# synth_revC.net
KiCad netlist of a schematic drawn in EAGLE
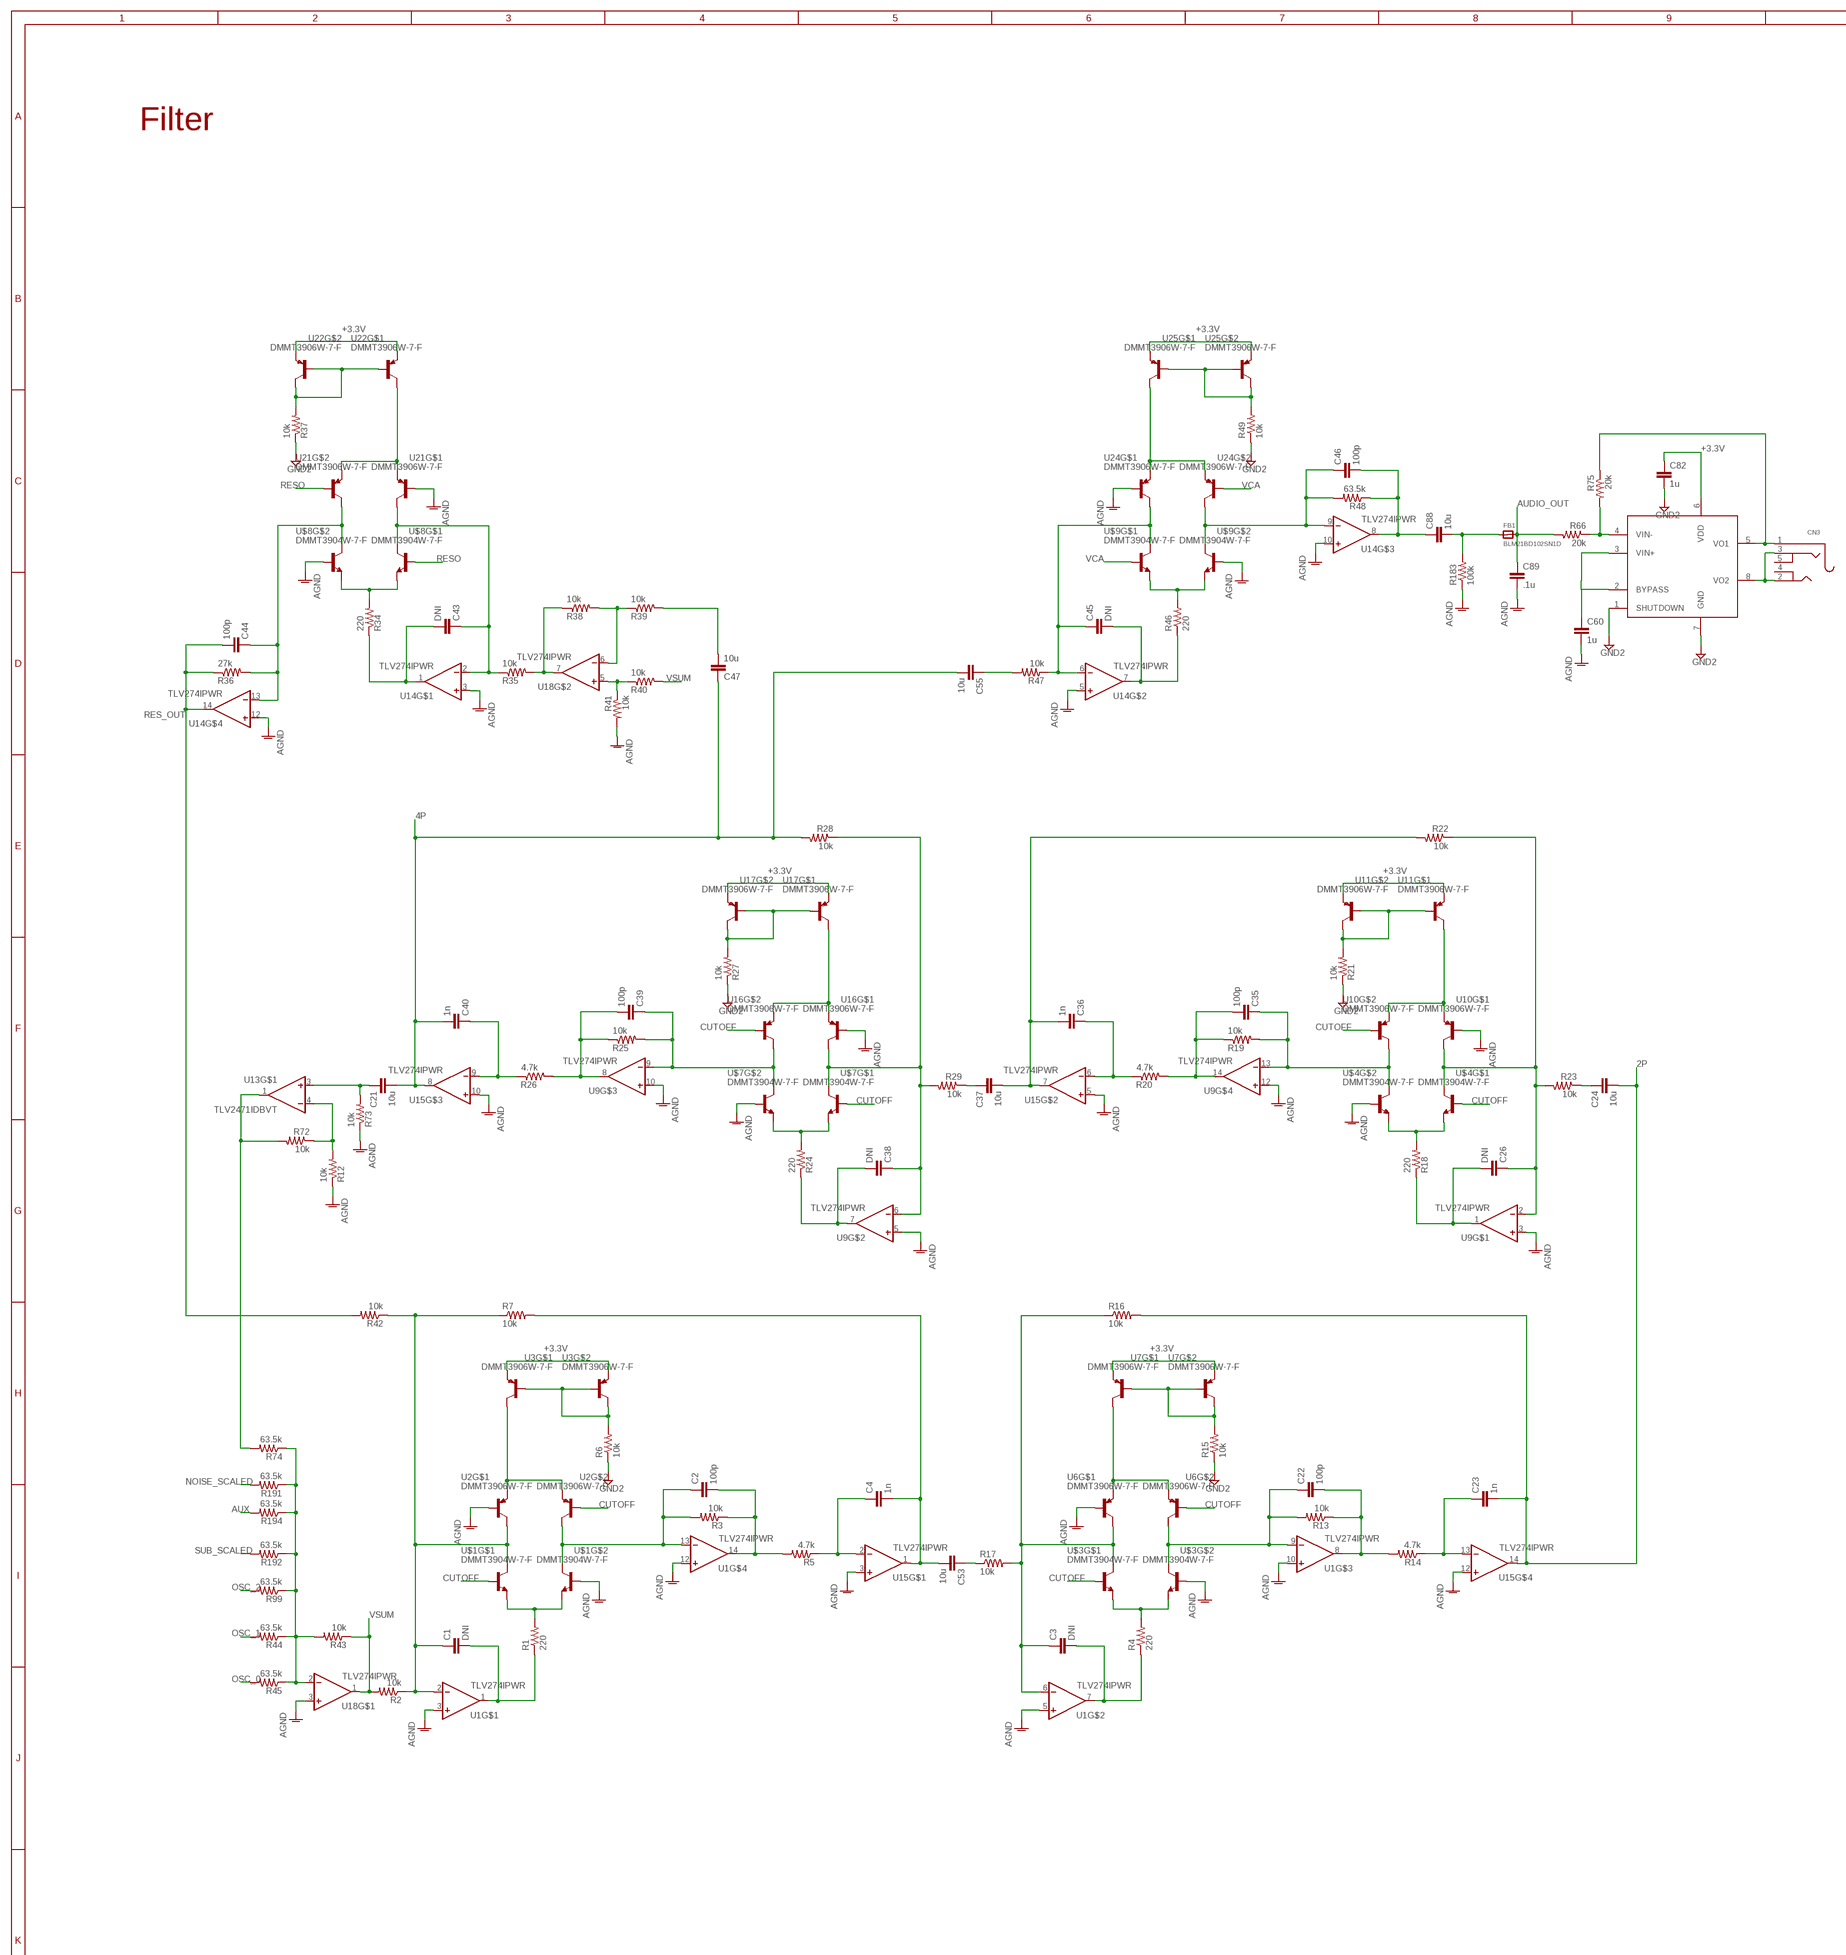
[diagram p0: schematic, sheet 1, part 1 of 3]
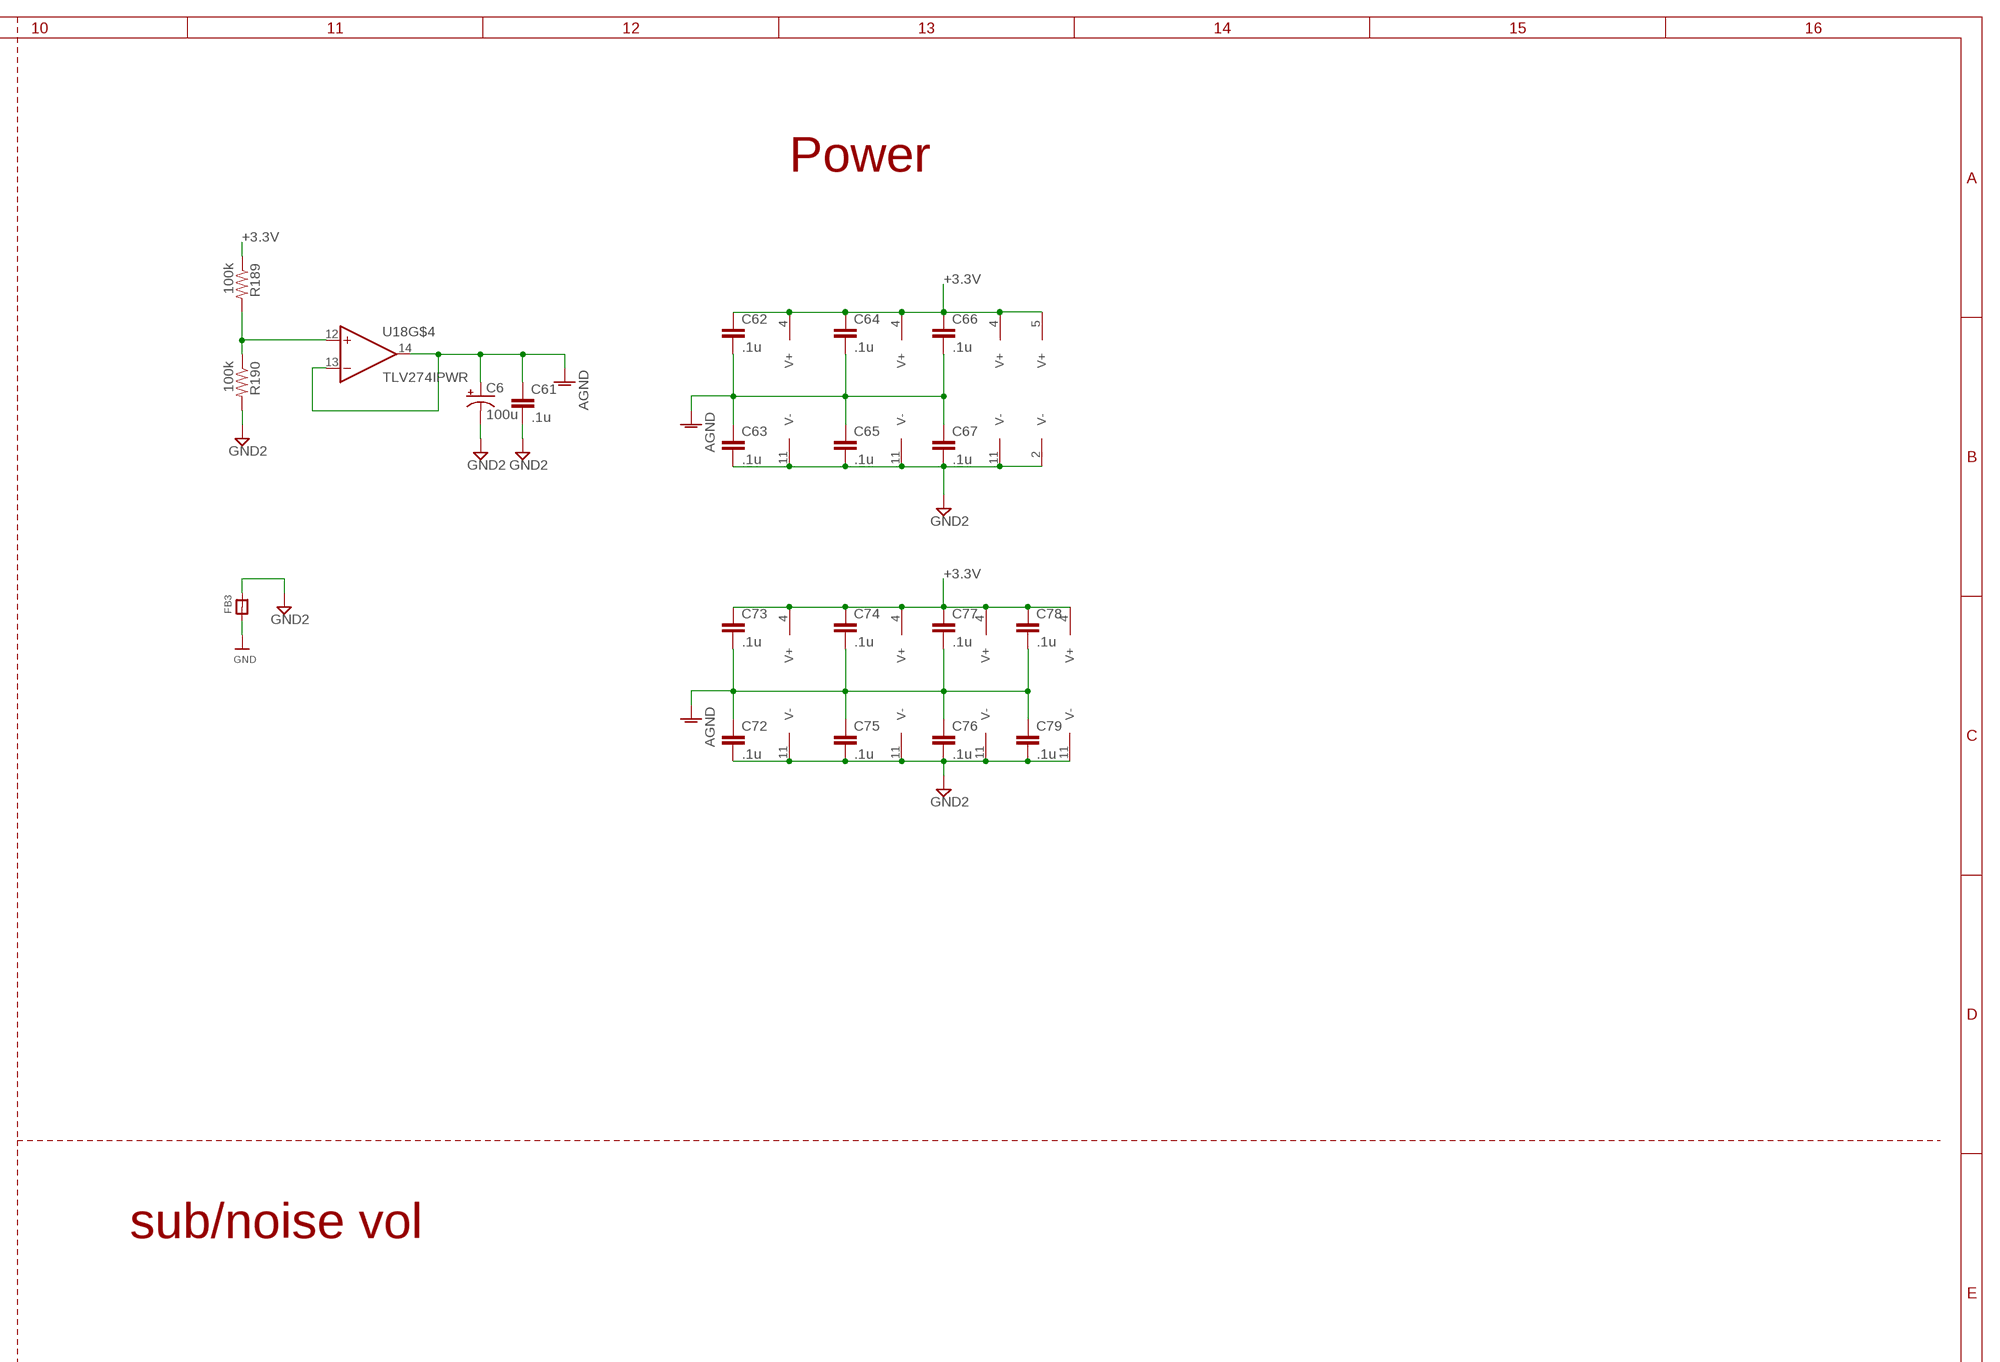
[diagram p1: schematic, sheet 1, part 2 of 3]
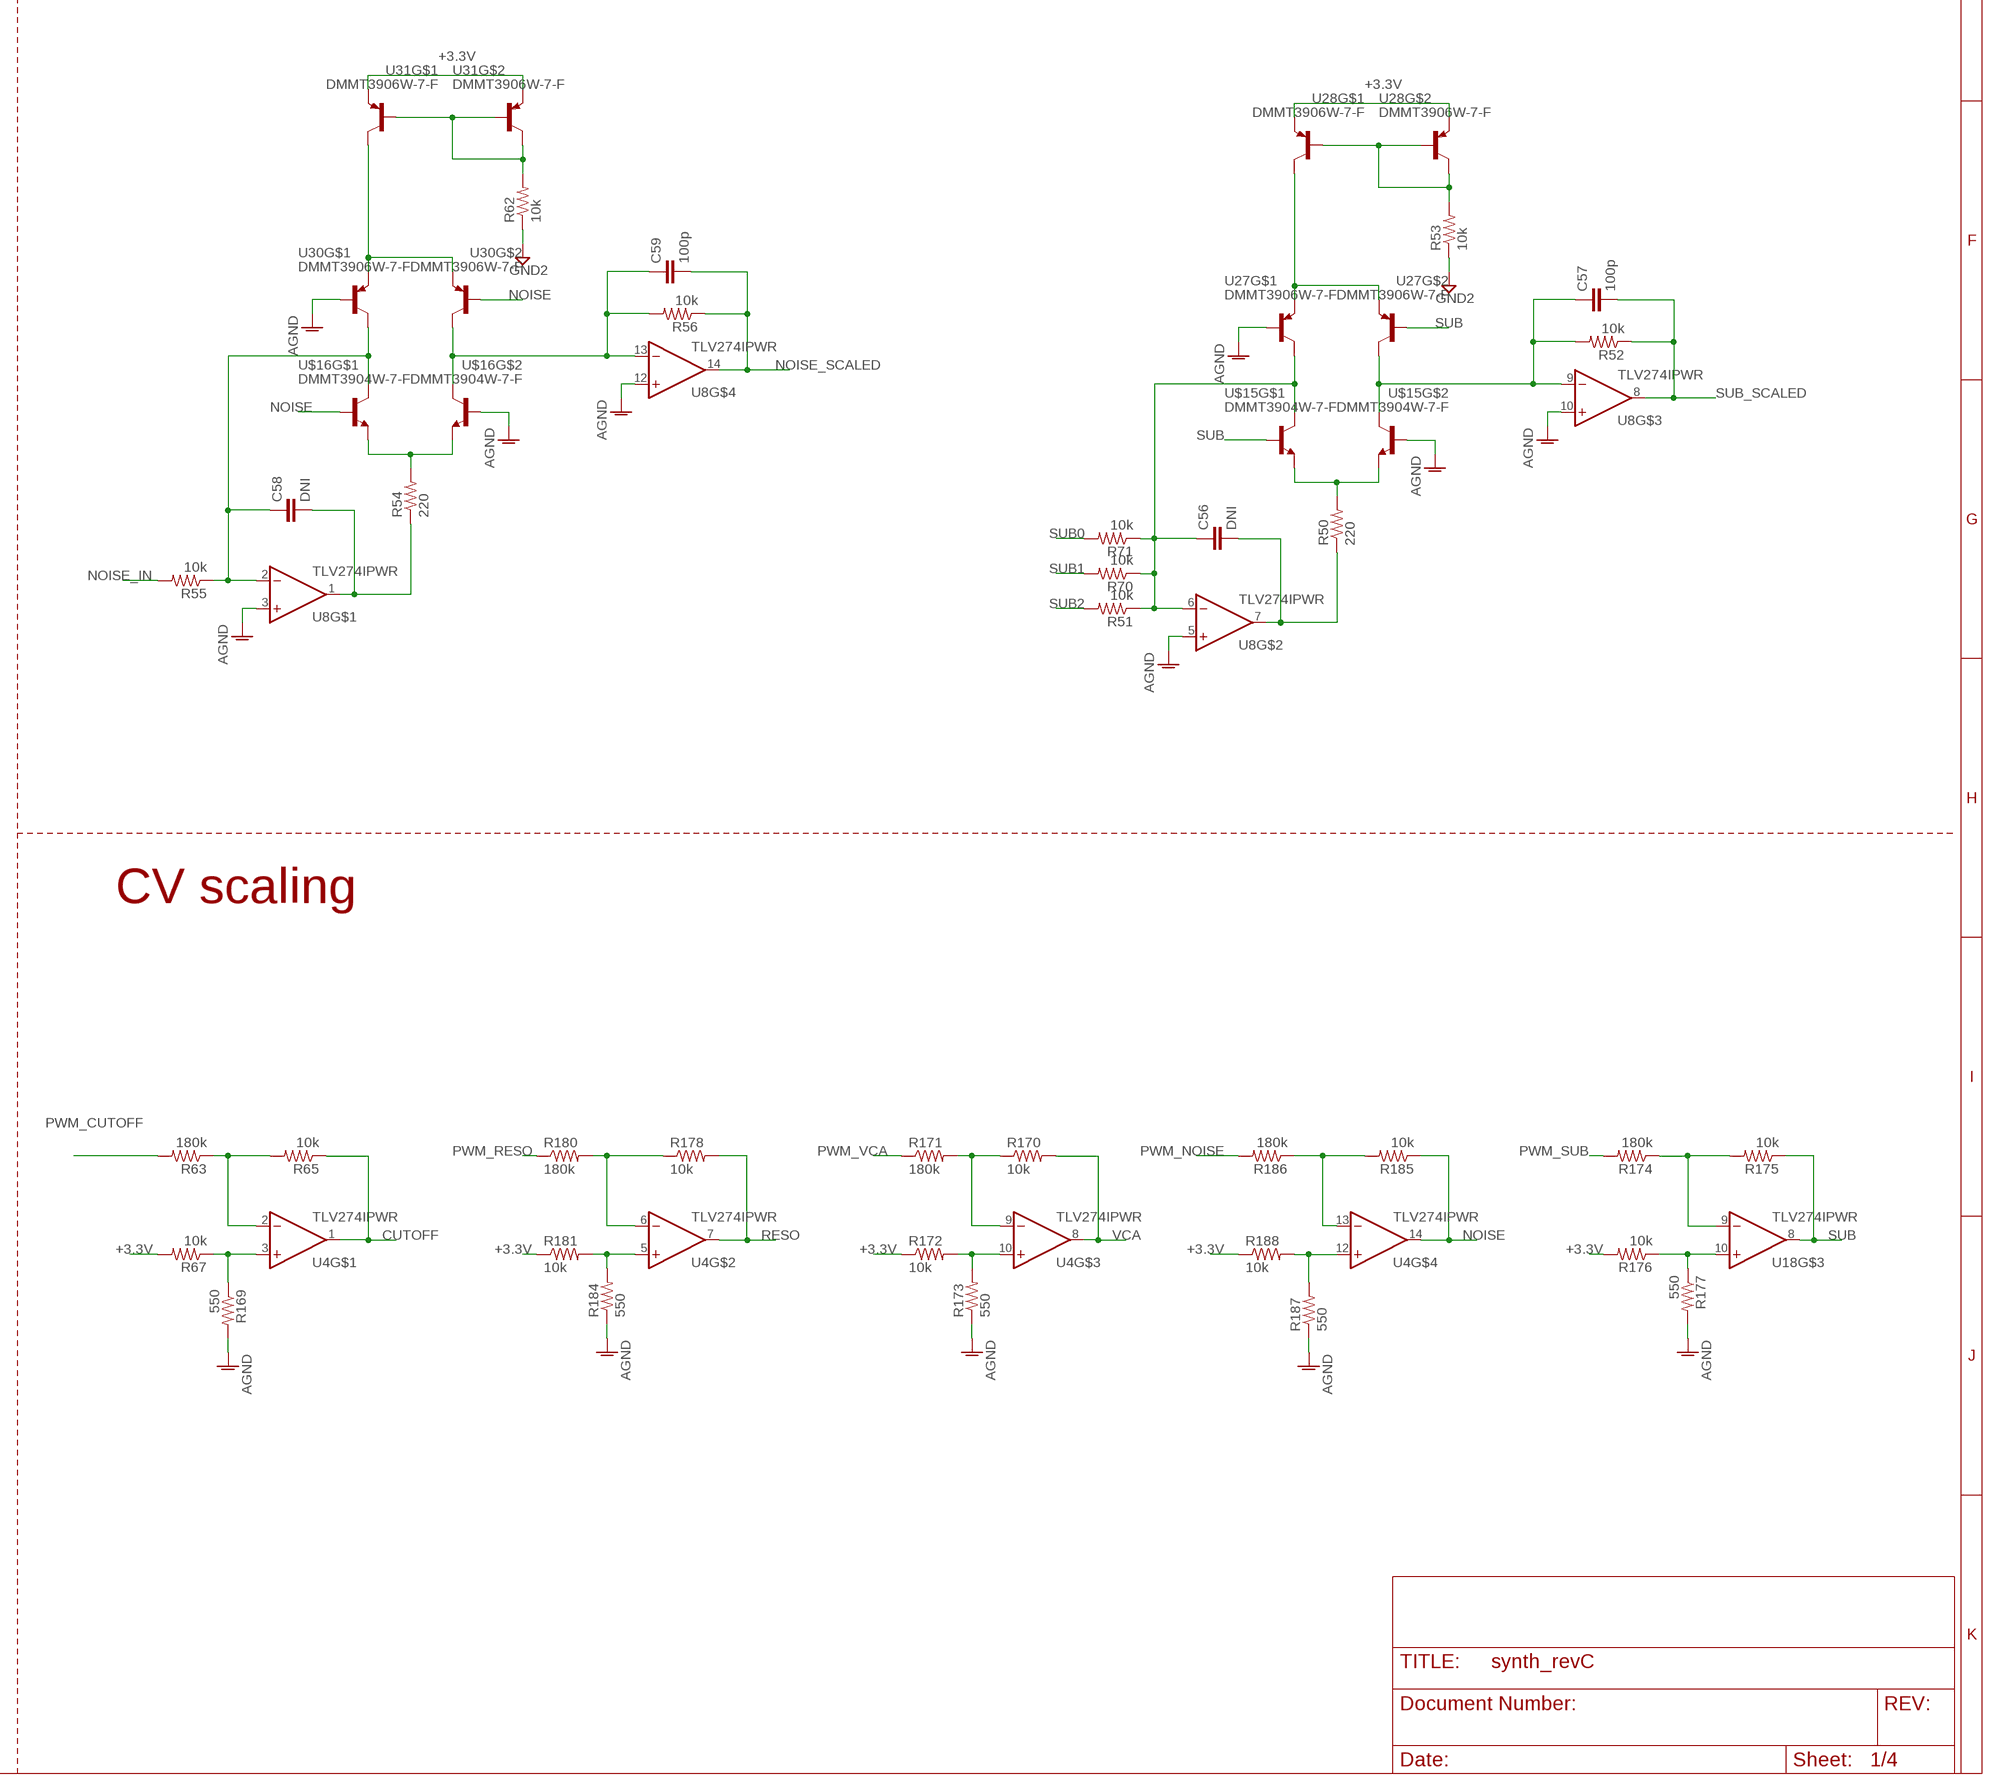
[diagram p2: schematic, sheet 1, part 3 of 3]
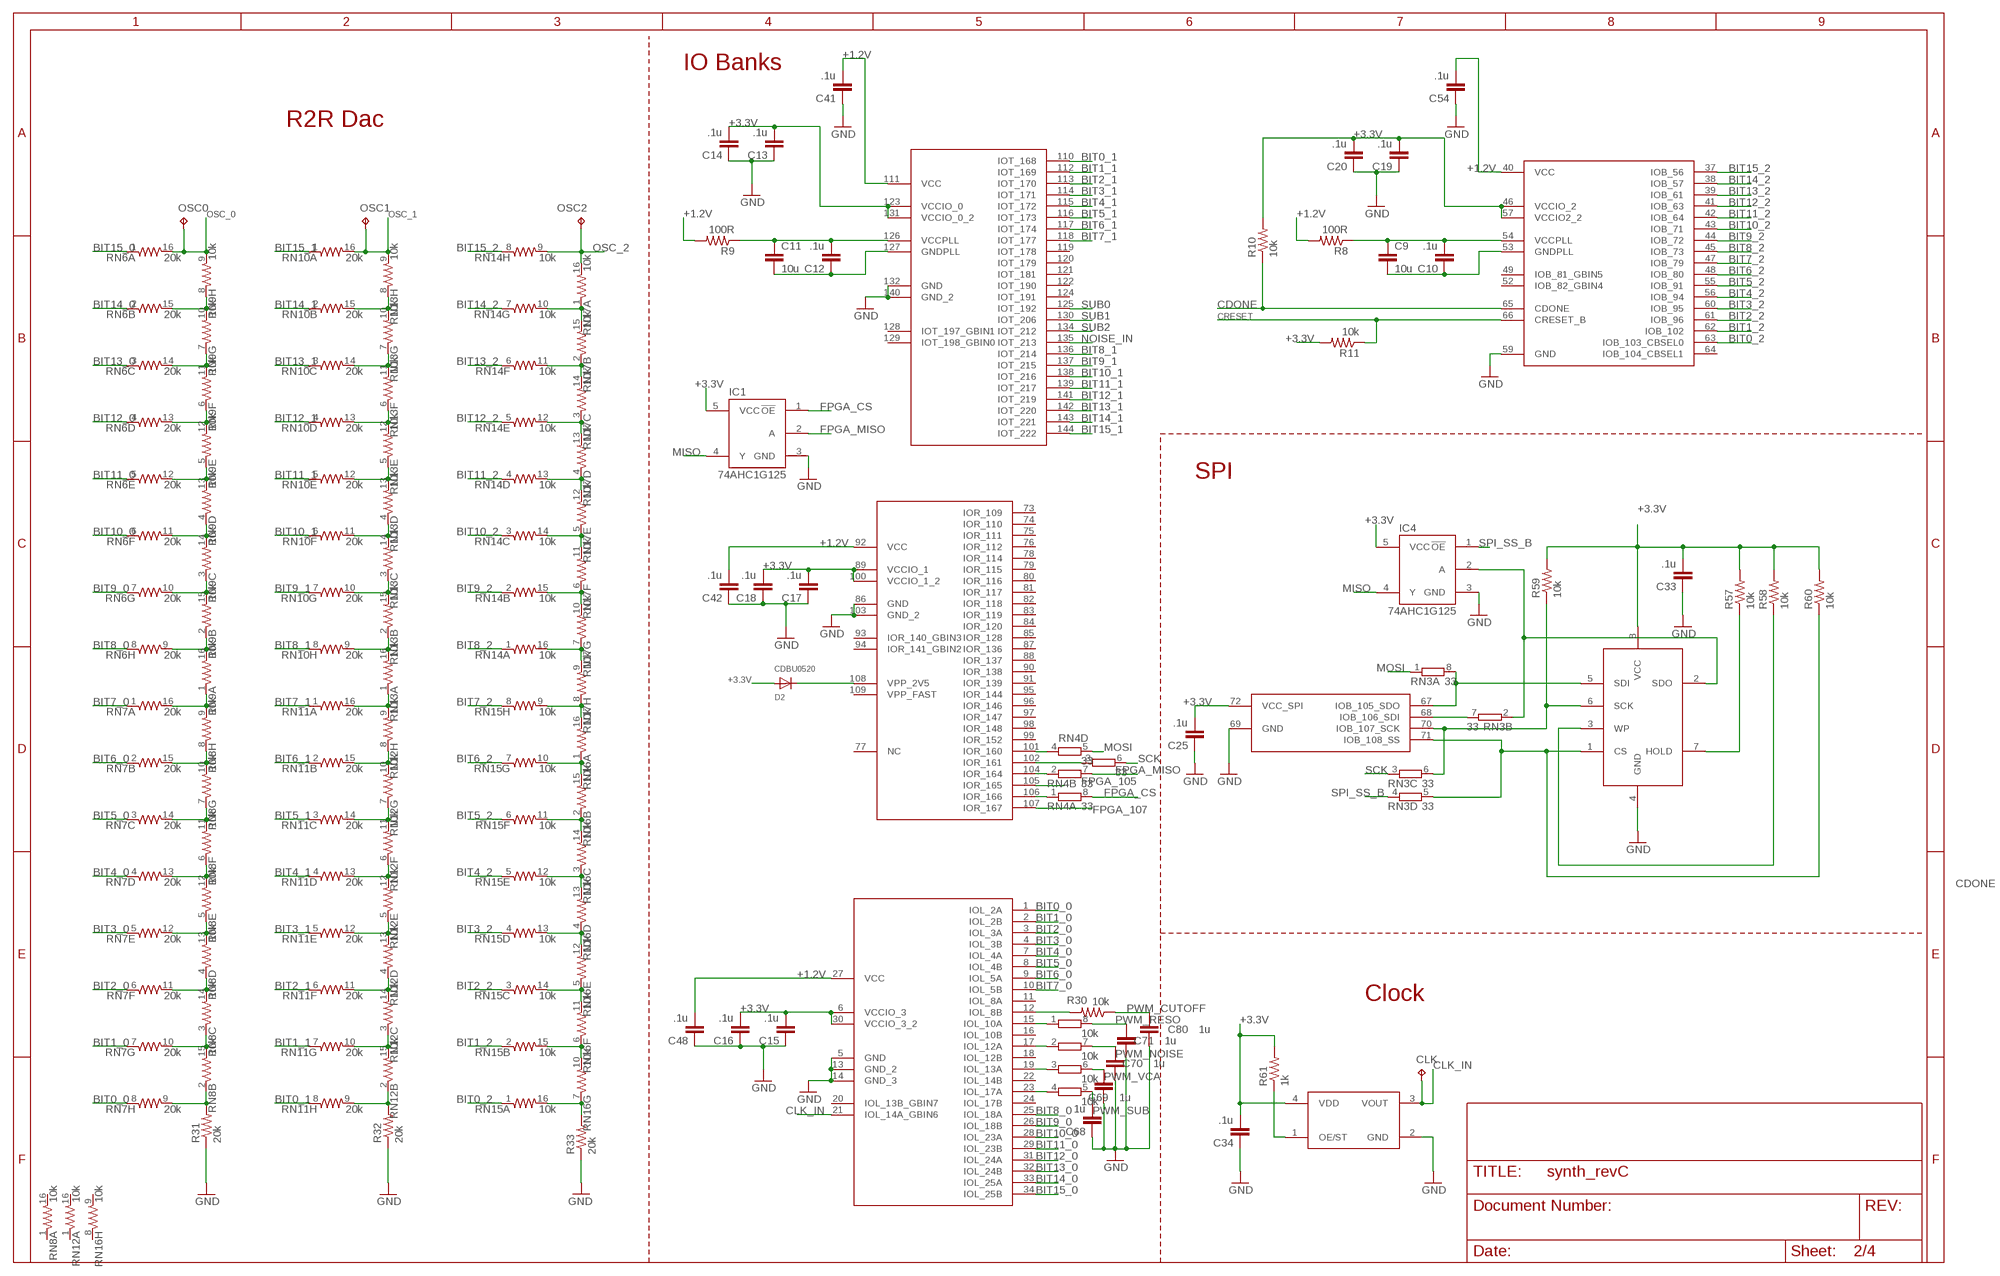
[diagram p3: schematic, sheet 2]
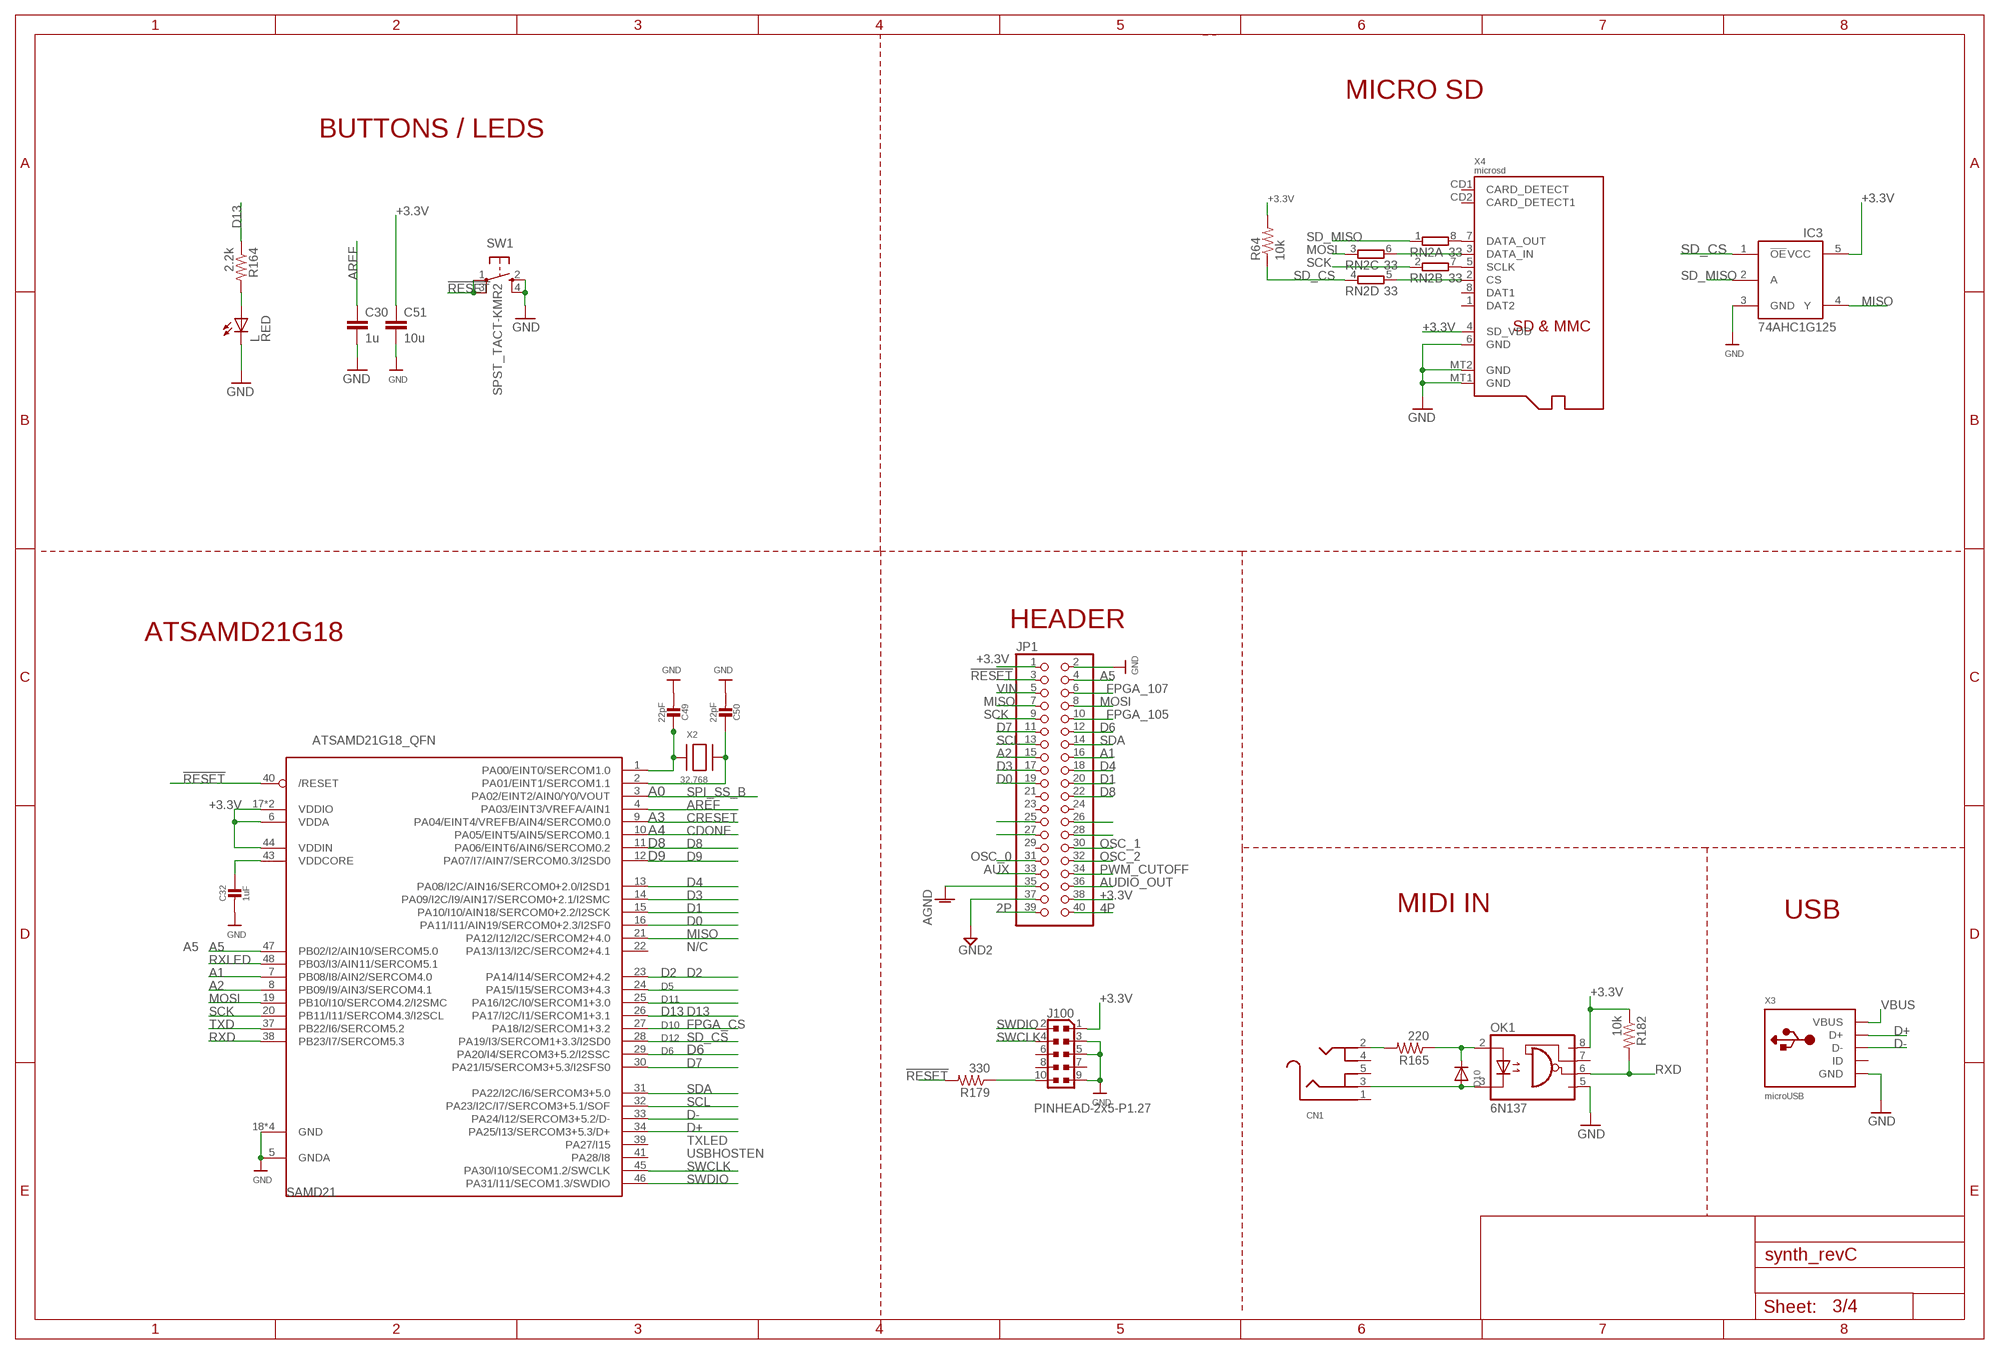
[diagram p4: schematic, sheet 3]
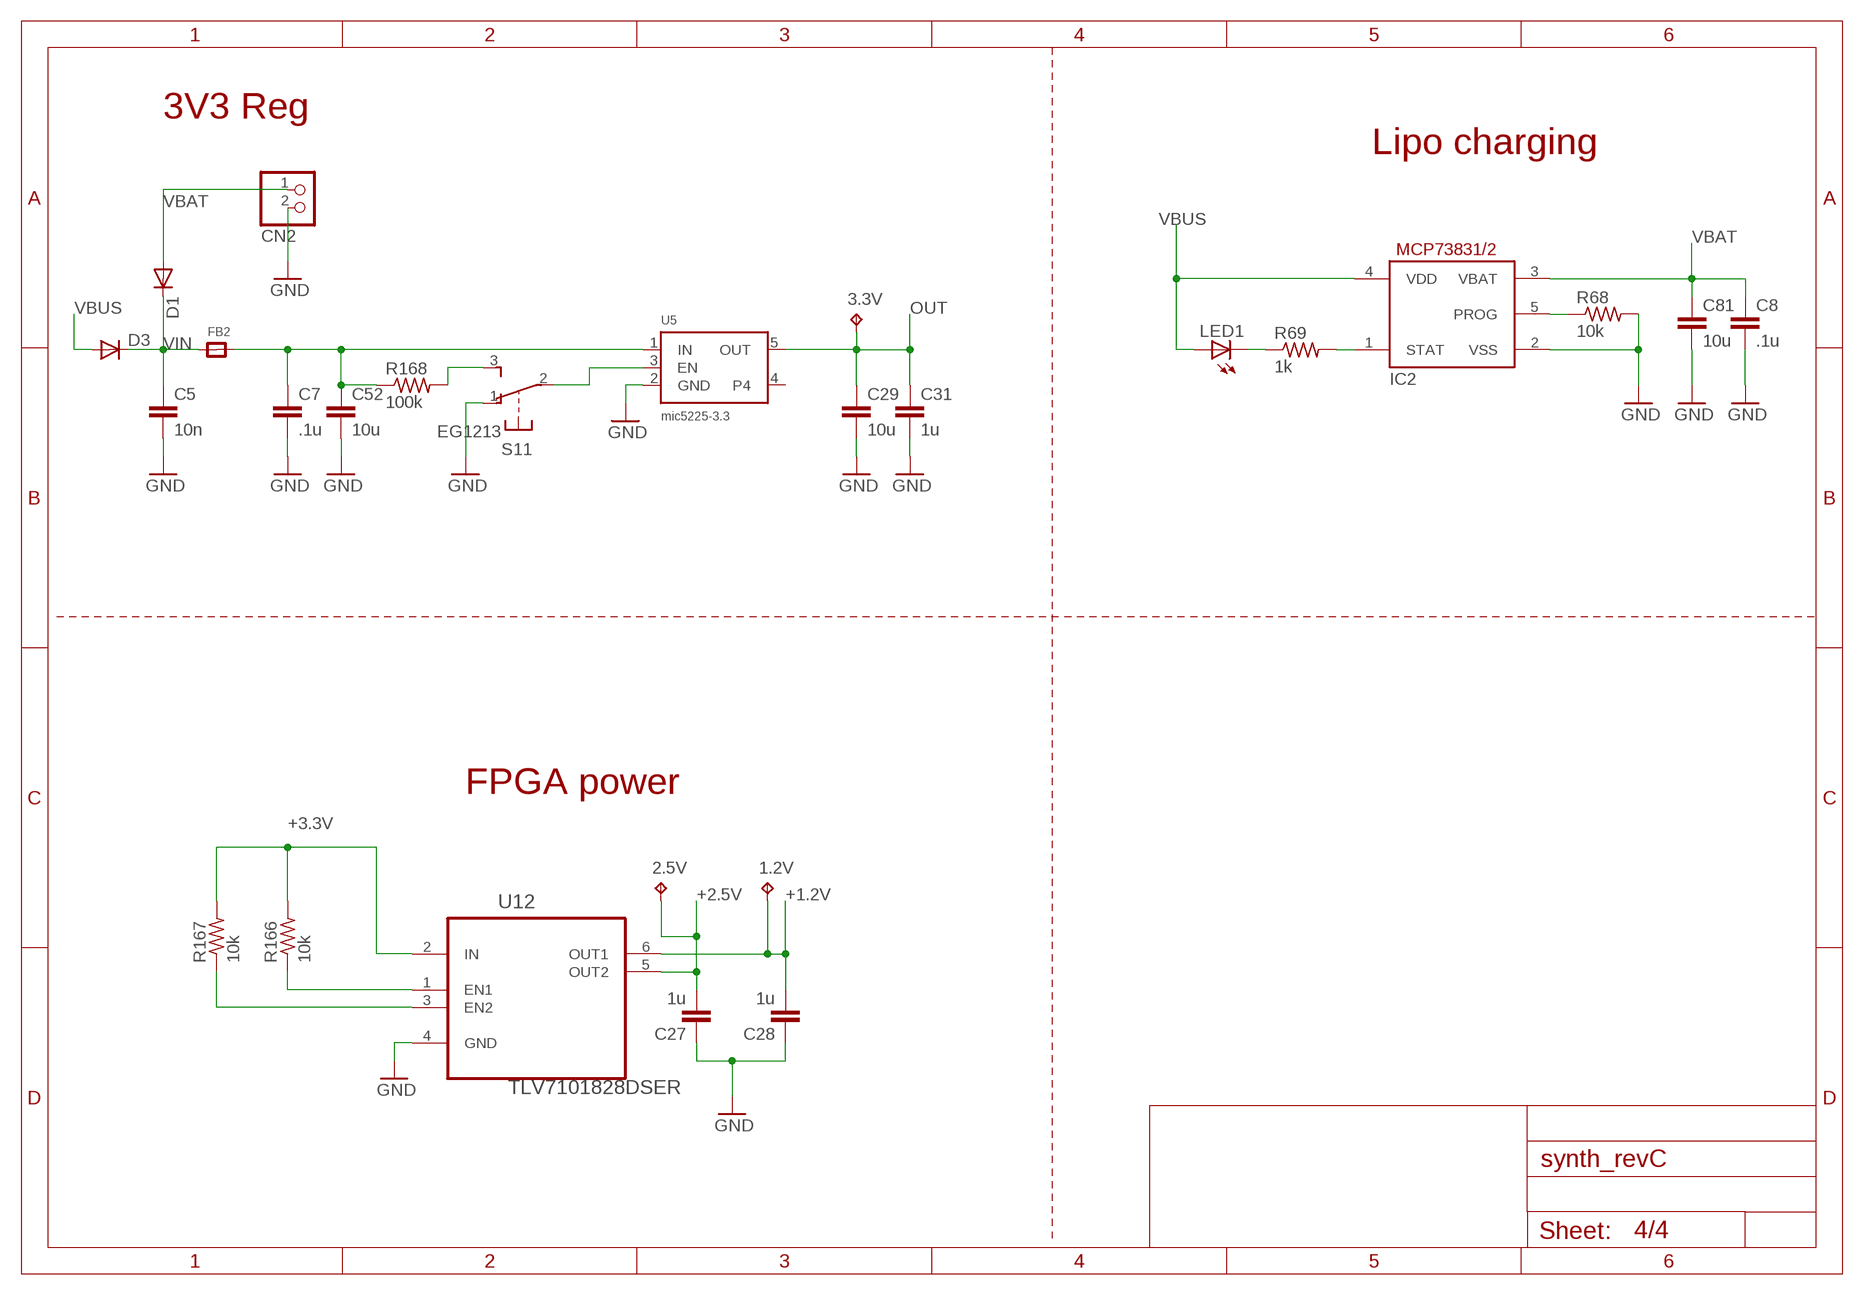
[diagram p5: schematic, sheet 4]

(export (version "E")
  (design (tool "Eeschema 10.0.6"))
  (components
    (comp (ref "C1")
      (value "DNI")
      (footprint "eagle-import:C0603")
      (libsource (lib "eagle-import") (part "C-EUC0603"))
    )
    (comp (ref "C2")
      (value "100p")
      (footprint "eagle-import:C0603")
      (libsource (lib "eagle-import") (part "C-EUC0603"))
    )
    (comp (ref "C3")
      (value "DNI")
      (footprint "eagle-import:C0603")
      (libsource (lib "eagle-import") (part "C-EUC0603"))
    )
    (comp (ref "C4")
      (value "1n")
      (footprint "eagle-import:C0603")
      (libsource (lib "eagle-import") (part "C-EUC0603"))
    )
    (comp (ref "C6")
      (value "100u")
      (footprint "eagle-import:PANASONIC_C")
      (libsource (lib "eagle-import") (part "CPOL-USC"))
    )
    (comp (ref "C21")
      (value "10u")
      (footprint "eagle-import:C0603")
      (libsource (lib "eagle-import") (part "C-EUC0603"))
    )
    (comp (ref "C22")
      (value "100p")
      (footprint "eagle-import:C0603")
      (libsource (lib "eagle-import") (part "C-EUC0603"))
    )
    (comp (ref "C23")
      (value "1n")
      (footprint "eagle-import:C0603")
      (libsource (lib "eagle-import") (part "C-EUC0603"))
    )
    (comp (ref "C24")
      (value "10u")
      (footprint "eagle-import:C0603")
      (libsource (lib "eagle-import") (part "C-EUC0603"))
    )
    (comp (ref "C26")
      (value "DNI")
      (footprint "eagle-import:C0603")
      (libsource (lib "eagle-import") (part "C-EUC0603"))
    )
    (comp (ref "C35")
      (value "100p")
      (footprint "eagle-import:C0603")
      (libsource (lib "eagle-import") (part "C-EUC0603"))
    )
    (comp (ref "C36")
      (value "1n")
      (footprint "eagle-import:C0603")
      (libsource (lib "eagle-import") (part "C-EUC0603"))
    )
    (comp (ref "C37")
      (value "10u")
      (footprint "eagle-import:C0603")
      (libsource (lib "eagle-import") (part "C-EUC0603"))
    )
    (comp (ref "C38")
      (value "DNI")
      (footprint "eagle-import:C0603")
      (libsource (lib "eagle-import") (part "C-EUC0603"))
    )
    (comp (ref "C39")
      (value "100p")
      (footprint "eagle-import:C0603")
      (libsource (lib "eagle-import") (part "C-EUC0603"))
    )
    (comp (ref "C40")
      (value "1n")
      (footprint "eagle-import:C0603")
      (libsource (lib "eagle-import") (part "C-EUC0603"))
    )
    (comp (ref "C43")
      (value "DNI")
      (footprint "eagle-import:C0603")
      (libsource (lib "eagle-import") (part "C-EUC0603"))
    )
    (comp (ref "C44")
      (value "100p")
      (footprint "eagle-import:C0603")
      (libsource (lib "eagle-import") (part "C-EUC0603"))
    )
    (comp (ref "C45")
      (value "DNI")
      (footprint "eagle-import:C0603")
      (libsource (lib "eagle-import") (part "C-EUC0603"))
    )
    (comp (ref "C46")
      (value "100p")
      (footprint "eagle-import:C0603")
      (libsource (lib "eagle-import") (part "C-EUC0603"))
    )
    (comp (ref "C47")
      (value "10u")
      (footprint "eagle-import:C0603")
      (libsource (lib "eagle-import") (part "C-EUC0603"))
    )
    (comp (ref "C53")
      (value "10u")
      (footprint "eagle-import:C0603")
      (libsource (lib "eagle-import") (part "C-EUC0603"))
    )
    (comp (ref "C55")
      (value "10u")
      (footprint "eagle-import:C0603")
      (libsource (lib "eagle-import") (part "C-EUC0603"))
    )
    (comp (ref "C56")
      (value "DNI")
      (footprint "eagle-import:C0603")
      (libsource (lib "eagle-import") (part "C-EUC0603"))
    )
    (comp (ref "C57")
      (value "100p")
      (footprint "eagle-import:C0603")
      (libsource (lib "eagle-import") (part "C-EUC0603"))
    )
    (comp (ref "C58")
      (value "DNI")
      (footprint "eagle-import:C0603")
      (libsource (lib "eagle-import") (part "C-EUC0603"))
    )
    (comp (ref "C59")
      (value "100p")
      (footprint "eagle-import:C0603")
      (libsource (lib "eagle-import") (part "C-EUC0603"))
    )
    (comp (ref "C60")
      (value "1u")
      (footprint "eagle-import:C0603")
      (libsource (lib "eagle-import") (part "C-EUC0603"))
    )
    (comp (ref "C61")
      (value ".1u")
      (footprint "eagle-import:C0603")
      (libsource (lib "eagle-import") (part "C-EUC0603"))
    )
    (comp (ref "C62")
      (value ".1u")
      (footprint "eagle-import:C0603")
      (libsource (lib "eagle-import") (part "C-EUC0603"))
    )
    (comp (ref "C63")
      (value ".1u")
      (footprint "eagle-import:C0603")
      (libsource (lib "eagle-import") (part "C-EUC0603"))
    )
    (comp (ref "C64")
      (value ".1u")
      (footprint "eagle-import:C0603")
      (libsource (lib "eagle-import") (part "C-EUC0603"))
    )
    (comp (ref "C65")
      (value ".1u")
      (footprint "eagle-import:C0603")
      (libsource (lib "eagle-import") (part "C-EUC0603"))
    )
    (comp (ref "C66")
      (value ".1u")
      (footprint "eagle-import:C0603")
      (libsource (lib "eagle-import") (part "C-EUC0603"))
    )
    (comp (ref "C67")
      (value ".1u")
      (footprint "eagle-import:C0603")
      (libsource (lib "eagle-import") (part "C-EUC0603"))
    )
    (comp (ref "C72")
      (value ".1u")
      (footprint "eagle-import:C0603")
      (libsource (lib "eagle-import") (part "C-EUC0603"))
    )
    (comp (ref "C73")
      (value ".1u")
      (footprint "eagle-import:C0603")
      (libsource (lib "eagle-import") (part "C-EUC0603"))
    )
    (comp (ref "C74")
      (value ".1u")
      (footprint "eagle-import:C0603")
      (libsource (lib "eagle-import") (part "C-EUC0603"))
    )
    (comp (ref "C75")
      (value ".1u")
      (footprint "eagle-import:C0603")
      (libsource (lib "eagle-import") (part "C-EUC0603"))
    )
    (comp (ref "C76")
      (value ".1u")
      (footprint "eagle-import:C0603")
      (libsource (lib "eagle-import") (part "C-EUC0603"))
    )
    (comp (ref "C77")
      (value ".1u")
      (footprint "eagle-import:C0603")
      (libsource (lib "eagle-import") (part "C-EUC0603"))
    )
    (comp (ref "C78")
      (value ".1u")
      (footprint "eagle-import:C0603")
      (libsource (lib "eagle-import") (part "C-EUC0603"))
    )
    (comp (ref "C79")
      (value ".1u")
      (footprint "eagle-import:C0603")
      (libsource (lib "eagle-import") (part "C-EUC0603"))
    )
    (comp (ref "C82")
      (value "1u")
      (footprint "eagle-import:C0603")
      (libsource (lib "eagle-import") (part "C-EUC0603"))
    )
    (comp (ref "C88")
      (value "10u")
      (footprint "eagle-import:C0603")
      (libsource (lib "eagle-import") (part "C-EUC0603"))
    )
    (comp (ref "C89")
      (value ".1u")
      (footprint "eagle-import:C0603")
      (libsource (lib "eagle-import") (part "C-EUC0603"))
    )
    (comp (ref "CN3")
      (value "AUDIO_3.5MMJACK")
      (footprint "eagle-import:4UCONN_19269")
      (libsource (lib "eagle-import") (part "AUDIO_3.5MMJACK"))
    )
    (comp (ref "FB1")
      (value "BLM21BD102SN1D")
      (footprint "eagle-import:0805")
      (libsource (lib "eagle-import") (part "FERRITE0805"))
    )
    (comp (ref "FB3")
      (value "FERRITE0805")
      (footprint "eagle-import:0805")
      (libsource (lib "eagle-import") (part "FERRITE0805"))
    )
    (comp (ref "R1")
      (value "220")
      (footprint "eagle-import:R0603")
      (libsource (lib "eagle-import") (part "rcl_R-US_R0603"))
    )
    (comp (ref "R2")
      (value "10k")
      (footprint "eagle-import:R0603")
      (libsource (lib "eagle-import") (part "rcl_R-US_R0603"))
    )
    (comp (ref "R3")
      (value "10k")
      (footprint "eagle-import:R0603")
      (libsource (lib "eagle-import") (part "rcl_R-US_R0603"))
    )
    (comp (ref "R4")
      (value "220")
      (footprint "eagle-import:R0603")
      (libsource (lib "eagle-import") (part "rcl_R-US_R0603"))
    )
    (comp (ref "R5")
      (value "4.7k")
      (footprint "eagle-import:R0603")
      (libsource (lib "eagle-import") (part "rcl_R-US_R0603"))
    )
    (comp (ref "R6")
      (value "10k")
      (footprint "eagle-import:R0603")
      (libsource (lib "eagle-import") (part "rcl_R-US_R0603"))
    )
    (comp (ref "R7")
      (value "10k")
      (footprint "eagle-import:R0603")
      (libsource (lib "eagle-import") (part "rcl_R-US_R0603"))
    )
    (comp (ref "R12")
      (value "10k")
      (footprint "eagle-import:R0603")
      (libsource (lib "eagle-import") (part "rcl_R-US_R0603"))
    )
    (comp (ref "R13")
      (value "10k")
      (footprint "eagle-import:R0603")
      (libsource (lib "eagle-import") (part "rcl_R-US_R0603"))
    )
    (comp (ref "R14")
      (value "4.7k")
      (footprint "eagle-import:R0603")
      (libsource (lib "eagle-import") (part "rcl_R-US_R0603"))
    )
    (comp (ref "R15")
      (value "10k")
      (footprint "eagle-import:R0603")
      (libsource (lib "eagle-import") (part "rcl_R-US_R0603"))
    )
    (comp (ref "R16")
      (value "10k")
      (footprint "eagle-import:R0603")
      (libsource (lib "eagle-import") (part "rcl_R-US_R0603"))
    )
    (comp (ref "R17")
      (value "10k")
      (footprint "eagle-import:R0603")
      (libsource (lib "eagle-import") (part "rcl_R-US_R0603"))
    )
    (comp (ref "R18")
      (value "220")
      (footprint "eagle-import:R0603")
      (libsource (lib "eagle-import") (part "rcl_R-US_R0603"))
    )
    (comp (ref "R19")
      (value "10k")
      (footprint "eagle-import:R0603")
      (libsource (lib "eagle-import") (part "rcl_R-US_R0603"))
    )
    (comp (ref "R20")
      (value "4.7k")
      (footprint "eagle-import:R0603")
      (libsource (lib "eagle-import") (part "rcl_R-US_R0603"))
    )
    (comp (ref "R21")
      (value "10k")
      (footprint "eagle-import:R0603")
      (libsource (lib "eagle-import") (part "rcl_R-US_R0603"))
    )
    (comp (ref "R22")
      (value "10k")
      (footprint "eagle-import:R0603")
      (libsource (lib "eagle-import") (part "rcl_R-US_R0603"))
    )
    (comp (ref "R23")
      (value "10k")
      (footprint "eagle-import:R0603")
      (libsource (lib "eagle-import") (part "rcl_R-US_R0603"))
    )
    (comp (ref "R24")
      (value "220")
      (footprint "eagle-import:R0603")
      (libsource (lib "eagle-import") (part "rcl_R-US_R0603"))
    )
    (comp (ref "R25")
      (value "10k")
      (footprint "eagle-import:R0603")
      (libsource (lib "eagle-import") (part "rcl_R-US_R0603"))
    )
    (comp (ref "R26")
      (value "4.7k")
      (footprint "eagle-import:R0603")
      (libsource (lib "eagle-import") (part "rcl_R-US_R0603"))
    )
    (comp (ref "R27")
      (value "10k")
      (footprint "eagle-import:R0603")
      (libsource (lib "eagle-import") (part "rcl_R-US_R0603"))
    )
    (comp (ref "R28")
      (value "10k")
      (footprint "eagle-import:R0603")
      (libsource (lib "eagle-import") (part "rcl_R-US_R0603"))
    )
    (comp (ref "R29")
      (value "10k")
      (footprint "eagle-import:R0603")
      (libsource (lib "eagle-import") (part "rcl_R-US_R0603"))
    )
    (comp (ref "R34")
      (value "220")
      (footprint "eagle-import:R0603")
      (libsource (lib "eagle-import") (part "rcl_R-US_R0603"))
    )
    (comp (ref "R35")
      (value "10k")
      (footprint "eagle-import:R0603")
      (libsource (lib "eagle-import") (part "rcl_R-US_R0603"))
    )
    (comp (ref "R36")
      (value "27k")
      (footprint "eagle-import:R0603")
      (libsource (lib "eagle-import") (part "rcl_R-US_R0603"))
    )
    (comp (ref "R37")
      (value "10k")
      (footprint "eagle-import:R0603")
      (libsource (lib "eagle-import") (part "rcl_R-US_R0603"))
    )
    (comp (ref "R38")
      (value "10k")
      (footprint "eagle-import:R0603")
      (libsource (lib "eagle-import") (part "rcl_R-US_R0603"))
    )
    (comp (ref "R39")
      (value "10k")
      (footprint "eagle-import:R0603")
      (libsource (lib "eagle-import") (part "rcl_R-US_R0603"))
    )
    (comp (ref "R40")
      (value "10k")
      (footprint "eagle-import:R0603")
      (libsource (lib "eagle-import") (part "rcl_R-US_R0603"))
    )
    (comp (ref "R41")
      (value "10k")
      (footprint "eagle-import:R0603")
      (libsource (lib "eagle-import") (part "rcl_R-US_R0603"))
    )
    (comp (ref "R42")
      (value "10k")
      (footprint "eagle-import:R0603")
      (libsource (lib "eagle-import") (part "rcl_R-US_R0603"))
    )
    (comp (ref "R43")
      (value "10k")
      (footprint "eagle-import:R0603")
      (libsource (lib "eagle-import") (part "rcl_R-US_R0603"))
    )
    (comp (ref "R44")
      (value "63.5k")
      (footprint "eagle-import:R0603")
      (libsource (lib "eagle-import") (part "rcl_R-US_R0603"))
    )
    (comp (ref "R45")
      (value "63.5k")
      (footprint "eagle-import:R0603")
      (libsource (lib "eagle-import") (part "rcl_R-US_R0603"))
    )
    (comp (ref "R46")
      (value "220")
      (footprint "eagle-import:R0603")
      (libsource (lib "eagle-import") (part "rcl_R-US_R0603"))
    )
    (comp (ref "R47")
      (value "10k")
      (footprint "eagle-import:R0603")
      (libsource (lib "eagle-import") (part "rcl_R-US_R0603"))
    )
    (comp (ref "R48")
      (value "63.5k")
      (footprint "eagle-import:R0603")
      (libsource (lib "eagle-import") (part "rcl_R-US_R0603"))
    )
    (comp (ref "R49")
      (value "10k")
      (footprint "eagle-import:R0603")
      (libsource (lib "eagle-import") (part "rcl_R-US_R0603"))
    )
    (comp (ref "R50")
      (value "220")
      (footprint "eagle-import:R0603")
      (libsource (lib "eagle-import") (part "rcl_R-US_R0603"))
    )
    (comp (ref "R51")
      (value "10k")
      (footprint "eagle-import:R0603")
      (libsource (lib "eagle-import") (part "rcl_R-US_R0603"))
    )
    (comp (ref "R52")
      (value "10k")
      (footprint "eagle-import:R0603")
      (libsource (lib "eagle-import") (part "rcl_R-US_R0603"))
    )
    (comp (ref "R53")
      (value "10k")
      (footprint "eagle-import:R0603")
      (libsource (lib "eagle-import") (part "rcl_R-US_R0603"))
    )
    (comp (ref "R54")
      (value "220")
      (footprint "eagle-import:R0603")
      (libsource (lib "eagle-import") (part "rcl_R-US_R0603"))
    )
    (comp (ref "R55")
      (value "10k")
      (footprint "eagle-import:R0603")
      (libsource (lib "eagle-import") (part "rcl_R-US_R0603"))
    )
    (comp (ref "R56")
      (value "10k")
      (footprint "eagle-import:R0603")
      (libsource (lib "eagle-import") (part "rcl_R-US_R0603"))
    )
    (comp (ref "R62")
      (value "10k")
      (footprint "eagle-import:R0603")
      (libsource (lib "eagle-import") (part "rcl_R-US_R0603"))
    )
    (comp (ref "R63")
      (value "180k")
      (footprint "eagle-import:R0603")
      (libsource (lib "eagle-import") (part "rcl_R-US_R0603"))
    )
    (comp (ref "R65")
      (value "10k")
      (footprint "eagle-import:R0603")
      (libsource (lib "eagle-import") (part "rcl_R-US_R0603"))
    )
    (comp (ref "R66")
      (value "20k")
      (footprint "eagle-import:R0603")
      (libsource (lib "eagle-import") (part "rcl_R-US_R0603"))
    )
    (comp (ref "R67")
      (value "10k")
      (footprint "eagle-import:R0603")
      (libsource (lib "eagle-import") (part "rcl_R-US_R0603"))
    )
    (comp (ref "R70")
      (value "10k")
      (footprint "eagle-import:R0603")
      (libsource (lib "eagle-import") (part "rcl_R-US_R0603"))
    )
    (comp (ref "R71")
      (value "10k")
      (footprint "eagle-import:R0603")
      (libsource (lib "eagle-import") (part "rcl_R-US_R0603"))
    )
    (comp (ref "R72")
      (value "10k")
      (footprint "eagle-import:R0603")
      (libsource (lib "eagle-import") (part "rcl_R-US_R0603"))
    )
    (comp (ref "R73")
      (value "10k")
      (footprint "eagle-import:R0603")
      (libsource (lib "eagle-import") (part "rcl_R-US_R0603"))
    )
    (comp (ref "R74")
      (value "63.5k")
      (footprint "eagle-import:R0603")
      (libsource (lib "eagle-import") (part "rcl_R-US_R0603"))
    )
    (comp (ref "R75")
      (value "20k")
      (footprint "eagle-import:R0603")
      (libsource (lib "eagle-import") (part "rcl_R-US_R0603"))
    )
    (comp (ref "R99")
      (value "63.5k")
      (footprint "eagle-import:R0603")
      (libsource (lib "eagle-import") (part "rcl_R-US_R0603"))
    )
    (comp (ref "R169")
      (value "550")
      (footprint "eagle-import:R0603")
      (libsource (lib "eagle-import") (part "rcl_R-US_R0603"))
    )
    (comp (ref "R170")
      (value "10k")
      (footprint "eagle-import:R0603")
      (libsource (lib "eagle-import") (part "rcl_R-US_R0603"))
    )
    (comp (ref "R171")
      (value "180k")
      (footprint "eagle-import:R0603")
      (libsource (lib "eagle-import") (part "rcl_R-US_R0603"))
    )
    (comp (ref "R172")
      (value "10k")
      (footprint "eagle-import:R0603")
      (libsource (lib "eagle-import") (part "rcl_R-US_R0603"))
    )
    (comp (ref "R173")
      (value "550")
      (footprint "eagle-import:R0603")
      (libsource (lib "eagle-import") (part "rcl_R-US_R0603"))
    )
    (comp (ref "R174")
      (value "180k")
      (footprint "eagle-import:R0603")
      (libsource (lib "eagle-import") (part "rcl_R-US_R0603"))
    )
    (comp (ref "R175")
      (value "10k")
      (footprint "eagle-import:R0603")
      (libsource (lib "eagle-import") (part "rcl_R-US_R0603"))
    )
    (comp (ref "R176")
      (value "10k")
      (footprint "eagle-import:R0603")
      (libsource (lib "eagle-import") (part "rcl_R-US_R0603"))
    )
    (comp (ref "R177")
      (value "550")
      (footprint "eagle-import:R0603")
      (libsource (lib "eagle-import") (part "rcl_R-US_R0603"))
    )
    (comp (ref "R178")
      (value "10k")
      (footprint "eagle-import:R0603")
      (libsource (lib "eagle-import") (part "rcl_R-US_R0603"))
    )
    (comp (ref "R180")
      (value "180k")
      (footprint "eagle-import:R0603")
      (libsource (lib "eagle-import") (part "rcl_R-US_R0603"))
    )
    (comp (ref "R181")
      (value "10k")
      (footprint "eagle-import:R0603")
      (libsource (lib "eagle-import") (part "rcl_R-US_R0603"))
    )
    (comp (ref "R183")
      (value "100k")
      (footprint "eagle-import:R0402")
      (libsource (lib "eagle-import") (part "R-US_R0402"))
    )
    (comp (ref "R184")
      (value "550")
      (footprint "eagle-import:R0603")
      (libsource (lib "eagle-import") (part "rcl_R-US_R0603"))
    )
    (comp (ref "R185")
      (value "10k")
      (footprint "eagle-import:R0603")
      (libsource (lib "eagle-import") (part "rcl_R-US_R0603"))
    )
    (comp (ref "R186")
      (value "180k")
      (footprint "eagle-import:R0603")
      (libsource (lib "eagle-import") (part "rcl_R-US_R0603"))
    )
    (comp (ref "R187")
      (value "550")
      (footprint "eagle-import:R0603")
      (libsource (lib "eagle-import") (part "rcl_R-US_R0603"))
    )
    (comp (ref "R188")
      (value "10k")
      (footprint "eagle-import:R0603")
      (libsource (lib "eagle-import") (part "rcl_R-US_R0603"))
    )
    (comp (ref "R189")
      (value "100k")
      (footprint "eagle-import:R0603")
      (libsource (lib "eagle-import") (part "rcl_R-US_R0603"))
    )
    (comp (ref "R190")
      (value "100k")
      (footprint "eagle-import:R0603")
      (libsource (lib "eagle-import") (part "rcl_R-US_R0603"))
    )
    (comp (ref "R191")
      (value "63.5k")
      (footprint "eagle-import:R0603")
      (libsource (lib "eagle-import") (part "rcl_R-US_R0603"))
    )
    (comp (ref "R192")
      (value "63.5k")
      (footprint "eagle-import:R0603")
      (libsource (lib "eagle-import") (part "rcl_R-US_R0603"))
    )
    (comp (ref "R194")
      (value "63.5k")
      (footprint "eagle-import:R0603")
      (libsource (lib "eagle-import") (part "rcl_R-US_R0603"))
    )
    (comp (ref "U$1")
      (value "DMMT3904W-7-F")
      (footprint "eagle-import:SOT65P210X100-6N")
      (libsource (lib "eagle-import") (part "DMMT3904W-7-F"))
    )
    (comp (ref "U$3")
      (value "DMMT3904W-7-F")
      (footprint "eagle-import:SOT65P210X100-6N")
      (libsource (lib "eagle-import") (part "DMMT3904W-7-F"))
    )
    (comp (ref "U$4")
      (value "DMMT3904W-7-F")
      (footprint "eagle-import:SOT65P210X100-6N")
      (libsource (lib "eagle-import") (part "DMMT3904W-7-F"))
    )
    (comp (ref "U$7")
      (value "DMMT3904W-7-F")
      (footprint "eagle-import:SOT65P210X100-6N")
      (libsource (lib "eagle-import") (part "DMMT3904W-7-F"))
    )
    (comp (ref "U$8")
      (value "DMMT3904W-7-F")
      (footprint "eagle-import:SOT65P210X100-6N")
      (libsource (lib "eagle-import") (part "DMMT3904W-7-F"))
    )
    (comp (ref "U$9")
      (value "DMMT3904W-7-F")
      (footprint "eagle-import:SOT65P210X100-6N")
      (libsource (lib "eagle-import") (part "DMMT3904W-7-F"))
    )
    (comp (ref "U$15")
      (value "DMMT3904W-7-F")
      (footprint "eagle-import:SOT65P210X100-6N")
      (libsource (lib "eagle-import") (part "DMMT3904W-7-F"))
    )
    (comp (ref "U$16")
      (value "DMMT3904W-7-F")
      (footprint "eagle-import:SOT65P210X100-6N")
      (libsource (lib "eagle-import") (part "DMMT3904W-7-F"))
    )
    (comp (ref "U$19")
      (value "LM4819MMX")
      (footprint "eagle-import:SOP65P490X110-8N")
      (libsource (lib "eagle-import") (part "LM4819MMX"))
    )
    (comp (ref "U1")
      (value "TLV274IPWR")
      (footprint "eagle-import:SOP65P640X120-14N")
      (libsource (lib "eagle-import") (part "TLV274IPWR"))
    )
    (comp (ref "U2")
      (value "DMMT3906W-7-F")
      (footprint "eagle-import:SOT65P210X110-6N")
      (libsource (lib "eagle-import") (part "DMMT3906W-7-F"))
    )
    (comp (ref "U3")
      (value "DMMT3906W-7-F")
      (footprint "eagle-import:SOT65P210X110-6N")
      (libsource (lib "eagle-import") (part "DMMT3906W-7-F"))
    )
    (comp (ref "U4")
      (value "TLV274IPWR")
      (footprint "eagle-import:SOP65P640X120-14N")
      (libsource (lib "eagle-import") (part "TLV274IPWR"))
    )
    (comp (ref "U6")
      (value "DMMT3906W-7-F")
      (footprint "eagle-import:SOT65P210X110-6N")
      (libsource (lib "eagle-import") (part "DMMT3906W-7-F"))
    )
    (comp (ref "U7")
      (value "DMMT3906W-7-F")
      (footprint "eagle-import:SOT65P210X110-6N")
      (libsource (lib "eagle-import") (part "DMMT3906W-7-F"))
    )
    (comp (ref "U8")
      (value "TLV274IPWR")
      (footprint "eagle-import:SOP65P640X120-14N")
      (libsource (lib "eagle-import") (part "TLV274IPWR"))
    )
    (comp (ref "U9")
      (value "TLV274IPWR")
      (footprint "eagle-import:SOP65P640X120-14N")
      (libsource (lib "eagle-import") (part "TLV274IPWR"))
    )
    (comp (ref "U10")
      (value "DMMT3906W-7-F")
      (footprint "eagle-import:SOT65P210X110-6N")
      (libsource (lib "eagle-import") (part "DMMT3906W-7-F"))
    )
    (comp (ref "U11")
      (value "DMMT3906W-7-F")
      (footprint "eagle-import:SOT65P210X110-6N")
      (libsource (lib "eagle-import") (part "DMMT3906W-7-F"))
    )
    (comp (ref "U13")
      (value "TLV2471IDBVT")
      (footprint "eagle-import:SOT95P280X145-5N")
      (libsource (lib "eagle-import") (part "TLV2471IDBVT"))
    )
    (comp (ref "U14")
      (value "TLV274IPWR")
      (footprint "eagle-import:SOP65P640X120-14N")
      (libsource (lib "eagle-import") (part "TLV274IPWR"))
    )
    (comp (ref "U15")
      (value "TLV274IPWR")
      (footprint "eagle-import:SOP65P640X120-14N")
      (libsource (lib "eagle-import") (part "TLV274IPWR"))
    )
    (comp (ref "U16")
      (value "DMMT3906W-7-F")
      (footprint "eagle-import:SOT65P210X110-6N")
      (libsource (lib "eagle-import") (part "DMMT3906W-7-F"))
    )
    (comp (ref "U17")
      (value "DMMT3906W-7-F")
      (footprint "eagle-import:SOT65P210X110-6N")
      (libsource (lib "eagle-import") (part "DMMT3906W-7-F"))
    )
    (comp (ref "U18")
      (value "TLV274IPWR")
      (footprint "eagle-import:SOP65P640X120-14N")
      (libsource (lib "eagle-import") (part "TLV274IPWR"))
    )
    (comp (ref "U21")
      (value "DMMT3906W-7-F")
      (footprint "eagle-import:SOT65P210X110-6N")
      (libsource (lib "eagle-import") (part "DMMT3906W-7-F"))
    )
    (comp (ref "U22")
      (value "DMMT3906W-7-F")
      (footprint "eagle-import:SOT65P210X110-6N")
      (libsource (lib "eagle-import") (part "DMMT3906W-7-F"))
    )
    (comp (ref "U24")
      (value "DMMT3906W-7-F")
      (footprint "eagle-import:SOT65P210X110-6N")
      (libsource (lib "eagle-import") (part "DMMT3906W-7-F"))
    )
    (comp (ref "U25")
      (value "DMMT3906W-7-F")
      (footprint "eagle-import:SOT65P210X110-6N")
      (libsource (lib "eagle-import") (part "DMMT3906W-7-F"))
    )
    (comp (ref "U27")
      (value "DMMT3906W-7-F")
      (footprint "eagle-import:SOT65P210X110-6N")
      (libsource (lib "eagle-import") (part "DMMT3906W-7-F"))
    )
    (comp (ref "U28")
      (value "DMMT3906W-7-F")
      (footprint "eagle-import:SOT65P210X110-6N")
      (libsource (lib "eagle-import") (part "DMMT3906W-7-F"))
    )
    (comp (ref "U30")
      (value "DMMT3906W-7-F")
      (footprint "eagle-import:SOT65P210X110-6N")
      (libsource (lib "eagle-import") (part "DMMT3906W-7-F"))
    )
    (comp (ref "U31")
      (value "DMMT3906W-7-F")
      (footprint "eagle-import:SOT65P210X110-6N")
      (libsource (lib "eagle-import") (part "DMMT3906W-7-F"))
    )
    (comp (ref "1.2V")
      (value "TPB1,27")
      (footprint "eagle-import:B1,27")
      (libsource (lib "eagle-import") (part "TPB1,27"))
    )
    (comp (ref "2.5V")
      (value "TPB1,27")
      (footprint "eagle-import:B1,27")
      (libsource (lib "eagle-import") (part "TPB1,27"))
    )
    (comp (ref "3.3V")
      (value "TPB1,27")
      (footprint "eagle-import:B1,27")
      (libsource (lib "eagle-import") (part "TPB1,27"))
    )
    (comp (ref "C5")
      (value "10n")
      (footprint "eagle-import:C0603")
      (libsource (lib "eagle-import") (part "C-EUC0603"))
    )
    (comp (ref "C7")
      (value ".1u")
      (footprint "eagle-import:C0603")
      (libsource (lib "eagle-import") (part "C-EUC0603"))
    )
    (comp (ref "C8")
      (value ".1u")
      (footprint "eagle-import:C0603")
      (libsource (lib "eagle-import") (part "C-EUC0603"))
    )
    (comp (ref "C27")
      (value "1u")
      (footprint "eagle-import:C0603")
      (libsource (lib "eagle-import") (part "C-EUC0603"))
    )
    (comp (ref "C28")
      (value "1u")
      (footprint "eagle-import:C0603")
      (libsource (lib "eagle-import") (part "C-EUC0603"))
    )
    (comp (ref "C29")
      (value "10u")
      (footprint "eagle-import:C0603")
      (libsource (lib "eagle-import") (part "C-EUC0603"))
    )
    (comp (ref "C31")
      (value "1u")
      (footprint "eagle-import:C0603")
      (libsource (lib "eagle-import") (part "C-EUC0603"))
    )
    (comp (ref "C52")
      (value "10u")
      (footprint "eagle-import:C0603")
      (libsource (lib "eagle-import") (part "C-EUC0603"))
    )
    (comp (ref "C81")
      (value "10u")
      (footprint "eagle-import:C0603")
      (libsource (lib "eagle-import") (part "C-EUC0603"))
    )
    (comp (ref "CN2")
      (value "JST_2PIN-SMT-RA")
      (footprint "eagle-import:JST-PH-2-SMT-RA")
      (libsource (lib "eagle-import") (part "JST_2PIN-SMT-RA"))
    )
    (comp (ref "D1")
      (value "DIODE-SOD123")
      (footprint "eagle-import:SOD123")
      (libsource (lib "eagle-import") (part "DIODE-SOD123"))
    )
    (comp (ref "D3")
      (value "DIODE-SOD123")
      (footprint "eagle-import:SOD123")
      (libsource (lib "eagle-import") (part "DIODE-SOD123"))
    )
    (comp (ref "FB2")
      (value "FERRITE")
      (footprint "eagle-import:0603")
      (libsource (lib "eagle-import") (part "FERRITE"))
    )
    (comp (ref "IC2")
      (value "MCP73831/OT")
      (footprint "eagle-import:SOT23-5L")
      (libsource (lib "eagle-import") (part "MCP73831/OT"))
    )
    (comp (ref "LED1")
      (value "LEDCHIP-LED0805")
      (footprint "eagle-import:CHIP-LED0805")
      (libsource (lib "eagle-import") (part "LEDCHIP-LED0805"))
    )
    (comp (ref "R68")
      (value "10k")
      (footprint "eagle-import:R0603")
      (libsource (lib "eagle-import") (part "R-US_R0603"))
    )
    (comp (ref "R69")
      (value "1k")
      (footprint "eagle-import:R0603")
      (libsource (lib "eagle-import") (part "R-US_R0603"))
    )
    (comp (ref "R166")
      (value "10k")
      (footprint "eagle-import:R0603")
      (libsource (lib "eagle-import") (part "R-US_R0603"))
    )
    (comp (ref "R167")
      (value "10k")
      (footprint "eagle-import:R0603")
      (libsource (lib "eagle-import") (part "R-US_R0603"))
    )
    (comp (ref "R168")
      (value "100k")
      (footprint "eagle-import:R0603")
      (libsource (lib "eagle-import") (part "R-US_R0603"))
    )
    (comp (ref "S1")
      (value "EG1213")
      (footprint "eagle-import:EG1213")
      (libsource (lib "eagle-import") (part "EG1213"))
    )
    (comp (ref "U5")
      (value "mic5225-3.3")
      (footprint "eagle-import:SOT23-5")
      (libsource (lib "eagle-import") (part "VREG_SOT23-5"))
    )
    (comp (ref "U12")
      (value "TLV7101828DSER")
      (footprint "eagle-import:SON50P150X150X80-6N")
      (libsource (lib "eagle-import") (part "TLV7101828DSER"))
    )
    (comp (ref "C9")
      (value "10u")
      (footprint "eagle-import:C0603")
      (libsource (lib "eagle-import") (part "C-EUC0603"))
    )
    (comp (ref "C10")
      (value ".1u")
      (footprint "eagle-import:C0603")
      (libsource (lib "eagle-import") (part "C-EUC0603"))
    )
    (comp (ref "C11")
      (value "10u")
      (footprint "eagle-import:C0603")
      (libsource (lib "eagle-import") (part "C-EUC0603"))
    )
    (comp (ref "C12")
      (value ".1u")
      (footprint "eagle-import:C0603")
      (libsource (lib "eagle-import") (part "C-EUC0603"))
    )
    (comp (ref "C13")
      (value ".1u")
      (footprint "eagle-import:C0603")
      (libsource (lib "eagle-import") (part "C-EUC0603"))
    )
    (comp (ref "C14")
      (value ".1u")
      (footprint "eagle-import:C0603")
      (libsource (lib "eagle-import") (part "C-EUC0603"))
    )
    (comp (ref "C15")
      (value ".1u")
      (footprint "eagle-import:C0603")
      (libsource (lib "eagle-import") (part "C-EUC0603"))
    )
    (comp (ref "C16")
      (value ".1u")
      (footprint "eagle-import:C0603")
      (libsource (lib "eagle-import") (part "C-EUC0603"))
    )
    (comp (ref "C17")
      (value ".1u")
      (footprint "eagle-import:C0603")
      (libsource (lib "eagle-import") (part "C-EUC0603"))
    )
    (comp (ref "C18")
      (value ".1u")
      (footprint "eagle-import:C0603")
      (libsource (lib "eagle-import") (part "C-EUC0603"))
    )
    (comp (ref "C19")
      (value ".1u")
      (footprint "eagle-import:C0603")
      (libsource (lib "eagle-import") (part "C-EUC0603"))
    )
    (comp (ref "C20")
      (value ".1u")
      (footprint "eagle-import:C0603")
      (libsource (lib "eagle-import") (part "C-EUC0603"))
    )
    (comp (ref "C25")
      (value ".1u")
      (footprint "eagle-import:C0603")
      (libsource (lib "eagle-import") (part "C-EUC0603"))
    )
    (comp (ref "C33")
      (value ".1u")
      (footprint "eagle-import:C0603")
      (libsource (lib "eagle-import") (part "C-EUC0603"))
    )
    (comp (ref "C34")
      (value ".1u")
      (footprint "eagle-import:C0603")
      (libsource (lib "eagle-import") (part "C-EUC0603"))
    )
    (comp (ref "C41")
      (value ".1u")
      (footprint "eagle-import:C0603")
      (libsource (lib "eagle-import") (part "C-EUC0603"))
    )
    (comp (ref "C42")
      (value ".1u")
      (footprint "eagle-import:C0603")
      (libsource (lib "eagle-import") (part "C-EUC0603"))
    )
    (comp (ref "C48")
      (value ".1u")
      (footprint "eagle-import:C0603")
      (libsource (lib "eagle-import") (part "C-EUC0603"))
    )
    (comp (ref "C54")
      (value ".1u")
      (footprint "eagle-import:C0603")
      (libsource (lib "eagle-import") (part "C-EUC0603"))
    )
    (comp (ref "C68")
      (value "1u")
      (footprint "eagle-import:C0603")
      (libsource (lib "eagle-import") (part "C-EUC0603"))
    )
    (comp (ref "C69")
      (value "1u")
      (footprint "eagle-import:C0603")
      (libsource (lib "eagle-import") (part "C-EUC0603"))
    )
    (comp (ref "C70")
      (value "1u")
      (footprint "eagle-import:C0603")
      (libsource (lib "eagle-import") (part "C-EUC0603"))
    )
    (comp (ref "C71")
      (value "1u")
      (footprint "eagle-import:C0603")
      (libsource (lib "eagle-import") (part "C-EUC0603"))
    )
    (comp (ref "C80")
      (value "1u")
      (footprint "eagle-import:C0603")
      (libsource (lib "eagle-import") (part "C-EUC0603"))
    )
    (comp (ref "CLK")
      (value "TPB1,27")
      (footprint "eagle-import:B1,27")
      (libsource (lib "eagle-import") (part "TPB1,27"))
    )
    (comp (ref "D2")
      (value "CDBU0520")
      (footprint "eagle-import:SOD-523")
      (libsource (lib "eagle-import") (part "DIODESOD-523"))
    )
    (comp (ref "IC1")
      (value "74AHC1G125")
      (footprint "eagle-import:SOT23-5L")
      (libsource (lib "eagle-import") (part "74AHC1G125"))
    )
    (comp (ref "IC4")
      (value "74AHC1G125")
      (footprint "eagle-import:SOT23-5L")
      (libsource (lib "eagle-import") (part "74AHC1G125"))
    )
    (comp (ref "OSC0")
      (value "TPB1,27")
      (footprint "eagle-import:B1,27")
      (libsource (lib "eagle-import") (part "TPB1,27"))
    )
    (comp (ref "OSC1")
      (value "TPB1,27")
      (footprint "eagle-import:B1,27")
      (libsource (lib "eagle-import") (part "TPB1,27"))
    )
    (comp (ref "OSC2")
      (value "TPB1,27")
      (footprint "eagle-import:B1,27")
      (libsource (lib "eagle-import") (part "TPB1,27"))
    )
    (comp (ref "R8")
      (value "100R")
      (footprint "eagle-import:R0603")
      (libsource (lib "eagle-import") (part "rcl_R-US_R0603"))
    )
    (comp (ref "R9")
      (value "100R")
      (footprint "eagle-import:R0603")
      (libsource (lib "eagle-import") (part "rcl_R-US_R0603"))
    )
    (comp (ref "R10")
      (value "10k")
      (footprint "eagle-import:R0603")
      (libsource (lib "eagle-import") (part "rcl_R-US_R0603"))
    )
    (comp (ref "R11")
      (value "10k")
      (footprint "eagle-import:R0603")
      (libsource (lib "eagle-import") (part "rcl_R-US_R0603"))
    )
    (comp (ref "R30")
      (value "10k")
      (footprint "eagle-import:R0603")
      (libsource (lib "eagle-import") (part "rcl_R-US_R0603"))
    )
    (comp (ref "R31")
      (value "20k")
      (footprint "eagle-import:R0603")
      (libsource (lib "eagle-import") (part "rcl_R-US_R0603"))
    )
    (comp (ref "R32")
      (value "20k")
      (footprint "eagle-import:R0603")
      (libsource (lib "eagle-import") (part "rcl_R-US_R0603"))
    )
    (comp (ref "R33")
      (value "20k")
      (footprint "eagle-import:R0603")
      (libsource (lib "eagle-import") (part "rcl_R-US_R0603"))
    )
    (comp (ref "R57")
      (value "10k")
      (footprint "eagle-import:R0603")
      (libsource (lib "eagle-import") (part "rcl_R-US_R0603"))
    )
    (comp (ref "R58")
      (value "10k")
      (footprint "eagle-import:R0603")
      (libsource (lib "eagle-import") (part "rcl_R-US_R0603"))
    )
    (comp (ref "R59")
      (value "10k")
      (footprint "eagle-import:R0603")
      (libsource (lib "eagle-import") (part "rcl_R-US_R0603"))
    )
    (comp (ref "R60")
      (value "10k")
      (footprint "eagle-import:R0603")
      (libsource (lib "eagle-import") (part "rcl_R-US_R0603"))
    )
    (comp (ref "R61")
      (value "1k")
      (footprint "eagle-import:R0603")
      (libsource (lib "eagle-import") (part "rcl_R-US_R0603"))
    )
    (comp (ref "RAM1")
      (value "N25Q032A13ESC40FTR")
      (footprint "eagle-import:SO08")
      (libsource (lib "eagle-import") (part "N25Q032A13ESC40FTR"))
    )
    (comp (ref "RN3")
      (value "33")
      (footprint "eagle-import:0603-ARC")
      (libsource (lib "eagle-import") (part "4R-N0603-ARC"))
    )
    (comp (ref "RN4")
      (value "33")
      (footprint "eagle-import:0603-ARC")
      (libsource (lib "eagle-import") (part "4R-N0603-ARC"))
    )
    (comp (ref "RN5")
      (value "10k")
      (footprint "eagle-import:0603-ARC")
      (libsource (lib "eagle-import") (part "4R-N0603-ARC"))
    )
    (comp (ref "RN6")
      (value "20k")
      (footprint "eagle-import:742-16")
      (libsource (lib "eagle-import") (part "742-16_S"))
    )
    (comp (ref "RN7")
      (value "20k")
      (footprint "eagle-import:742-16")
      (libsource (lib "eagle-import") (part "742-16_S"))
    )
    (comp (ref "RN8")
      (value "10k")
      (footprint "eagle-import:742-16")
      (libsource (lib "eagle-import") (part "742-16_S"))
    )
    (comp (ref "RN9")
      (value "10k")
      (footprint "eagle-import:742-16")
      (libsource (lib "eagle-import") (part "742-16_S"))
    )
    (comp (ref "RN10")
      (value "20k")
      (footprint "eagle-import:742-16")
      (libsource (lib "eagle-import") (part "742-16_S"))
    )
    (comp (ref "RN11")
      (value "20k")
      (footprint "eagle-import:742-16")
      (libsource (lib "eagle-import") (part "742-16_S"))
    )
    (comp (ref "RN12")
      (value "10k")
      (footprint "eagle-import:742-16")
      (libsource (lib "eagle-import") (part "742-16_S"))
    )
    (comp (ref "RN13")
      (value "10k")
      (footprint "eagle-import:742-16")
      (libsource (lib "eagle-import") (part "742-16_S"))
    )
    (comp (ref "RN14")
      (value "10k")
      (footprint "eagle-import:742-16")
      (libsource (lib "eagle-import") (part "742-16_S"))
    )
    (comp (ref "RN15")
      (value "10k")
      (footprint "eagle-import:742-16")
      (libsource (lib "eagle-import") (part "742-16_S"))
    )
    (comp (ref "RN16")
      (value "10k")
      (footprint "eagle-import:742-16")
      (libsource (lib "eagle-import") (part "742-16_S"))
    )
    (comp (ref "RN17")
      (value "10k")
      (footprint "eagle-import:742-16")
      (libsource (lib "eagle-import") (part "742-16_S"))
    )
    (comp (ref "U$2")
      (value "ICE40HX4K")
      (footprint "eagle-import:TQ144")
      (libsource (lib "eagle-import") (part "ICE40HX4K"))
    )
    (comp (ref "U$5")
      (value "SIT1602")
      (footprint "eagle-import:SMD-43.2X2.5")
      (libsource (lib "eagle-import") (part "SIT1602"))
    )
    (comp (ref "C30")
      (value "1u")
      (footprint "eagle-import:C0603")
      (libsource (lib "eagle-import") (part "C-EUC0603"))
    )
    (comp (ref "C32")
      (value "1uF")
      (footprint "eagle-import:0603-NO")
      (libsource (lib "eagle-import") (part "CAP_CERAMIC0603_NO"))
    )
    (comp (ref "C49")
      (value "22pF")
      (footprint "eagle-import:0603-NO")
      (libsource (lib "eagle-import") (part "CAP_CERAMIC0603_NO"))
    )
    (comp (ref "C50")
      (value "22pF")
      (footprint "eagle-import:0603-NO")
      (libsource (lib "eagle-import") (part "CAP_CERAMIC0603_NO"))
    )
    (comp (ref "C51")
      (value "10u")
      (footprint "eagle-import:C0603")
      (libsource (lib "eagle-import") (part "C-EUC0603"))
    )
    (comp (ref "CN1")
      (value "AUDIO_3.5MMJACK")
      (footprint "eagle-import:4UCONN_19269")
      (libsource (lib "eagle-import") (part "AUDIO_3.5MMJACK"))
    )
    (comp (ref "D10")
      (value "DIODESOD-523")
      (footprint "eagle-import:SOD-523")
      (libsource (lib "eagle-import") (part "DIODESOD-523"))
    )
    (comp (ref "IC3")
      (value "74AHC1G125")
      (footprint "eagle-import:SOT23-5L")
      (libsource (lib "eagle-import") (part "74AHC1G125"))
    )
    (comp (ref "J100")
      (value "PINHEAD-2x5-P1.27")
      (footprint "eagle-import:PINHEAD_2X05_127")
      (libsource (lib "eagle-import") (part "0171_PH127-205DF055G00AROUND-PADS"))
    )
    (comp (ref "JP1")
      (value "PINHD-2X20")
      (footprint "eagle-import:2X20")
      (libsource (lib "eagle-import") (part "PINHD-2X20"))
    )
    (comp (ref "L")
      (value "RED")
      (footprint "eagle-import:CHIP-LED0805")
      (libsource (lib "eagle-import") (part "LEDCHIP-LED0805"))
    )
    (comp (ref "OK1")
      (value "6N137")
      (footprint "eagle-import:DIL8-SMD")
      (libsource (lib "eagle-import") (part "6N137"))
    )
    (comp (ref "R64")
      (value "10k")
      (footprint "eagle-import:R0603")
      (libsource (lib "eagle-import") (part "R-US_R0603"))
    )
    (comp (ref "R164")
      (value "2.2k")
      (footprint "eagle-import:R0603")
      (libsource (lib "eagle-import") (part "R-US_R0603"))
    )
    (comp (ref "R165")
      (value "220")
      (footprint "eagle-import:R0603")
      (libsource (lib "eagle-import") (part "R-US_R0603"))
    )
    (comp (ref "R179")
      (value "330")
      (footprint "eagle-import:R0603")
      (libsource (lib "eagle-import") (part "R-US_R0603"))
    )
    (comp (ref "R182")
      (value "10k")
      (footprint "eagle-import:R0603")
      (libsource (lib "eagle-import") (part "R-US_R0603"))
    )
    (comp (ref "RN2")
      (value "33")
      (footprint "eagle-import:0603-ARC")
      (libsource (lib "eagle-import") (part "4R-N0603-ARC"))
    )
    (comp (ref "SAMD21")
      (value "ATSAMD21G18_QFN")
      (footprint "eagle-import:TQFN48_7MM")
      (libsource (lib "eagle-import") (part "ATSAMD21J_QFN"))
    )
    (comp (ref "SW1")
      (value "SPST_TACT-KMR2")
      (footprint "eagle-import:KMR2")
      (libsource (lib "eagle-import") (part "SPST_TACT-KMR2"))
    )
    (comp (ref "X2")
      (value "32.768")
      (footprint "eagle-import:XTAL3215")
      (libsource (lib "eagle-import") (part "XTAL-3.2X1.5"))
    )
    (comp (ref "X3")
      (value "microUSB")
      (footprint "eagle-import:4UCONN_20329_V2")
      (libsource (lib "eagle-import") (part "USB_MICRO_20329_V2"))
    )
    (comp (ref "X4")
      (value "microsd")
      (footprint "eagle-import:MICROSD")
      (libsource (lib "eagle-import") (part "MICROSD"))
    )
  )
  (nets
    (net (code "1") (name "+1.2V") (class "Default")
      (node (ref "1.2V") (pin "TP") (pinfunction "TP_TP") (pintype "input"))
      (node (ref "C28") (pin "2") (pinfunction "2_2") (pintype "passive"))
      (node (ref "C41") (pin "2") (pinfunction "2_2") (pintype "passive"))
      (node (ref "C42") (pin "2") (pinfunction "2_2") (pintype "passive"))
      (node (ref "C48") (pin "2") (pinfunction "2_2") (pintype "passive"))
      (node (ref "C54") (pin "2") (pinfunction "2_2") (pintype "passive"))
      (node (ref "R8") (pin "2") (pinfunction "2_2") (pintype "passive"))
      (node (ref "R9") (pin "2") (pinfunction "2_2") (pintype "passive"))
      (node (ref "U$2") (pin "111") (pinfunction "VCC_111") (pintype "bidirectional"))
      (node (ref "U$2") (pin "27") (pinfunction "VCC_27") (pintype "bidirectional"))
      (node (ref "U$2") (pin "40") (pinfunction "VCC_40") (pintype "bidirectional"))
      (node (ref "U$2") (pin "92") (pinfunction "VCC_92") (pintype "bidirectional"))
      (node (ref "U12") (pin "6") (pinfunction "OUT1_6") (pintype "output"))
    )
    (net (code "2") (name "+2.5V") (class "Default")
      (node (ref "2.5V") (pin "TP") (pinfunction "TP_TP") (pintype "input"))
      (node (ref "C27") (pin "2") (pinfunction "2_2") (pintype "passive"))
      (node (ref "U12") (pin "5") (pinfunction "OUT2_5") (pintype "output"))
    )
    (net (code "3") (name "+3.3V") (class "Default")
      (node (ref "C13") (pin "2") (pinfunction "2_2") (pintype "passive"))
      (node (ref "C14") (pin "2") (pinfunction "2_2") (pintype "passive"))
      (node (ref "C15") (pin "2") (pinfunction "2_2") (pintype "passive"))
      (node (ref "C16") (pin "2") (pinfunction "2_2") (pintype "passive"))
      (node (ref "C17") (pin "2") (pinfunction "2_2") (pintype "passive"))
      (node (ref "C18") (pin "2") (pinfunction "2_2") (pintype "passive"))
      (node (ref "C19") (pin "2") (pinfunction "2_2") (pintype "passive"))
      (node (ref "C20") (pin "2") (pinfunction "2_2") (pintype "passive"))
      (node (ref "C25") (pin "2") (pinfunction "2_2") (pintype "passive"))
      (node (ref "C33") (pin "2") (pinfunction "2_2") (pintype "passive"))
      (node (ref "C34") (pin "2") (pinfunction "2_2") (pintype "passive"))
      (node (ref "C51") (pin "1") (pinfunction "1_1") (pintype "passive"))
      (node (ref "C62") (pin "1") (pinfunction "1_1") (pintype "passive"))
      (node (ref "C64") (pin "1") (pinfunction "1_1") (pintype "passive"))
      (node (ref "C66") (pin "1") (pinfunction "1_1") (pintype "passive"))
      (node (ref "C73") (pin "1") (pinfunction "1_1") (pintype "passive"))
      (node (ref "C74") (pin "1") (pinfunction "1_1") (pintype "passive"))
      (node (ref "C77") (pin "1") (pinfunction "1_1") (pintype "passive"))
      (node (ref "C78") (pin "1") (pinfunction "1_1") (pintype "passive"))
      (node (ref "C82") (pin "1") (pinfunction "1_1") (pintype "passive"))
      (node (ref "D2") (pin "A") (pinfunction "A_A") (pintype "passive"))
      (node (ref "IC1") (pin "5") (pinfunction "VCC_5") (pintype "power_in"))
      (node (ref "IC3") (pin "5") (pinfunction "VCC_5") (pintype "power_in"))
      (node (ref "IC4") (pin "5") (pinfunction "VCC_5") (pintype "power_in"))
      (node (ref "J100") (pin "1") (pinfunction "1_1") (pintype "passive"))
      (node (ref "JP1") (pin "1") (pinfunction "1_1") (pintype "passive"))
      (node (ref "JP1") (pin "38") (pinfunction "38_38") (pintype "passive"))
      (node (ref "OK1") (pin "8") (pinfunction "VCC_8") (pintype "passive"))
      (node (ref "R10") (pin "2") (pinfunction "2_2") (pintype "passive"))
      (node (ref "R11") (pin "2") (pinfunction "2_2") (pintype "passive"))
      (node (ref "R166") (pin "2") (pinfunction "2_2") (pintype "passive"))
      (node (ref "R167") (pin "2") (pinfunction "2_2") (pintype "passive"))
      (node (ref "R172") (pin "1") (pinfunction "1_1") (pintype "passive"))
      (node (ref "R176") (pin "2") (pinfunction "2_2") (pintype "passive"))
      (node (ref "R181") (pin "1") (pinfunction "1_1") (pintype "passive"))
      (node (ref "R182") (pin "1") (pinfunction "1_1") (pintype "passive"))
      (node (ref "R188") (pin "1") (pinfunction "1_1") (pintype "passive"))
      (node (ref "R189") (pin "1") (pinfunction "1_1") (pintype "passive"))
      (node (ref "R57") (pin "2") (pinfunction "2_2") (pintype "passive"))
      (node (ref "R58") (pin "2") (pinfunction "2_2") (pintype "passive"))
      (node (ref "R59") (pin "2") (pinfunction "2_2") (pintype "passive"))
      (node (ref "R60") (pin "2") (pinfunction "2_2") (pintype "passive"))
      (node (ref "R61") (pin "2") (pinfunction "2_2") (pintype "passive"))
      (node (ref "R64") (pin "2") (pinfunction "2_2") (pintype "passive"))
      (node (ref "R67") (pin "2") (pinfunction "2_2") (pintype "passive"))
      (node (ref "RAM1") (pin "8") (pinfunction "VCC_8") (pintype "bidirectional"))
      (node (ref "SAMD21") (pin "17") (pinfunction "VDDIO_17") (pintype "power_in"))
      (node (ref "SAMD21") (pin "36") (pinfunction "VDDIO_36") (pintype "power_in"))
      (node (ref "SAMD21") (pin "44") (pinfunction "VDDIN_44") (pintype "power_in"))
      (node (ref "SAMD21") (pin "6") (pinfunction "VDDA_6") (pintype "power_in"))
      (node (ref "U$19") (pin "6") (pinfunction "VDD_6") (pintype "bidirectional"))
      (node (ref "U$2") (pin "100") (pinfunction "VCCIO_1_2_100") (pintype "bidirectional"))
      (node (ref "U$2") (pin "123") (pinfunction "VCCIO_0_123") (pintype "bidirectional"))
      (node (ref "U$2") (pin "131") (pinfunction "VCCIO_0_2_131") (pintype "bidirectional"))
      (node (ref "U$2") (pin "30") (pinfunction "VCCIO_3_2_30") (pintype "bidirectional"))
      (node (ref "U$2") (pin "46") (pinfunction "VCCIO_2_46") (pintype "bidirectional"))
      (node (ref "U$2") (pin "57") (pinfunction "VCCIO2_2_57") (pintype "bidirectional"))
      (node (ref "U$2") (pin "6") (pinfunction "VCCIO_3_6") (pintype "bidirectional"))
      (node (ref "U$2") (pin "72") (pinfunction "VCC_SPI_72") (pintype "bidirectional"))
      (node (ref "U$2") (pin "89") (pinfunction "VCCIO_1_89") (pintype "bidirectional"))
      (node (ref "U$5") (pin "4") (pinfunction "VDD_4") (pintype "bidirectional"))
      (node (ref "U1") (pin "4") (pinfunction "V+_4") (pintype "bidirectional"))
      (node (ref "U11") (pin "4") (pinfunction "E_4") (pintype "passive"))
      (node (ref "U11") (pin "5") (pinfunction "E_5") (pintype "passive"))
      (node (ref "U12") (pin "2") (pinfunction "IN_2") (pintype "power_in"))
      (node (ref "U13") (pin "5") (pinfunction "V+_5") (pintype "bidirectional"))
      (node (ref "U14") (pin "4") (pinfunction "V+_4") (pintype "bidirectional"))
      (node (ref "U15") (pin "4") (pinfunction "V+_4") (pintype "bidirectional"))
      (node (ref "U17") (pin "4") (pinfunction "E_4") (pintype "passive"))
      (node (ref "U17") (pin "5") (pinfunction "E_5") (pintype "passive"))
      (node (ref "U18") (pin "4") (pinfunction "V+_4") (pintype "bidirectional"))
      (node (ref "U22") (pin "4") (pinfunction "E_4") (pintype "passive"))
      (node (ref "U22") (pin "5") (pinfunction "E_5") (pintype "passive"))
      (node (ref "U25") (pin "4") (pinfunction "E_4") (pintype "passive"))
      (node (ref "U25") (pin "5") (pinfunction "E_5") (pintype "passive"))
      (node (ref "U28") (pin "4") (pinfunction "E_4") (pintype "passive"))
      (node (ref "U28") (pin "5") (pinfunction "E_5") (pintype "passive"))
      (node (ref "U3") (pin "4") (pinfunction "E_4") (pintype "passive"))
      (node (ref "U3") (pin "5") (pinfunction "E_5") (pintype "passive"))
      (node (ref "U31") (pin "4") (pinfunction "E_4") (pintype "passive"))
      (node (ref "U31") (pin "5") (pinfunction "E_5") (pintype "passive"))
      (node (ref "U4") (pin "4") (pinfunction "V+_4") (pintype "bidirectional"))
      (node (ref "U7") (pin "4") (pinfunction "E_4") (pintype "passive"))
      (node (ref "U7") (pin "5") (pinfunction "E_5") (pintype "passive"))
      (node (ref "U8") (pin "4") (pinfunction "V+_4") (pintype "bidirectional"))
      (node (ref "U9") (pin "4") (pinfunction "V+_4") (pintype "bidirectional"))
      (node (ref "X4") (pin "4") (pinfunction "SD_VDD_4") (pintype "power_in"))
    )
    (net (code "4") (name "2P") (class "Default")
      (node (ref "C23") (pin "2") (pinfunction "2_2") (pintype "passive"))
      (node (ref "C24") (pin "2") (pinfunction "2_2") (pintype "passive"))
      (node (ref "JP1") (pin "39") (pinfunction "39_39") (pintype "passive"))
      (node (ref "R16") (pin "2") (pinfunction "2_2") (pintype "passive"))
      (node (ref "U15") (pin "14") (pinfunction "OUT_14") (pintype "output"))
    )
    (net (code "5") (name "4P") (class "Default")
      (node (ref "C21") (pin "2") (pinfunction "2_2") (pintype "passive"))
      (node (ref "C40") (pin "2") (pinfunction "2_2") (pintype "passive"))
      (node (ref "C47") (pin "1") (pinfunction "1_1") (pintype "passive"))
      (node (ref "C55") (pin "2") (pinfunction "2_2") (pintype "passive"))
      (node (ref "JP1") (pin "40") (pinfunction "40_40") (pintype "passive"))
      (node (ref "R28") (pin "2") (pinfunction "2_2") (pintype "passive"))
      (node (ref "U15") (pin "8") (pinfunction "OUT_8") (pintype "output"))
    )
    (net (code "6") (name "A1") (class "Default")
      (node (ref "JP1") (pin "16") (pinfunction "16_16") (pintype "passive"))
      (node (ref "SAMD21") (pin "7") (pinfunction "PB08/I8/AIN2/SERCOM4.0_7") (pintype "bidirectional"))
    )
    (net (code "7") (name "A2") (class "Default")
      (node (ref "JP1") (pin "15") (pinfunction "15_15") (pintype "passive"))
      (node (ref "SAMD21") (pin "8") (pinfunction "PB09/I9/AIN3/SERCOM4.1_8") (pintype "bidirectional"))
    )
    (net (code "8") (name "A5") (class "Default")
      (node (ref "JP1") (pin "4") (pinfunction "4_4") (pintype "passive"))
      (node (ref "SAMD21") (pin "47") (pinfunction "PB02/I2/AIN10/SERCOM5.0_47") (pintype "bidirectional"))
    )
    (net (code "9") (name "AGND") (class "Default")
      (node (ref "C6") (pin "+") (pinfunction "+_+") (pintype "passive"))
      (node (ref "C60") (pin "2") (pinfunction "2_2") (pintype "passive"))
      (node (ref "C61") (pin "1") (pinfunction "1_1") (pintype "passive"))
      (node (ref "C62") (pin "2") (pinfunction "2_2") (pintype "passive"))
      (node (ref "C63") (pin "1") (pinfunction "1_1") (pintype "passive"))
      (node (ref "C64") (pin "2") (pinfunction "2_2") (pintype "passive"))
      (node (ref "C65") (pin "1") (pinfunction "1_1") (pintype "passive"))
      (node (ref "C66") (pin "2") (pinfunction "2_2") (pintype "passive"))
      (node (ref "C67") (pin "1") (pinfunction "1_1") (pintype "passive"))
      (node (ref "C72") (pin "1") (pinfunction "1_1") (pintype "passive"))
      (node (ref "C73") (pin "2") (pinfunction "2_2") (pintype "passive"))
      (node (ref "C74") (pin "2") (pinfunction "2_2") (pintype "passive"))
      (node (ref "C75") (pin "1") (pinfunction "1_1") (pintype "passive"))
      (node (ref "C76") (pin "1") (pinfunction "1_1") (pintype "passive"))
      (node (ref "C77") (pin "2") (pinfunction "2_2") (pintype "passive"))
      (node (ref "C78") (pin "2") (pinfunction "2_2") (pintype "passive"))
      (node (ref "C79") (pin "1") (pinfunction "1_1") (pintype "passive"))
      (node (ref "C89") (pin "2") (pinfunction "2_2") (pintype "passive"))
      (node (ref "JP1") (pin "35") (pinfunction "35_35") (pintype "passive"))
      (node (ref "R12") (pin "1") (pinfunction "1_1") (pintype "passive"))
      (node (ref "R169") (pin "2") (pinfunction "2_2") (pintype "passive"))
      (node (ref "R173") (pin "1") (pinfunction "1_1") (pintype "passive"))
      (node (ref "R177") (pin "2") (pinfunction "2_2") (pintype "passive"))
      (node (ref "R183") (pin "1") (pinfunction "1_1") (pintype "passive"))
      (node (ref "R184") (pin "1") (pinfunction "1_1") (pintype "passive"))
      (node (ref "R187") (pin "1") (pinfunction "1_1") (pintype "passive"))
      (node (ref "R41") (pin "2") (pinfunction "2_2") (pintype "passive"))
      (node (ref "R73") (pin "1") (pinfunction "1_1") (pintype "passive"))
      (node (ref "U$1") (pin "1") (pinfunction "B_1") (pintype "passive"))
      (node (ref "U$15") (pin "1") (pinfunction "B_1") (pintype "passive"))
      (node (ref "U$16") (pin "1") (pinfunction "B_1") (pintype "passive"))
      (node (ref "U$3") (pin "1") (pinfunction "B_1") (pintype "passive"))
      (node (ref "U$4") (pin "1") (pinfunction "B_1") (pintype "passive"))
      (node (ref "U$7") (pin "1") (pinfunction "B_1") (pintype "passive"))
      (node (ref "U$8") (pin "1") (pinfunction "B_1") (pintype "passive"))
      (node (ref "U$9") (pin "1") (pinfunction "B_1") (pintype "passive"))
      (node (ref "U1") (pin "10") (pinfunction "+IN_10") (pintype "input"))
      (node (ref "U1") (pin "12") (pinfunction "+IN_12") (pintype "input"))
      (node (ref "U1") (pin "3") (pinfunction "+IN_3") (pintype "input"))
      (node (ref "U1") (pin "5") (pinfunction "+IN_5") (pintype "input"))
      (node (ref "U10") (pin "2") (pinfunction "B_2") (pintype "passive"))
      (node (ref "U14") (pin "10") (pinfunction "+IN_10") (pintype "input"))
      (node (ref "U14") (pin "12") (pinfunction "+IN_12") (pintype "input"))
      (node (ref "U14") (pin "3") (pinfunction "+IN_3") (pintype "input"))
      (node (ref "U14") (pin "5") (pinfunction "+IN_5") (pintype "input"))
      (node (ref "U15") (pin "10") (pinfunction "+IN_10") (pintype "input"))
      (node (ref "U15") (pin "12") (pinfunction "+IN_12") (pintype "input"))
      (node (ref "U15") (pin "3") (pinfunction "+IN_3") (pintype "input"))
      (node (ref "U15") (pin "5") (pinfunction "+IN_5") (pintype "input"))
      (node (ref "U16") (pin "2") (pinfunction "B_2") (pintype "passive"))
      (node (ref "U18") (pin "13") (pinfunction "-IN_13") (pintype "input"))
      (node (ref "U18") (pin "14") (pinfunction "OUT_14") (pintype "output"))
      (node (ref "U18") (pin "3") (pinfunction "+IN_3") (pintype "input"))
      (node (ref "U2") (pin "2") (pinfunction "B_2") (pintype "passive"))
      (node (ref "U21") (pin "2") (pinfunction "B_2") (pintype "passive"))
      (node (ref "U24") (pin "2") (pinfunction "B_2") (pintype "passive"))
      (node (ref "U27") (pin "2") (pinfunction "B_2") (pintype "passive"))
      (node (ref "U30") (pin "2") (pinfunction "B_2") (pintype "passive"))
      (node (ref "U6") (pin "2") (pinfunction "B_2") (pintype "passive"))
      (node (ref "U8") (pin "10") (pinfunction "+IN_10") (pintype "input"))
      (node (ref "U8") (pin "12") (pinfunction "+IN_12") (pintype "input"))
      (node (ref "U8") (pin "3") (pinfunction "+IN_3") (pintype "input"))
      (node (ref "U8") (pin "5") (pinfunction "+IN_5") (pintype "input"))
      (node (ref "U9") (pin "10") (pinfunction "+IN_10") (pintype "input"))
      (node (ref "U9") (pin "12") (pinfunction "+IN_12") (pintype "input"))
      (node (ref "U9") (pin "3") (pinfunction "+IN_3") (pintype "input"))
      (node (ref "U9") (pin "5") (pinfunction "+IN_5") (pintype "input"))
    )
    (net (code "10") (name "AREF") (class "Default")
      (node (ref "C30") (pin "1") (pinfunction "1_1") (pintype "passive"))
      (node (ref "SAMD21") (pin "4") (pinfunction "PA03/EINT3/VREFA/AIN1_4") (pintype "bidirectional"))
    )
    (net (code "11") (name "AUDIO_OUT") (class "Default")
      (node (ref "C89") (pin "1") (pinfunction "1_1") (pintype "passive"))
      (node (ref "FB1") (pin "2") (pinfunction "P$2_2") (pintype "passive"))
      (node (ref "JP1") (pin "36") (pinfunction "36_36") (pintype "passive"))
      (node (ref "R66") (pin "2") (pinfunction "2_2") (pintype "passive"))
    )
    (net (code "12") (name "AUX") (class "Default")
      (node (ref "JP1") (pin "33") (pinfunction "33_33") (pintype "passive"))
      (node (ref "R194") (pin "2") (pinfunction "2_2") (pintype "passive"))
    )
    (net (code "13") (name "BIT0_0") (class "Default")
      (node (ref "RN7") (pin "8") (pinfunction "1_8") (pintype "passive"))
      (node (ref "U$2") (pin "1") (pinfunction "IOL_2A_1") (pintype "bidirectional"))
    )
    (net (code "14") (name "BIT0_1") (class "Default")
      (node (ref "RN11") (pin "8") (pinfunction "1_8") (pintype "passive"))
      (node (ref "U$2") (pin "110") (pinfunction "IOT_168_110") (pintype "bidirectional"))
    )
    (net (code "15") (name "BIT0_2") (class "Default")
      (node (ref "RN15") (pin "1") (pinfunction "1_1") (pintype "passive"))
      (node (ref "U$2") (pin "63") (pinfunction "IOB_103_CBSEL0_63") (pintype "bidirectional"))
    )
    (net (code "16") (name "BIT1_0") (class "Default")
      (node (ref "RN7") (pin "7") (pinfunction "1_7") (pintype "passive"))
      (node (ref "U$2") (pin "2") (pinfunction "IOL_2B_2") (pintype "bidirectional"))
    )
    (net (code "17") (name "BIT1_1") (class "Default")
      (node (ref "RN11") (pin "7") (pinfunction "1_7") (pintype "passive"))
      (node (ref "U$2") (pin "112") (pinfunction "IOT_169_112") (pintype "bidirectional"))
    )
    (net (code "18") (name "BIT1_2") (class "Default")
      (node (ref "RN15") (pin "2") (pinfunction "1_2") (pintype "passive"))
      (node (ref "U$2") (pin "62") (pinfunction "IOB_102_62") (pintype "bidirectional"))
    )
    (net (code "19") (name "BIT2_0") (class "Default")
      (node (ref "RN7") (pin "6") (pinfunction "1_6") (pintype "passive"))
      (node (ref "U$2") (pin "3") (pinfunction "IOL_3A_3") (pintype "bidirectional"))
    )
    (net (code "20") (name "BIT2_1") (class "Default")
      (node (ref "RN11") (pin "6") (pinfunction "1_6") (pintype "passive"))
      (node (ref "U$2") (pin "113") (pinfunction "IOT_170_113") (pintype "bidirectional"))
    )
    (net (code "21") (name "BIT2_2") (class "Default")
      (node (ref "RN15") (pin "3") (pinfunction "1_3") (pintype "passive"))
      (node (ref "U$2") (pin "61") (pinfunction "IOB_96_61") (pintype "bidirectional"))
    )
    (net (code "22") (name "BIT3_0") (class "Default")
      (node (ref "RN7") (pin "5") (pinfunction "1_5") (pintype "passive"))
      (node (ref "U$2") (pin "4") (pinfunction "IOL_3B_4") (pintype "bidirectional"))
    )
    (net (code "23") (name "BIT3_1") (class "Default")
      (node (ref "RN11") (pin "5") (pinfunction "1_5") (pintype "passive"))
      (node (ref "U$2") (pin "114") (pinfunction "IOT_171_114") (pintype "bidirectional"))
    )
    (net (code "24") (name "BIT3_2") (class "Default")
      (node (ref "RN15") (pin "4") (pinfunction "1_4") (pintype "passive"))
      (node (ref "U$2") (pin "60") (pinfunction "IOB_95_60") (pintype "bidirectional"))
    )
    (net (code "25") (name "BIT4_0") (class "Default")
      (node (ref "RN7") (pin "4") (pinfunction "1_4") (pintype "passive"))
      (node (ref "U$2") (pin "7") (pinfunction "IOL_4A_7") (pintype "bidirectional"))
    )
    (net (code "26") (name "BIT4_1") (class "Default")
      (node (ref "RN11") (pin "4") (pinfunction "1_4") (pintype "passive"))
      (node (ref "U$2") (pin "115") (pinfunction "IOT_172_115") (pintype "bidirectional"))
    )
    (net (code "27") (name "BIT4_2") (class "Default")
      (node (ref "RN15") (pin "5") (pinfunction "1_5") (pintype "passive"))
      (node (ref "U$2") (pin "56") (pinfunction "IOB_94_56") (pintype "bidirectional"))
    )
    (net (code "28") (name "BIT5_0") (class "Default")
      (node (ref "RN7") (pin "3") (pinfunction "1_3") (pintype "passive"))
      (node (ref "U$2") (pin "8") (pinfunction "IOL_4B_8") (pintype "bidirectional"))
    )
    (net (code "29") (name "BIT5_1") (class "Default")
      (node (ref "RN11") (pin "3") (pinfunction "1_3") (pintype "passive"))
      (node (ref "U$2") (pin "116") (pinfunction "IOT_173_116") (pintype "bidirectional"))
    )
    (net (code "30") (name "BIT5_2") (class "Default")
      (node (ref "RN15") (pin "6") (pinfunction "1_6") (pintype "passive"))
      (node (ref "U$2") (pin "55") (pinfunction "IOB_91_55") (pintype "bidirectional"))
    )
    (net (code "31") (name "BIT6_0") (class "Default")
      (node (ref "RN7") (pin "2") (pinfunction "1_2") (pintype "passive"))
      (node (ref "U$2") (pin "9") (pinfunction "IOL_5A_9") (pintype "bidirectional"))
    )
    (net (code "32") (name "BIT6_1") (class "Default")
      (node (ref "RN11") (pin "2") (pinfunction "1_2") (pintype "passive"))
      (node (ref "U$2") (pin "117") (pinfunction "IOT_174_117") (pintype "bidirectional"))
    )
    (net (code "33") (name "BIT6_2") (class "Default")
      (node (ref "RN15") (pin "7") (pinfunction "1_7") (pintype "passive"))
      (node (ref "U$2") (pin "48") (pinfunction "IOB_80_48") (pintype "bidirectional"))
    )
    (net (code "34") (name "BIT7_0") (class "Default")
      (node (ref "RN7") (pin "1") (pinfunction "1_1") (pintype "passive"))
      (node (ref "U$2") (pin "10") (pinfunction "IOL_5B_10") (pintype "bidirectional"))
    )
    (net (code "35") (name "BIT7_1") (class "Default")
      (node (ref "RN11") (pin "1") (pinfunction "1_1") (pintype "passive"))
      (node (ref "U$2") (pin "118") (pinfunction "IOT_177_118") (pintype "bidirectional"))
    )
    (net (code "36") (name "BIT7_2") (class "Default")
      (node (ref "RN15") (pin "8") (pinfunction "1_8") (pintype "passive"))
      (node (ref "U$2") (pin "47") (pinfunction "IOB_79_47") (pintype "bidirectional"))
    )
    (net (code "37") (name "BIT8_0") (class "Default")
      (node (ref "RN6") (pin "8") (pinfunction "1_8") (pintype "passive"))
      (node (ref "U$2") (pin "25") (pinfunction "IOL_18A_25") (pintype "bidirectional"))
    )
    (net (code "38") (name "BIT8_1") (class "Default")
      (node (ref "RN10") (pin "8") (pinfunction "1_8") (pintype "passive"))
      (node (ref "U$2") (pin "136") (pinfunction "IOT_214_136") (pintype "bidirectional"))
    )
    (net (code "39") (name "BIT8_2") (class "Default")
      (node (ref "RN14") (pin "1") (pinfunction "1_1") (pintype "passive"))
      (node (ref "U$2") (pin "45") (pinfunction "IOB_73_45") (pintype "bidirectional"))
    )
    (net (code "40") (name "BIT9_0") (class "Default")
      (node (ref "RN6") (pin "7") (pinfunction "1_7") (pintype "passive"))
      (node (ref "U$2") (pin "26") (pinfunction "IOL_18B_26") (pintype "bidirectional"))
    )
    (net (code "41") (name "BIT9_1") (class "Default")
      (node (ref "RN10") (pin "7") (pinfunction "1_7") (pintype "passive"))
      (node (ref "U$2") (pin "137") (pinfunction "IOT_215_137") (pintype "bidirectional"))
    )
    (net (code "42") (name "BIT9_2") (class "Default")
      (node (ref "RN14") (pin "2") (pinfunction "1_2") (pintype "passive"))
      (node (ref "U$2") (pin "44") (pinfunction "IOB_72_44") (pintype "bidirectional"))
    )
    (net (code "43") (name "BIT10_0") (class "Default")
      (node (ref "RN6") (pin "6") (pinfunction "1_6") (pintype "passive"))
      (node (ref "U$2") (pin "28") (pinfunction "IOL_23A_28") (pintype "bidirectional"))
    )
    (net (code "44") (name "BIT10_1") (class "Default")
      (node (ref "RN10") (pin "6") (pinfunction "1_6") (pintype "passive"))
      (node (ref "U$2") (pin "138") (pinfunction "IOT_216_138") (pintype "bidirectional"))
    )
    (net (code "45") (name "BIT10_2") (class "Default")
      (node (ref "RN14") (pin "3") (pinfunction "1_3") (pintype "passive"))
      (node (ref "U$2") (pin "43") (pinfunction "IOB_71_43") (pintype "bidirectional"))
    )
    (net (code "46") (name "BIT11_0") (class "Default")
      (node (ref "RN6") (pin "5") (pinfunction "1_5") (pintype "passive"))
      (node (ref "U$2") (pin "29") (pinfunction "IOL_23B_29") (pintype "bidirectional"))
    )
    (net (code "47") (name "BIT11_1") (class "Default")
      (node (ref "RN10") (pin "5") (pinfunction "1_5") (pintype "passive"))
      (node (ref "U$2") (pin "139") (pinfunction "IOT_217_139") (pintype "bidirectional"))
    )
    (net (code "48") (name "BIT11_2") (class "Default")
      (node (ref "RN14") (pin "4") (pinfunction "1_4") (pintype "passive"))
      (node (ref "U$2") (pin "42") (pinfunction "IOB_64_42") (pintype "bidirectional"))
    )
    (net (code "49") (name "BIT12_0") (class "Default")
      (node (ref "RN6") (pin "4") (pinfunction "1_4") (pintype "passive"))
      (node (ref "U$2") (pin "31") (pinfunction "IOL_24A_31") (pintype "bidirectional"))
    )
    (net (code "50") (name "BIT12_1") (class "Default")
      (node (ref "RN10") (pin "4") (pinfunction "1_4") (pintype "passive"))
      (node (ref "U$2") (pin "141") (pinfunction "IOT_219_141") (pintype "bidirectional"))
    )
    (net (code "51") (name "BIT12_2") (class "Default")
      (node (ref "RN14") (pin "5") (pinfunction "1_5") (pintype "passive"))
      (node (ref "U$2") (pin "41") (pinfunction "IOB_63_41") (pintype "bidirectional"))
    )
    (net (code "52") (name "BIT13_0") (class "Default")
      (node (ref "RN6") (pin "3") (pinfunction "1_3") (pintype "passive"))
      (node (ref "U$2") (pin "32") (pinfunction "IOL_24B_32") (pintype "bidirectional"))
    )
    (net (code "53") (name "BIT13_1") (class "Default")
      (node (ref "RN10") (pin "3") (pinfunction "1_3") (pintype "passive"))
      (node (ref "U$2") (pin "142") (pinfunction "IOT_220_142") (pintype "bidirectional"))
    )
    (net (code "54") (name "BIT13_2") (class "Default")
      (node (ref "RN14") (pin "6") (pinfunction "1_6") (pintype "passive"))
      (node (ref "U$2") (pin "39") (pinfunction "IOB_61_39") (pintype "bidirectional"))
    )
    (net (code "55") (name "BIT14_0") (class "Default")
      (node (ref "RN6") (pin "2") (pinfunction "1_2") (pintype "passive"))
      (node (ref "U$2") (pin "33") (pinfunction "IOL_25A_33") (pintype "bidirectional"))
    )
    (net (code "56") (name "BIT14_1") (class "Default")
      (node (ref "RN10") (pin "2") (pinfunction "1_2") (pintype "passive"))
      (node (ref "U$2") (pin "143") (pinfunction "IOT_221_143") (pintype "bidirectional"))
    )
    (net (code "57") (name "BIT14_2") (class "Default")
      (node (ref "RN14") (pin "7") (pinfunction "1_7") (pintype "passive"))
      (node (ref "U$2") (pin "38") (pinfunction "IOB_57_38") (pintype "bidirectional"))
    )
    (net (code "58") (name "BIT15_0") (class "Default")
      (node (ref "RN6") (pin "1") (pinfunction "1_1") (pintype "passive"))
      (node (ref "U$2") (pin "34") (pinfunction "IOL_25B_34") (pintype "bidirectional"))
    )
    (net (code "59") (name "BIT15_1") (class "Default")
      (node (ref "RN10") (pin "1") (pinfunction "1_1") (pintype "passive"))
      (node (ref "U$2") (pin "144") (pinfunction "IOT_222_144") (pintype "bidirectional"))
    )
    (net (code "60") (name "BIT15_2") (class "Default")
      (node (ref "RN14") (pin "8") (pinfunction "1_8") (pintype "passive"))
      (node (ref "U$2") (pin "37") (pinfunction "IOB_56_37") (pintype "bidirectional"))
    )
    (net (code "61") (name "CDONE") (class "Default")
      (node (ref "R10") (pin "1") (pinfunction "1_1") (pintype "passive"))
      (node (ref "SAMD21") (pin "10") (pinfunction "PA05/EINT5/AIN5/SERCOM0.1_10") (pintype "bidirectional"))
      (node (ref "U$2") (pin "65") (pinfunction "CDONE_65") (pintype "bidirectional"))
    )
    (net (code "62") (name "CLK_IN") (class "Default")
      (node (ref "CLK") (pin "TP") (pinfunction "TP_TP") (pintype "input"))
      (node (ref "U$2") (pin "21") (pinfunction "IOL_14A_GBIN6_21") (pintype "bidirectional"))
      (node (ref "U$5") (pin "3") (pinfunction "VOUT_3") (pintype "bidirectional"))
    )
    (net (code "63") (name "CRESET") (class "Default")
      (node (ref "R11") (pin "1") (pinfunction "1_1") (pintype "passive"))
      (node (ref "SAMD21") (pin "9") (pinfunction "PA04/EINT4/VREFB/AIN4/SERCOM0.0_9") (pintype "bidirectional"))
      (node (ref "U$2") (pin "66") (pinfunction "CRESET_B_66") (pintype "bidirectional"))
    )
    (net (code "64") (name "CUTOFF") (class "Default")
      (node (ref "R65") (pin "1") (pinfunction "1_1") (pintype "passive"))
      (node (ref "U$1") (pin "2") (pinfunction "B_2") (pintype "passive"))
      (node (ref "U$3") (pin "2") (pinfunction "B_2") (pintype "passive"))
      (node (ref "U$4") (pin "2") (pinfunction "B_2") (pintype "passive"))
      (node (ref "U$7") (pin "2") (pinfunction "B_2") (pintype "passive"))
      (node (ref "U10") (pin "1") (pinfunction "B_1") (pintype "passive"))
      (node (ref "U16") (pin "1") (pinfunction "B_1") (pintype "passive"))
      (node (ref "U2") (pin "1") (pinfunction "B_1") (pintype "passive"))
      (node (ref "U4") (pin "1") (pinfunction "OUT_1") (pintype "output"))
      (node (ref "U6") (pin "1") (pinfunction "B_1") (pintype "passive"))
    )
    (net (code "65") (name "D+") (class "Default")
      (node (ref "SAMD21") (pin "34") (pinfunction "PA25/I13/SERCOM3+5.3/D+_34") (pintype "bidirectional"))
      (node (ref "X3") (pin "D+") (pinfunction "D+_D+") (pintype "bidirectional"))
    )
    (net (code "66") (name "D-") (class "Default")
      (node (ref "SAMD21") (pin "33") (pinfunction "PA24/I12/SERCOM3+5.2/D-_33") (pintype "bidirectional"))
      (node (ref "X3") (pin "D-") (pinfunction "D-_D-") (pintype "bidirectional"))
    )
    (net (code "67") (name "D0") (class "Default")
      (node (ref "JP1") (pin "19") (pinfunction "19_19") (pintype "passive"))
      (node (ref "SAMD21") (pin "16") (pinfunction "PA11/I11/AIN19/SERCOM0+2.3/I2SF0_16") (pintype "bidirectional"))
    )
    (net (code "68") (name "D1") (class "Default")
      (node (ref "JP1") (pin "20") (pinfunction "20_20") (pintype "passive"))
      (node (ref "SAMD21") (pin "15") (pinfunction "PA10/I10/AIN18/SERCOM0+2.2/I2SCK_15") (pintype "bidirectional"))
    )
    (net (code "69") (name "D2") (class "Default")
      (node (ref "SAMD21") (pin "23") (pinfunction "PA14/I14/SERCOM2+4.2_23") (pintype "bidirectional"))
    )
    (net (code "70") (name "D3") (class "Default")
      (node (ref "JP1") (pin "17") (pinfunction "17_17") (pintype "passive"))
      (node (ref "SAMD21") (pin "14") (pinfunction "PA09/I2C/I9/AIN17/SERCOM0+2.1/I2SMC_14") (pintype "bidirectional"))
    )
    (net (code "71") (name "D4") (class "Default")
      (node (ref "JP1") (pin "18") (pinfunction "18_18") (pintype "passive"))
      (node (ref "SAMD21") (pin "13") (pinfunction "PA08/I2C/AIN16/SERCOM0+2.0/I2SD1_13") (pintype "bidirectional"))
    )
    (net (code "72") (name "D6") (class "Default")
      (node (ref "JP1") (pin "12") (pinfunction "12_12") (pintype "passive"))
      (node (ref "SAMD21") (pin "29") (pinfunction "PA20/I4/SERCOM3+5.2/I2SSC_29") (pintype "bidirectional"))
    )
    (net (code "73") (name "D7") (class "Default")
      (node (ref "JP1") (pin "11") (pinfunction "11_11") (pintype "passive"))
      (node (ref "SAMD21") (pin "30") (pinfunction "PA21/I5/SERCOM3+5.3/I2SFS0_30") (pintype "bidirectional"))
    )
    (net (code "74") (name "D8") (class "Default")
      (node (ref "JP1") (pin "22") (pinfunction "22_22") (pintype "passive"))
      (node (ref "SAMD21") (pin "11") (pinfunction "PA06/EINT6/AIN6/SERCOM0.2_11") (pintype "bidirectional"))
    )
    (net (code "75") (name "D9") (class "Default")
      (node (ref "SAMD21") (pin "12") (pinfunction "PA07/I7/AIN7/SERCOM0.3/I2SD0_12") (pintype "bidirectional"))
    )
    (net (code "76") (name "D13") (class "Default")
      (node (ref "R164") (pin "1") (pinfunction "1_1") (pintype "passive"))
      (node (ref "SAMD21") (pin "26") (pinfunction "PA17/I2C/I1/SERCOM1+3.1_26") (pintype "bidirectional"))
    )
    (net (code "77") (name "FPGA_105") (class "Default")
      (node (ref "JP1") (pin "10") (pinfunction "10_10") (pintype "passive"))
      (node (ref "U$2") (pin "105") (pinfunction "IOR_165_105") (pintype "bidirectional"))
    )
    (net (code "78") (name "FPGA_107") (class "Default")
      (node (ref "JP1") (pin "6") (pinfunction "6_6") (pintype "passive"))
      (node (ref "U$2") (pin "107") (pinfunction "IOR_167_107") (pintype "bidirectional"))
    )
    (net (code "79") (name "FPGA_CS") (class "Default")
      (node (ref "IC1") (pin "1") (pinfunction "~{OE}_1") (pintype "input"))
      (node (ref "RN4") (pin "8") (pinfunction "2_8") (pintype "passive"))
      (node (ref "SAMD21") (pin "27") (pinfunction "PA18/I2/SERCOM1+3.2_27") (pintype "bidirectional"))
    )
    (net (code "80") (name "FPGA_MISO") (class "Default")
      (node (ref "IC1") (pin "2") (pinfunction "A_2") (pintype "input"))
      (node (ref "RN4") (pin "7") (pinfunction "2_7") (pintype "passive"))
    )
    (net (code "81") (name "GND") (class "Default")
      (node (ref "C13") (pin "1") (pinfunction "1_1") (pintype "passive"))
      (node (ref "C14") (pin "1") (pinfunction "1_1") (pintype "passive"))
      (node (ref "C15") (pin "1") (pinfunction "1_1") (pintype "passive"))
      (node (ref "C16") (pin "1") (pinfunction "1_1") (pintype "passive"))
      (node (ref "C17") (pin "1") (pinfunction "1_1") (pintype "passive"))
      (node (ref "C18") (pin "1") (pinfunction "1_1") (pintype "passive"))
      (node (ref "C19") (pin "1") (pinfunction "1_1") (pintype "passive"))
      (node (ref "C20") (pin "1") (pinfunction "1_1") (pintype "passive"))
      (node (ref "C25") (pin "1") (pinfunction "1_1") (pintype "passive"))
      (node (ref "C27") (pin "1") (pinfunction "1_1") (pintype "passive"))
      (node (ref "C28") (pin "1") (pinfunction "1_1") (pintype "passive"))
      (node (ref "C29") (pin "2") (pinfunction "2_2") (pintype "passive"))
      (node (ref "C30") (pin "2") (pinfunction "2_2") (pintype "passive"))
      (node (ref "C31") (pin "2") (pinfunction "2_2") (pintype "passive"))
      (node (ref "C32") (pin "2") (pinfunction "2_2") (pintype "passive"))
      (node (ref "C33") (pin "1") (pinfunction "1_1") (pintype "passive"))
      (node (ref "C34") (pin "1") (pinfunction "1_1") (pintype "passive"))
      (node (ref "C41") (pin "1") (pinfunction "1_1") (pintype "passive"))
      (node (ref "C42") (pin "1") (pinfunction "1_1") (pintype "passive"))
      (node (ref "C48") (pin "1") (pinfunction "1_1") (pintype "passive"))
      (node (ref "C49") (pin "2") (pinfunction "2_2") (pintype "passive"))
      (node (ref "C5") (pin "2") (pinfunction "2_2") (pintype "passive"))
      (node (ref "C50") (pin "2") (pinfunction "2_2") (pintype "passive"))
      (node (ref "C51") (pin "2") (pinfunction "2_2") (pintype "passive"))
      (node (ref "C52") (pin "2") (pinfunction "2_2") (pintype "passive"))
      (node (ref "C54") (pin "1") (pinfunction "1_1") (pintype "passive"))
      (node (ref "C68") (pin "1") (pinfunction "1_1") (pintype "passive"))
      (node (ref "C69") (pin "1") (pinfunction "1_1") (pintype "passive"))
      (node (ref "C7") (pin "2") (pinfunction "2_2") (pintype "passive"))
      (node (ref "C70") (pin "1") (pinfunction "1_1") (pintype "passive"))
      (node (ref "C71") (pin "1") (pinfunction "1_1") (pintype "passive"))
      (node (ref "C8") (pin "2") (pinfunction "2_2") (pintype "passive"))
      (node (ref "C80") (pin "1") (pinfunction "1_1") (pintype "passive"))
      (node (ref "C81") (pin "2") (pinfunction "2_2") (pintype "passive"))
      (node (ref "CN2") (pin "2") (pinfunction "1_2") (pintype "passive"))
      (node (ref "FB3") (pin "1") (pinfunction "P$1_1") (pintype "passive"))
      (node (ref "IC1") (pin "3") (pinfunction "GND_3") (pintype "power_in"))
      (node (ref "IC2") (pin "2") (pinfunction "VSS_2") (pintype "power_in"))
      (node (ref "IC3") (pin "3") (pinfunction "GND_3") (pintype "power_in"))
      (node (ref "IC4") (pin "3") (pinfunction "GND_3") (pintype "power_in"))
      (node (ref "J100") (pin "3") (pinfunction "3_3") (pintype "passive"))
      (node (ref "J100") (pin "5") (pinfunction "5_5") (pintype "passive"))
      (node (ref "J100") (pin "9") (pinfunction "9_9") (pintype "passive"))
      (node (ref "JP1") (pin "2") (pinfunction "2_2") (pintype "passive"))
      (node (ref "L") (pin "C") (pinfunction "C_C") (pintype "passive"))
      (node (ref "OK1") (pin "5") (pinfunction "GND_5") (pintype "passive"))
      (node (ref "R31") (pin "1") (pinfunction "1_1") (pintype "passive"))
      (node (ref "R32") (pin "1") (pinfunction "1_1") (pintype "passive"))
      (node (ref "R33") (pin "1") (pinfunction "1_1") (pintype "passive"))
      (node (ref "R68") (pin "2") (pinfunction "2_2") (pintype "passive"))
      (node (ref "RAM1") (pin "4") (pinfunction "GND_4") (pintype "bidirectional"))
      (node (ref "S1") (pin "1") (pinfunction "O_1") (pintype "passive"))
      (node (ref "SAMD21") (pin "18") (pinfunction "GND_18") (pintype "power_in"))
      (node (ref "SAMD21") (pin "35") (pinfunction "GND_35") (pintype "power_in"))
      (node (ref "SAMD21") (pin "42") (pinfunction "GND_42") (pintype "power_in"))
      (node (ref "SAMD21") (pin "5") (pinfunction "GNDA_5") (pintype "power_in"))
      (node (ref "SAMD21") (pin "THERMAL") (pinfunction "GND_THERMAL") (pintype "power_in"))
      (node (ref "SW1") (pin "2") (pinfunction "S_2") (pintype "passive"))
      (node (ref "SW1") (pin "4") (pinfunction "S1_4") (pintype "passive"))
      (node (ref "U$2") (pin "103") (pinfunction "GND_2_103") (pintype "bidirectional"))
      (node (ref "U$2") (pin "13") (pinfunction "GND_2_13") (pintype "bidirectional"))
      (node (ref "U$2") (pin "132") (pinfunction "GND_132") (pintype "bidirectional"))
      (node (ref "U$2") (pin "14") (pinfunction "GND_3_14") (pintype "bidirectional"))
      (node (ref "U$2") (pin "140") (pinfunction "GND_2_140") (pintype "bidirectional"))
      (node (ref "U$2") (pin "5") (pinfunction "GND_5") (pintype "bidirectional"))
      (node (ref "U$2") (pin "59") (pinfunction "GND_59") (pintype "bidirectional"))
      (node (ref "U$2") (pin "69") (pinfunction "GND_69") (pintype "bidirectional"))
      (node (ref "U$2") (pin "86") (pinfunction "GND_86") (pintype "bidirectional"))
      (node (ref "U$5") (pin "2") (pinfunction "GND_2") (pintype "bidirectional"))
      (node (ref "U12") (pin "4") (pinfunction "GND_4") (pintype "passive"))
      (node (ref "U5") (pin "2") (pinfunction "GND_2") (pintype "power_in"))
      (node (ref "X3") (pin "BASE@1") (pinfunction "GND_BASE@1") (pintype "power_in"))
      (node (ref "X3") (pin "BASE@2") (pinfunction "GND_BASE@2") (pintype "power_in"))
      (node (ref "X3") (pin "GND") (pinfunction "GND_GND") (pintype "power_in"))
      (node (ref "X3") (pin "SPRT@1") (pinfunction "GND_SPRT@1") (pintype "power_in"))
      (node (ref "X3") (pin "SPRT@2") (pinfunction "GND_SPRT@2") (pintype "power_in"))
      (node (ref "X3") (pin "SPRT@3") (pinfunction "GND_SPRT@3") (pintype "power_in"))
      (node (ref "X3") (pin "SPRT@4") (pinfunction "GND_SPRT@4") (pintype "power_in"))
      (node (ref "X4") (pin "6") (pinfunction "GND_6") (pintype "power_in"))
      (node (ref "X4") (pin "MT1") (pinfunction "GND_MT1") (pintype "power_in"))
      (node (ref "X4") (pin "MT2") (pinfunction "GND_MT2") (pintype "power_in"))
    )
    (net (code "82") (name "GND2") (class "Default")
      (node (ref "C6") (pin "-") (pinfunction "-_-") (pintype "passive"))
      (node (ref "C61") (pin "2") (pinfunction "2_2") (pintype "passive"))
      (node (ref "C63") (pin "2") (pinfunction "2_2") (pintype "passive"))
      (node (ref "C65") (pin "2") (pinfunction "2_2") (pintype "passive"))
      (node (ref "C67") (pin "2") (pinfunction "2_2") (pintype "passive"))
      (node (ref "C72") (pin "2") (pinfunction "2_2") (pintype "passive"))
      (node (ref "C75") (pin "2") (pinfunction "2_2") (pintype "passive"))
      (node (ref "C76") (pin "2") (pinfunction "2_2") (pintype "passive"))
      (node (ref "C79") (pin "2") (pinfunction "2_2") (pintype "passive"))
      (node (ref "C82") (pin "2") (pinfunction "2_2") (pintype "passive"))
      (node (ref "FB3") (pin "2") (pinfunction "P$2_2") (pintype "passive"))
      (node (ref "JP1") (pin "37") (pinfunction "37_37") (pintype "passive"))
      (node (ref "R15") (pin "1") (pinfunction "1_1") (pintype "passive"))
      (node (ref "R190") (pin "2") (pinfunction "2_2") (pintype "passive"))
      (node (ref "R21") (pin "1") (pinfunction "1_1") (pintype "passive"))
      (node (ref "R27") (pin "1") (pinfunction "1_1") (pintype "passive"))
      (node (ref "R37") (pin "1") (pinfunction "1_1") (pintype "passive"))
      (node (ref "R49") (pin "1") (pinfunction "1_1") (pintype "passive"))
      (node (ref "R53") (pin "1") (pinfunction "1_1") (pintype "passive"))
      (node (ref "R6") (pin "1") (pinfunction "1_1") (pintype "passive"))
      (node (ref "R62") (pin "1") (pinfunction "1_1") (pintype "passive"))
      (node (ref "U$19") (pin "1") (pinfunction "SHUTDOWN_1") (pintype "bidirectional"))
      (node (ref "U$19") (pin "7") (pinfunction "GND_7") (pintype "bidirectional"))
      (node (ref "U1") (pin "11") (pinfunction "V-_11") (pintype "bidirectional"))
      (node (ref "U13") (pin "2") (pinfunction "V-_2") (pintype "bidirectional"))
      (node (ref "U14") (pin "11") (pinfunction "V-_11") (pintype "bidirectional"))
      (node (ref "U15") (pin "11") (pinfunction "V-_11") (pintype "bidirectional"))
      (node (ref "U18") (pin "11") (pinfunction "V-_11") (pintype "bidirectional"))
      (node (ref "U4") (pin "11") (pinfunction "V-_11") (pintype "bidirectional"))
      (node (ref "U8") (pin "11") (pinfunction "V-_11") (pintype "bidirectional"))
      (node (ref "U9") (pin "11") (pinfunction "V-_11") (pintype "bidirectional"))
    )
    (net (code "83") (name "MISO") (class "Default")
      (node (ref "IC1") (pin "4") (pinfunction "Y_4") (pintype "output"))
      (node (ref "IC3") (pin "4") (pinfunction "Y_4") (pintype "output"))
      (node (ref "IC4") (pin "4") (pinfunction "Y_4") (pintype "output"))
      (node (ref "JP1") (pin "7") (pinfunction "7_7") (pintype "passive"))
      (node (ref "SAMD21") (pin "21") (pinfunction "PA12/I12/I2C/SERCOM2+4.0_21") (pintype "bidirectional"))
    )
    (net (code "84") (name "MOSI") (class "Default")
      (node (ref "JP1") (pin "8") (pinfunction "8_8") (pintype "passive"))
      (node (ref "RN2") (pin "3") (pinfunction "1_3") (pintype "passive"))
      (node (ref "RN3") (pin "1") (pinfunction "1_1") (pintype "passive"))
      (node (ref "RN4") (pin "5") (pinfunction "2_5") (pintype "passive"))
      (node (ref "SAMD21") (pin "19") (pinfunction "PB10/I10/SERCOM4.2/I2SMC_19") (pintype "bidirectional"))
    )
    (net (code "85") (name "NOISE") (class "Default")
      (node (ref "R185") (pin "1") (pinfunction "1_1") (pintype "passive"))
      (node (ref "U$16") (pin "2") (pinfunction "B_2") (pintype "passive"))
      (node (ref "U30") (pin "1") (pinfunction "B_1") (pintype "passive"))
      (node (ref "U4") (pin "14") (pinfunction "OUT_14") (pintype "output"))
    )
    (net (code "86") (name "NOISE_IN") (class "Default")
      (node (ref "R55") (pin "2") (pinfunction "2_2") (pintype "passive"))
      (node (ref "U$2") (pin "135") (pinfunction "IOT_213_135") (pintype "bidirectional"))
    )
    (net (code "87") (name "NOISE_SCALED") (class "Default")
      (node (ref "C59") (pin "2") (pinfunction "2_2") (pintype "passive"))
      (node (ref "R191") (pin "2") (pinfunction "2_2") (pintype "passive"))
      (node (ref "R56") (pin "1") (pinfunction "1_1") (pintype "passive"))
      (node (ref "U8") (pin "14") (pinfunction "OUT_14") (pintype "output"))
    )
    (net (code "88") (name "Net-(C24-Pad1)") (class "Default")
      (node (ref "C24") (pin "1") (pinfunction "1_1") (pintype "passive"))
      (node (ref "R23") (pin "1") (pinfunction "1_1") (pintype "passive"))
    )
    (net (code "89") (name "Net-(C37-Pad1)") (class "Default")
      (node (ref "C37") (pin "1") (pinfunction "1_1") (pintype "passive"))
      (node (ref "R29") (pin "1") (pinfunction "1_1") (pintype "passive"))
    )
    (net (code "90") (name "Net-(C47-Pad2)") (class "Default")
      (node (ref "C47") (pin "2") (pinfunction "2_2") (pintype "passive"))
      (node (ref "R39") (pin "2") (pinfunction "2_2") (pintype "passive"))
    )
    (net (code "91") (name "Net-(C53-Pad1)") (class "Default")
      (node (ref "C53") (pin "1") (pinfunction "1_1") (pintype "passive"))
      (node (ref "R17") (pin "1") (pinfunction "1_1") (pintype "passive"))
    )
    (net (code "92") (name "Net-(C55-Pad1)") (class "Default")
      (node (ref "C55") (pin "1") (pinfunction "1_1") (pintype "passive"))
      (node (ref "R47") (pin "2") (pinfunction "2_2") (pintype "passive"))
    )
    (net (code "93") (name "Net-(CN1-P$2)") (class "Default")
      (node (ref "CN1") (pin "3") (pinfunction "P$2_3") (pintype "bidirectional"))
      (node (ref "D10") (pin "A") (pinfunction "A_A") (pintype "passive"))
      (node (ref "OK1") (pin "3") (pinfunction "C_3") (pintype "passive"))
    )
    (net (code "94") (name "Net-(CN1-P$5)") (class "Default")
      (node (ref "CN1") (pin "2") (pinfunction "P$5_2") (pintype "bidirectional"))
      (node (ref "R165") (pin "2") (pinfunction "2_2") (pintype "passive"))
    )
    (net (code "95") (name "Net-(CN3-P$1)") (class "Default")
      (node (ref "CN3") (pin "1") (pinfunction "P$1_1") (pintype "bidirectional"))
      (node (ref "R75") (pin "1") (pinfunction "1_1") (pintype "passive"))
      (node (ref "U$19") (pin "5") (pinfunction "VO1_5") (pintype "bidirectional"))
    )
    (net (code "96") (name "Net-(CN3-P$2)") (class "Default")
      (node (ref "CN3") (pin "2") (pinfunction "P$5_2") (pintype "bidirectional"))
      (node (ref "CN3") (pin "3") (pinfunction "P$2_3") (pintype "bidirectional"))
      (node (ref "U$19") (pin "8") (pinfunction "VO2_8") (pintype "bidirectional"))
    )
    (net (code "97") (name "Net-(D2-C)") (class "Default")
      (node (ref "D2") (pin "K") (pinfunction "C_K") (pintype "passive"))
      (node (ref "U$2") (pin "108") (pinfunction "VPP_2V5_108") (pintype "bidirectional"))
    )
    (net (code "98") (name "Net-(D10-C)") (class "Default")
      (node (ref "D10") (pin "K") (pinfunction "C_K") (pintype "passive"))
      (node (ref "OK1") (pin "2") (pinfunction "A_2") (pintype "passive"))
      (node (ref "R165") (pin "1") (pinfunction "1_1") (pintype "passive"))
    )
    (net (code "99") (name "Net-(FB1-P$1)") (class "Default")
      (node (ref "C88") (pin "2") (pinfunction "2_2") (pintype "passive"))
      (node (ref "FB1") (pin "1") (pinfunction "P$1_1") (pintype "passive"))
      (node (ref "R183") (pin "2") (pinfunction "2_2") (pintype "passive"))
    )
    (net (code "100") (name "Net-(FB2-P$2)") (class "Default")
      (node (ref "C52") (pin "1") (pinfunction "1_1") (pintype "passive"))
      (node (ref "C7") (pin "1") (pinfunction "1_1") (pintype "passive"))
      (node (ref "FB2") (pin "2") (pinfunction "P$2_2") (pintype "passive"))
      (node (ref "R168") (pin "1") (pinfunction "1_1") (pintype "passive"))
      (node (ref "U5") (pin "1") (pinfunction "IN_1") (pintype "power_in"))
    )
    (net (code "101") (name "Net-(IC2-PROG)") (class "Default")
      (node (ref "IC2") (pin "5") (pinfunction "PROG_5") (pintype "input"))
      (node (ref "R68") (pin "1") (pinfunction "1_1") (pintype "passive"))
    )
    (net (code "102") (name "Net-(IC2-STAT)") (class "Default")
      (node (ref "IC2") (pin "1") (pinfunction "STAT_1") (pintype "output"))
      (node (ref "R69") (pin "2") (pinfunction "2_2") (pintype "passive"))
    )
    (net (code "103") (name "Net-(IC4-A)") (class "Default")
      (node (ref "IC4") (pin "2") (pinfunction "A_2") (pintype "input"))
      (node (ref "RAM1") (pin "2") (pinfunction "SDO_2") (pintype "bidirectional"))
      (node (ref "RN3") (pin "2") (pinfunction "1_2") (pintype "passive"))
    )
    (net (code "104") (name "Net-(J100-Pad10)") (class "Default")
      (node (ref "J100") (pin "10") (pinfunction "10_10") (pintype "passive"))
      (node (ref "R179") (pin "1") (pinfunction "1_1") (pintype "passive"))
    )
    (net (code "105") (name "Net-(L-PadA)") (class "Default")
      (node (ref "L") (pin "A") (pinfunction "A_A") (pintype "passive"))
      (node (ref "R164") (pin "2") (pinfunction "2_2") (pintype "passive"))
    )
    (net (code "106") (name "Net-(LED1-PadC)") (class "Default")
      (node (ref "LED1") (pin "C") (pinfunction "C_C") (pintype "passive"))
      (node (ref "R69") (pin "1") (pinfunction "1_1") (pintype "passive"))
    )
    (net (code "107") (name "Net-(RAM1-CS)") (class "Default")
      (node (ref "R60") (pin "1") (pinfunction "1_1") (pintype "passive"))
      (node (ref "RAM1") (pin "1") (pinfunction "CS_1") (pintype "bidirectional"))
      (node (ref "RN3") (pin "5") (pinfunction "2_5") (pintype "passive"))
      (node (ref "U$2") (pin "71") (pinfunction "IOB_108_SS_71") (pintype "bidirectional"))
    )
    (net (code "108") (name "Net-(RAM1-HOLD)") (class "Default")
      (node (ref "R57") (pin "1") (pinfunction "1_1") (pintype "passive"))
      (node (ref "RAM1") (pin "7") (pinfunction "HOLD_7") (pintype "bidirectional"))
    )
    (net (code "109") (name "Net-(RAM1-SCK)") (class "Default")
      (node (ref "R59") (pin "1") (pinfunction "1_1") (pintype "passive"))
      (node (ref "RAM1") (pin "6") (pinfunction "SCK_6") (pintype "bidirectional"))
      (node (ref "RN3") (pin "6") (pinfunction "2_6") (pintype "passive"))
      (node (ref "U$2") (pin "70") (pinfunction "IOB_107_SCK_70") (pintype "bidirectional"))
    )
    (net (code "110") (name "Net-(RAM1-SDI)") (class "Default")
      (node (ref "RAM1") (pin "5") (pinfunction "SDI_5") (pintype "bidirectional"))
      (node (ref "RN3") (pin "8") (pinfunction "2_8") (pintype "passive"))
      (node (ref "U$2") (pin "67") (pinfunction "IOB_105_SDO_67") (pintype "bidirectional"))
    )
    (net (code "111") (name "Net-(RAM1-WP)") (class "Default")
      (node (ref "R58") (pin "1") (pinfunction "1_1") (pintype "passive"))
      (node (ref "RAM1") (pin "3") (pinfunction "WP_3") (pintype "bidirectional"))
    )
    (net (code "112") (name "Net-(RN2A-2)") (class "Default")
      (node (ref "RN2") (pin "8") (pinfunction "2_8") (pintype "passive"))
      (node (ref "X4") (pin "7") (pinfunction "DATA_OUT_7") (pintype "output"))
    )
    (net (code "113") (name "Net-(RN2B-2)") (class "Default")
      (node (ref "RN2") (pin "7") (pinfunction "2_7") (pintype "passive"))
      (node (ref "X4") (pin "5") (pinfunction "SCLK_5") (pintype "input"))
    )
    (net (code "114") (name "Net-(RN2C-2)") (class "Default")
      (node (ref "RN2") (pin "6") (pinfunction "2_6") (pintype "passive"))
      (node (ref "X4") (pin "3") (pinfunction "DATA_IN_3") (pintype "input"))
    )
    (net (code "115") (name "Net-(RN2D-2)") (class "Default")
      (node (ref "RN2") (pin "5") (pinfunction "2_5") (pintype "passive"))
      (node (ref "X4") (pin "2") (pinfunction "CS_2") (pintype "input"))
    )
    (net (code "116") (name "Net-(RN3B-2)") (class "Default")
      (node (ref "RN3") (pin "7") (pinfunction "2_7") (pintype "passive"))
      (node (ref "U$2") (pin "68") (pinfunction "IOB_106_SDI_68") (pintype "bidirectional"))
    )
    (net (code "117") (name "Net-(RN4B-1)") (class "Default")
      (node (ref "RN4") (pin "2") (pinfunction "1_2") (pintype "passive"))
      (node (ref "U$2") (pin "104") (pinfunction "IOR_164_104") (pintype "bidirectional"))
    )
    (net (code "118") (name "Net-(RN4C-1)") (class "Default")
      (node (ref "RN4") (pin "3") (pinfunction "1_3") (pintype "passive"))
      (node (ref "U$2") (pin "102") (pinfunction "IOR_161_102") (pintype "bidirectional"))
    )
    (net (code "119") (name "Net-(RN4D-1)") (class "Default")
      (node (ref "RN4") (pin "4") (pinfunction "1_4") (pintype "passive"))
      (node (ref "U$2") (pin "101") (pinfunction "IOR_160_101") (pintype "bidirectional"))
    )
    (net (code "120") (name "Net-(RN5B-1)") (class "Default")
      (node (ref "RN5") (pin "2") (pinfunction "1_2") (pintype "passive"))
      (node (ref "U$2") (pin "17") (pinfunction "IOL_12A_17") (pintype "bidirectional"))
    )
    (net (code "121") (name "Net-(RN5C-1)") (class "Default")
      (node (ref "RN5") (pin "3") (pinfunction "1_3") (pintype "passive"))
      (node (ref "U$2") (pin "19") (pinfunction "IOL_13A_19") (pintype "bidirectional"))
    )
    (net (code "122") (name "Net-(RN5D-1)") (class "Default")
      (node (ref "RN5") (pin "4") (pinfunction "1_4") (pintype "passive"))
      (node (ref "U$2") (pin "23") (pinfunction "IOL_17A_23") (pintype "bidirectional"))
    )
    (net (code "123") (name "Net-(RN6B-2)") (class "Default")
      (node (ref "RN6") (pin "15") (pinfunction "2_15") (pintype "passive"))
      (node (ref "RN9") (pin "10") (pinfunction "2_10") (pintype "passive"))
      (node (ref "RN9") (pin "8") (pinfunction "1_8") (pintype "passive"))
    )
    (net (code "124") (name "Net-(RN6C-2)") (class "Default")
      (node (ref "RN6") (pin "14") (pinfunction "2_14") (pintype "passive"))
      (node (ref "RN9") (pin "11") (pinfunction "2_11") (pintype "passive"))
      (node (ref "RN9") (pin "7") (pinfunction "1_7") (pintype "passive"))
    )
    (net (code "125") (name "Net-(RN6D-2)") (class "Default")
      (node (ref "RN6") (pin "13") (pinfunction "2_13") (pintype "passive"))
      (node (ref "RN9") (pin "12") (pinfunction "2_12") (pintype "passive"))
      (node (ref "RN9") (pin "6") (pinfunction "1_6") (pintype "passive"))
    )
    (net (code "126") (name "Net-(RN6E-2)") (class "Default")
      (node (ref "RN6") (pin "12") (pinfunction "2_12") (pintype "passive"))
      (node (ref "RN9") (pin "13") (pinfunction "2_13") (pintype "passive"))
      (node (ref "RN9") (pin "5") (pinfunction "1_5") (pintype "passive"))
    )
    (net (code "127") (name "Net-(RN6F-2)") (class "Default")
      (node (ref "RN6") (pin "11") (pinfunction "2_11") (pintype "passive"))
      (node (ref "RN9") (pin "14") (pinfunction "2_14") (pintype "passive"))
      (node (ref "RN9") (pin "4") (pinfunction "1_4") (pintype "passive"))
    )
    (net (code "128") (name "Net-(RN6G-2)") (class "Default")
      (node (ref "RN6") (pin "10") (pinfunction "2_10") (pintype "passive"))
      (node (ref "RN9") (pin "15") (pinfunction "2_15") (pintype "passive"))
      (node (ref "RN9") (pin "3") (pinfunction "1_3") (pintype "passive"))
    )
    (net (code "129") (name "Net-(RN6H-2)") (class "Default")
      (node (ref "RN6") (pin "9") (pinfunction "2_9") (pintype "passive"))
      (node (ref "RN9") (pin "16") (pinfunction "2_16") (pintype "passive"))
      (node (ref "RN9") (pin "2") (pinfunction "1_2") (pintype "passive"))
    )
    (net (code "130") (name "Net-(RN7A-2)") (class "Default")
      (node (ref "RN7") (pin "16") (pinfunction "2_16") (pintype "passive"))
      (node (ref "RN8") (pin "9") (pinfunction "2_9") (pintype "passive"))
      (node (ref "RN9") (pin "1") (pinfunction "1_1") (pintype "passive"))
    )
    (net (code "131") (name "Net-(RN7B-2)") (class "Default")
      (node (ref "RN7") (pin "15") (pinfunction "2_15") (pintype "passive"))
      (node (ref "RN8") (pin "10") (pinfunction "2_10") (pintype "passive"))
      (node (ref "RN8") (pin "8") (pinfunction "1_8") (pintype "passive"))
    )
    (net (code "132") (name "Net-(RN7C-2)") (class "Default")
      (node (ref "RN7") (pin "14") (pinfunction "2_14") (pintype "passive"))
      (node (ref "RN8") (pin "11") (pinfunction "2_11") (pintype "passive"))
      (node (ref "RN8") (pin "7") (pinfunction "1_7") (pintype "passive"))
    )
    (net (code "133") (name "Net-(RN7D-2)") (class "Default")
      (node (ref "RN7") (pin "13") (pinfunction "2_13") (pintype "passive"))
      (node (ref "RN8") (pin "12") (pinfunction "2_12") (pintype "passive"))
      (node (ref "RN8") (pin "6") (pinfunction "1_6") (pintype "passive"))
    )
    (net (code "134") (name "Net-(RN7E-2)") (class "Default")
      (node (ref "RN7") (pin "12") (pinfunction "2_12") (pintype "passive"))
      (node (ref "RN8") (pin "13") (pinfunction "2_13") (pintype "passive"))
      (node (ref "RN8") (pin "5") (pinfunction "1_5") (pintype "passive"))
    )
    (net (code "135") (name "Net-(RN7F-2)") (class "Default")
      (node (ref "RN7") (pin "11") (pinfunction "2_11") (pintype "passive"))
      (node (ref "RN8") (pin "14") (pinfunction "2_14") (pintype "passive"))
      (node (ref "RN8") (pin "4") (pinfunction "1_4") (pintype "passive"))
    )
    (net (code "136") (name "Net-(RN7G-2)") (class "Default")
      (node (ref "RN7") (pin "10") (pinfunction "2_10") (pintype "passive"))
      (node (ref "RN8") (pin "15") (pinfunction "2_15") (pintype "passive"))
      (node (ref "RN8") (pin "3") (pinfunction "1_3") (pintype "passive"))
    )
    (net (code "137") (name "Net-(RN7H-2)") (class "Default")
      (node (ref "R31") (pin "2") (pinfunction "2_2") (pintype "passive"))
      (node (ref "RN7") (pin "9") (pinfunction "2_9") (pintype "passive"))
      (node (ref "RN8") (pin "2") (pinfunction "1_2") (pintype "passive"))
    )
    (net (code "138") (name "Net-(RN10B-2)") (class "Default")
      (node (ref "RN10") (pin "15") (pinfunction "2_15") (pintype "passive"))
      (node (ref "RN13") (pin "10") (pinfunction "2_10") (pintype "passive"))
      (node (ref "RN13") (pin "8") (pinfunction "1_8") (pintype "passive"))
    )
    (net (code "139") (name "Net-(RN10C-2)") (class "Default")
      (node (ref "RN10") (pin "14") (pinfunction "2_14") (pintype "passive"))
      (node (ref "RN13") (pin "11") (pinfunction "2_11") (pintype "passive"))
      (node (ref "RN13") (pin "7") (pinfunction "1_7") (pintype "passive"))
    )
    (net (code "140") (name "Net-(RN10D-2)") (class "Default")
      (node (ref "RN10") (pin "13") (pinfunction "2_13") (pintype "passive"))
      (node (ref "RN13") (pin "12") (pinfunction "2_12") (pintype "passive"))
      (node (ref "RN13") (pin "6") (pinfunction "1_6") (pintype "passive"))
    )
    (net (code "141") (name "Net-(RN10E-2)") (class "Default")
      (node (ref "RN10") (pin "12") (pinfunction "2_12") (pintype "passive"))
      (node (ref "RN13") (pin "13") (pinfunction "2_13") (pintype "passive"))
      (node (ref "RN13") (pin "5") (pinfunction "1_5") (pintype "passive"))
    )
    (net (code "142") (name "Net-(RN10F-2)") (class "Default")
      (node (ref "RN10") (pin "11") (pinfunction "2_11") (pintype "passive"))
      (node (ref "RN13") (pin "14") (pinfunction "2_14") (pintype "passive"))
      (node (ref "RN13") (pin "4") (pinfunction "1_4") (pintype "passive"))
    )
    (net (code "143") (name "Net-(RN10G-2)") (class "Default")
      (node (ref "RN10") (pin "10") (pinfunction "2_10") (pintype "passive"))
      (node (ref "RN13") (pin "15") (pinfunction "2_15") (pintype "passive"))
      (node (ref "RN13") (pin "3") (pinfunction "1_3") (pintype "passive"))
    )
    (net (code "144") (name "Net-(RN10H-2)") (class "Default")
      (node (ref "RN10") (pin "9") (pinfunction "2_9") (pintype "passive"))
      (node (ref "RN13") (pin "16") (pinfunction "2_16") (pintype "passive"))
      (node (ref "RN13") (pin "2") (pinfunction "1_2") (pintype "passive"))
    )
    (net (code "145") (name "Net-(RN11A-2)") (class "Default")
      (node (ref "RN11") (pin "16") (pinfunction "2_16") (pintype "passive"))
      (node (ref "RN12") (pin "9") (pinfunction "2_9") (pintype "passive"))
      (node (ref "RN13") (pin "1") (pinfunction "1_1") (pintype "passive"))
    )
    (net (code "146") (name "Net-(RN11B-2)") (class "Default")
      (node (ref "RN11") (pin "15") (pinfunction "2_15") (pintype "passive"))
      (node (ref "RN12") (pin "10") (pinfunction "2_10") (pintype "passive"))
      (node (ref "RN12") (pin "8") (pinfunction "1_8") (pintype "passive"))
    )
    (net (code "147") (name "Net-(RN11C-2)") (class "Default")
      (node (ref "RN11") (pin "14") (pinfunction "2_14") (pintype "passive"))
      (node (ref "RN12") (pin "11") (pinfunction "2_11") (pintype "passive"))
      (node (ref "RN12") (pin "7") (pinfunction "1_7") (pintype "passive"))
    )
    (net (code "148") (name "Net-(RN11D-2)") (class "Default")
      (node (ref "RN11") (pin "13") (pinfunction "2_13") (pintype "passive"))
      (node (ref "RN12") (pin "12") (pinfunction "2_12") (pintype "passive"))
      (node (ref "RN12") (pin "6") (pinfunction "1_6") (pintype "passive"))
    )
    (net (code "149") (name "Net-(RN11E-2)") (class "Default")
      (node (ref "RN11") (pin "12") (pinfunction "2_12") (pintype "passive"))
      (node (ref "RN12") (pin "13") (pinfunction "2_13") (pintype "passive"))
      (node (ref "RN12") (pin "5") (pinfunction "1_5") (pintype "passive"))
    )
    (net (code "150") (name "Net-(RN11F-2)") (class "Default")
      (node (ref "RN11") (pin "11") (pinfunction "2_11") (pintype "passive"))
      (node (ref "RN12") (pin "14") (pinfunction "2_14") (pintype "passive"))
      (node (ref "RN12") (pin "4") (pinfunction "1_4") (pintype "passive"))
    )
    (net (code "151") (name "Net-(RN11G-2)") (class "Default")
      (node (ref "RN11") (pin "10") (pinfunction "2_10") (pintype "passive"))
      (node (ref "RN12") (pin "15") (pinfunction "2_15") (pintype "passive"))
      (node (ref "RN12") (pin "3") (pinfunction "1_3") (pintype "passive"))
    )
    (net (code "152") (name "Net-(RN11H-2)") (class "Default")
      (node (ref "R32") (pin "2") (pinfunction "2_2") (pintype "passive"))
      (node (ref "RN11") (pin "9") (pinfunction "2_9") (pintype "passive"))
      (node (ref "RN12") (pin "2") (pinfunction "1_2") (pintype "passive"))
    )
    (net (code "153") (name "Net-(RN14A-2)") (class "Default")
      (node (ref "RN14") (pin "16") (pinfunction "2_16") (pintype "passive"))
      (node (ref "RN17") (pin "7") (pinfunction "1_7") (pintype "passive"))
      (node (ref "RN17") (pin "9") (pinfunction "2_9") (pintype "passive"))
    )
    (net (code "154") (name "Net-(RN14B-2)") (class "Default")
      (node (ref "RN14") (pin "15") (pinfunction "2_15") (pintype "passive"))
      (node (ref "RN17") (pin "10") (pinfunction "2_10") (pintype "passive"))
      (node (ref "RN17") (pin "6") (pinfunction "1_6") (pintype "passive"))
    )
    (net (code "155") (name "Net-(RN14C-2)") (class "Default")
      (node (ref "RN14") (pin "14") (pinfunction "2_14") (pintype "passive"))
      (node (ref "RN17") (pin "11") (pinfunction "2_11") (pintype "passive"))
      (node (ref "RN17") (pin "5") (pinfunction "1_5") (pintype "passive"))
    )
    (net (code "156") (name "Net-(RN14D-2)") (class "Default")
      (node (ref "RN14") (pin "13") (pinfunction "2_13") (pintype "passive"))
      (node (ref "RN17") (pin "12") (pinfunction "2_12") (pintype "passive"))
      (node (ref "RN17") (pin "4") (pinfunction "1_4") (pintype "passive"))
    )
    (net (code "157") (name "Net-(RN14E-2)") (class "Default")
      (node (ref "RN14") (pin "12") (pinfunction "2_12") (pintype "passive"))
      (node (ref "RN17") (pin "13") (pinfunction "2_13") (pintype "passive"))
      (node (ref "RN17") (pin "3") (pinfunction "1_3") (pintype "passive"))
    )
    (net (code "158") (name "Net-(RN14F-2)") (class "Default")
      (node (ref "RN14") (pin "11") (pinfunction "2_11") (pintype "passive"))
      (node (ref "RN17") (pin "14") (pinfunction "2_14") (pintype "passive"))
      (node (ref "RN17") (pin "2") (pinfunction "1_2") (pintype "passive"))
    )
    (net (code "159") (name "Net-(RN14G-2)") (class "Default")
      (node (ref "RN14") (pin "10") (pinfunction "2_10") (pintype "passive"))
      (node (ref "RN17") (pin "1") (pinfunction "1_1") (pintype "passive"))
      (node (ref "RN17") (pin "15") (pinfunction "2_15") (pintype "passive"))
    )
    (net (code "160") (name "Net-(RN15A-2)") (class "Default")
      (node (ref "R33") (pin "2") (pinfunction "2_2") (pintype "passive"))
      (node (ref "RN15") (pin "16") (pinfunction "2_16") (pintype "passive"))
      (node (ref "RN16") (pin "7") (pinfunction "1_7") (pintype "passive"))
    )
    (net (code "161") (name "Net-(RN15B-2)") (class "Default")
      (node (ref "RN15") (pin "15") (pinfunction "2_15") (pintype "passive"))
      (node (ref "RN16") (pin "10") (pinfunction "2_10") (pintype "passive"))
      (node (ref "RN16") (pin "6") (pinfunction "1_6") (pintype "passive"))
    )
    (net (code "162") (name "Net-(RN15C-2)") (class "Default")
      (node (ref "RN15") (pin "14") (pinfunction "2_14") (pintype "passive"))
      (node (ref "RN16") (pin "11") (pinfunction "2_11") (pintype "passive"))
      (node (ref "RN16") (pin "5") (pinfunction "1_5") (pintype "passive"))
    )
    (net (code "163") (name "Net-(RN15D-2)") (class "Default")
      (node (ref "RN15") (pin "13") (pinfunction "2_13") (pintype "passive"))
      (node (ref "RN16") (pin "12") (pinfunction "2_12") (pintype "passive"))
      (node (ref "RN16") (pin "4") (pinfunction "1_4") (pintype "passive"))
    )
    (net (code "164") (name "Net-(RN15E-2)") (class "Default")
      (node (ref "RN15") (pin "12") (pinfunction "2_12") (pintype "passive"))
      (node (ref "RN16") (pin "13") (pinfunction "2_13") (pintype "passive"))
      (node (ref "RN16") (pin "3") (pinfunction "1_3") (pintype "passive"))
    )
    (net (code "165") (name "Net-(RN15F-2)") (class "Default")
      (node (ref "RN15") (pin "11") (pinfunction "2_11") (pintype "passive"))
      (node (ref "RN16") (pin "14") (pinfunction "2_14") (pintype "passive"))
      (node (ref "RN16") (pin "2") (pinfunction "1_2") (pintype "passive"))
    )
    (net (code "166") (name "Net-(RN15G-2)") (class "Default")
      (node (ref "RN15") (pin "10") (pinfunction "2_10") (pintype "passive"))
      (node (ref "RN16") (pin "1") (pinfunction "1_1") (pintype "passive"))
      (node (ref "RN16") (pin "15") (pinfunction "2_15") (pintype "passive"))
    )
    (net (code "167") (name "Net-(RN15H-2)") (class "Default")
      (node (ref "RN15") (pin "9") (pinfunction "2_9") (pintype "passive"))
      (node (ref "RN16") (pin "16") (pinfunction "2_16") (pintype "passive"))
      (node (ref "RN17") (pin "8") (pinfunction "1_8") (pintype "passive"))
    )
    (net (code "168") (name "Net-(S1A-P)") (class "Default")
      (node (ref "S1") (pin "2") (pinfunction "P_2") (pintype "passive"))
      (node (ref "U5") (pin "3") (pinfunction "EN_3") (pintype "input"))
    )
    (net (code "169") (name "Net-(S1A-S)") (class "Default")
      (node (ref "R168") (pin "2") (pinfunction "2_2") (pintype "passive"))
      (node (ref "S1") (pin "3") (pinfunction "S_3") (pintype "passive"))
    )
    (net (code "170") (name "Net-(SAMD21-PA00{slash}EINT0{slash}SERCOM1.0)") (class "Default")
      (node (ref "C49") (pin "1") (pinfunction "1_1") (pintype "passive"))
      (node (ref "SAMD21") (pin "1") (pinfunction "PA00/EINT0/SERCOM1.0_1") (pintype "bidirectional"))
      (node (ref "X2") (pin "P$1") (pinfunction "P$1_P$1") (pintype "bidirectional"))
    )
    (net (code "171") (name "Net-(SAMD21-PA01{slash}EINT1{slash}SERCOM1.1)") (class "Default")
      (node (ref "C50") (pin "1") (pinfunction "1_1") (pintype "passive"))
      (node (ref "SAMD21") (pin "2") (pinfunction "PA01/EINT1/SERCOM1.1_2") (pintype "bidirectional"))
      (node (ref "X2") (pin "P$2") (pinfunction "P$2_P$2") (pintype "bidirectional"))
    )
    (net (code "172") (name "Net-(SAMD21-VDDCORE)") (class "Default")
      (node (ref "C32") (pin "1") (pinfunction "1_1") (pintype "passive"))
      (node (ref "SAMD21") (pin "43") (pinfunction "VDDCORE_43") (pintype "power_in"))
    )
    (net (code "173") (name "Net-(U$1A-C)") (class "Default")
      (node (ref "C1") (pin "1") (pinfunction "1_1") (pintype "passive"))
      (node (ref "R2") (pin "1") (pinfunction "1_1") (pintype "passive"))
      (node (ref "R42") (pin "1") (pinfunction "1_1") (pintype "passive"))
      (node (ref "R7") (pin "1") (pinfunction "1_1") (pintype "passive"))
      (node (ref "U$1") (pin "3") (pinfunction "C_3") (pintype "passive"))
      (node (ref "U1") (pin "2") (pinfunction "-IN_2") (pintype "input"))
      (node (ref "U2") (pin "3") (pinfunction "C_3") (pintype "passive"))
    )
    (net (code "174") (name "Net-(U$1A-E)") (class "Default")
      (node (ref "R1") (pin "2") (pinfunction "2_2") (pintype "passive"))
      (node (ref "U$1") (pin "4") (pinfunction "E_4") (pintype "passive"))
      (node (ref "U$1") (pin "5") (pinfunction "E_5") (pintype "passive"))
    )
    (net (code "175") (name "Net-(U$1B-C)") (class "Default")
      (node (ref "C2") (pin "1") (pinfunction "1_1") (pintype "passive"))
      (node (ref "R3") (pin "2") (pinfunction "2_2") (pintype "passive"))
      (node (ref "U$1") (pin "6") (pinfunction "C_6") (pintype "passive"))
      (node (ref "U1") (pin "13") (pinfunction "-IN_13") (pintype "input"))
      (node (ref "U2") (pin "6") (pinfunction "C_6") (pintype "passive"))
    )
    (net (code "176") (name "Net-(U$2A-GNDPLL)") (class "Default")
      (node (ref "C11") (pin "2") (pinfunction "2_2") (pintype "passive"))
      (node (ref "C12") (pin "1") (pinfunction "1_1") (pintype "passive"))
      (node (ref "U$2") (pin "127") (pinfunction "GNDPLL_127") (pintype "bidirectional"))
    )
    (net (code "177") (name "Net-(U$2A-VCCPLL)") (class "Default")
      (node (ref "C11") (pin "1") (pinfunction "1_1") (pintype "passive"))
      (node (ref "C12") (pin "2") (pinfunction "2_2") (pintype "passive"))
      (node (ref "R9") (pin "1") (pinfunction "1_1") (pintype "passive"))
      (node (ref "U$2") (pin "126") (pinfunction "VCCPLL_126") (pintype "bidirectional"))
    )
    (net (code "178") (name "Net-(U$2B-IOR_166)") (class "Default")
      (node (ref "RN4") (pin "1") (pinfunction "1_1") (pintype "passive"))
      (node (ref "U$2") (pin "106") (pinfunction "IOR_166_106") (pintype "bidirectional"))
    )
    (net (code "179") (name "Net-(U$2C-GNDPLL)") (class "Default")
      (node (ref "C10") (pin "1") (pinfunction "1_1") (pintype "passive"))
      (node (ref "C9") (pin "2") (pinfunction "2_2") (pintype "passive"))
      (node (ref "U$2") (pin "53") (pinfunction "GNDPLL_53") (pintype "bidirectional"))
    )
    (net (code "180") (name "Net-(U$2C-VCCPLL)") (class "Default")
      (node (ref "C10") (pin "2") (pinfunction "2_2") (pintype "passive"))
      (node (ref "C9") (pin "1") (pinfunction "1_1") (pintype "passive"))
      (node (ref "R8") (pin "1") (pinfunction "1_1") (pintype "passive"))
      (node (ref "U$2") (pin "54") (pinfunction "VCCPLL_54") (pintype "bidirectional"))
    )
    (net (code "181") (name "Net-(U$2D-IOL_8B)") (class "Default")
      (node (ref "R30") (pin "2") (pinfunction "2_2") (pintype "passive"))
      (node (ref "U$2") (pin "12") (pinfunction "IOL_8B_12") (pintype "bidirectional"))
    )
    (net (code "182") (name "Net-(U$2D-IOL_10A)") (class "Default")
      (node (ref "RN5") (pin "1") (pinfunction "1_1") (pintype "passive"))
      (node (ref "U$2") (pin "15") (pinfunction "IOL_10A_15") (pintype "bidirectional"))
    )
    (net (code "183") (name "Net-(U$3A-C)") (class "Default")
      (node (ref "C3") (pin "1") (pinfunction "1_1") (pintype "passive"))
      (node (ref "R16") (pin "1") (pinfunction "1_1") (pintype "passive"))
      (node (ref "R17") (pin "2") (pinfunction "2_2") (pintype "passive"))
      (node (ref "U$3") (pin "3") (pinfunction "C_3") (pintype "passive"))
      (node (ref "U1") (pin "6") (pinfunction "-IN_6") (pintype "input"))
      (node (ref "U6") (pin "3") (pinfunction "C_3") (pintype "passive"))
    )
    (net (code "184") (name "Net-(U$3A-E)") (class "Default")
      (node (ref "R4") (pin "2") (pinfunction "2_2") (pintype "passive"))
      (node (ref "U$3") (pin "4") (pinfunction "E_4") (pintype "passive"))
      (node (ref "U$3") (pin "5") (pinfunction "E_5") (pintype "passive"))
    )
    (net (code "185") (name "Net-(U$3B-C)") (class "Default")
      (node (ref "C22") (pin "1") (pinfunction "1_1") (pintype "passive"))
      (node (ref "R13") (pin "2") (pinfunction "2_2") (pintype "passive"))
      (node (ref "U$3") (pin "6") (pinfunction "C_6") (pintype "passive"))
      (node (ref "U1") (pin "9") (pinfunction "-IN_9") (pintype "input"))
      (node (ref "U6") (pin "6") (pinfunction "C_6") (pintype "passive"))
    )
    (net (code "186") (name "Net-(U$4A-C)") (class "Default")
      (node (ref "C26") (pin "1") (pinfunction "1_1") (pintype "passive"))
      (node (ref "R22") (pin "1") (pinfunction "1_1") (pintype "passive"))
      (node (ref "R23") (pin "2") (pinfunction "2_2") (pintype "passive"))
      (node (ref "U$4") (pin "3") (pinfunction "C_3") (pintype "passive"))
      (node (ref "U10") (pin "3") (pinfunction "C_3") (pintype "passive"))
      (node (ref "U9") (pin "2") (pinfunction "-IN_2") (pintype "input"))
    )
    (net (code "187") (name "Net-(U$4A-E)") (class "Default")
      (node (ref "R18") (pin "2") (pinfunction "2_2") (pintype "passive"))
      (node (ref "U$4") (pin "4") (pinfunction "E_4") (pintype "passive"))
      (node (ref "U$4") (pin "5") (pinfunction "E_5") (pintype "passive"))
    )
    (net (code "188") (name "Net-(U$4B-C)") (class "Default")
      (node (ref "C35") (pin "1") (pinfunction "1_1") (pintype "passive"))
      (node (ref "R19") (pin "2") (pinfunction "2_2") (pintype "passive"))
      (node (ref "U$4") (pin "6") (pinfunction "C_6") (pintype "passive"))
      (node (ref "U10") (pin "6") (pinfunction "C_6") (pintype "passive"))
      (node (ref "U9") (pin "13") (pinfunction "-IN_13") (pintype "input"))
    )
    (net (code "189") (name "Net-(U$5-OE{slash}ST)") (class "Default")
      (node (ref "R61") (pin "1") (pinfunction "1_1") (pintype "passive"))
      (node (ref "U$5") (pin "1") (pinfunction "OE/ST_1") (pintype "bidirectional"))
    )
    (net (code "190") (name "Net-(U$7A-C)") (class "Default")
      (node (ref "C38") (pin "1") (pinfunction "1_1") (pintype "passive"))
      (node (ref "R28") (pin "1") (pinfunction "1_1") (pintype "passive"))
      (node (ref "R29") (pin "2") (pinfunction "2_2") (pintype "passive"))
      (node (ref "U$7") (pin "3") (pinfunction "C_3") (pintype "passive"))
      (node (ref "U16") (pin "3") (pinfunction "C_3") (pintype "passive"))
      (node (ref "U9") (pin "6") (pinfunction "-IN_6") (pintype "input"))
    )
    (net (code "191") (name "Net-(U$7A-E)") (class "Default")
      (node (ref "R24") (pin "2") (pinfunction "2_2") (pintype "passive"))
      (node (ref "U$7") (pin "4") (pinfunction "E_4") (pintype "passive"))
      (node (ref "U$7") (pin "5") (pinfunction "E_5") (pintype "passive"))
    )
    (net (code "192") (name "Net-(U$7B-C)") (class "Default")
      (node (ref "C39") (pin "1") (pinfunction "1_1") (pintype "passive"))
      (node (ref "R25") (pin "2") (pinfunction "2_2") (pintype "passive"))
      (node (ref "U$7") (pin "6") (pinfunction "C_6") (pintype "passive"))
      (node (ref "U16") (pin "6") (pinfunction "C_6") (pintype "passive"))
      (node (ref "U9") (pin "9") (pinfunction "-IN_9") (pintype "input"))
    )
    (net (code "193") (name "Net-(U$8A-C)") (class "Default")
      (node (ref "C43") (pin "1") (pinfunction "1_1") (pintype "passive"))
      (node (ref "R35") (pin "1") (pinfunction "1_1") (pintype "passive"))
      (node (ref "U$8") (pin "3") (pinfunction "C_3") (pintype "passive"))
      (node (ref "U14") (pin "2") (pinfunction "-IN_2") (pintype "input"))
      (node (ref "U21") (pin "3") (pinfunction "C_3") (pintype "passive"))
    )
    (net (code "194") (name "Net-(U$8A-E)") (class "Default")
      (node (ref "R34") (pin "2") (pinfunction "2_2") (pintype "passive"))
      (node (ref "U$8") (pin "4") (pinfunction "E_4") (pintype "passive"))
      (node (ref "U$8") (pin "5") (pinfunction "E_5") (pintype "passive"))
    )
    (net (code "195") (name "Net-(U$8B-C)") (class "Default")
      (node (ref "C44") (pin "1") (pinfunction "1_1") (pintype "passive"))
      (node (ref "R36") (pin "2") (pinfunction "2_2") (pintype "passive"))
      (node (ref "U$8") (pin "6") (pinfunction "C_6") (pintype "passive"))
      (node (ref "U14") (pin "13") (pinfunction "-IN_13") (pintype "input"))
      (node (ref "U21") (pin "6") (pinfunction "C_6") (pintype "passive"))
    )
    (net (code "196") (name "Net-(U$9A-C)") (class "Default")
      (node (ref "C45") (pin "1") (pinfunction "1_1") (pintype "passive"))
      (node (ref "R47") (pin "1") (pinfunction "1_1") (pintype "passive"))
      (node (ref "U$9") (pin "3") (pinfunction "C_3") (pintype "passive"))
      (node (ref "U14") (pin "6") (pinfunction "-IN_6") (pintype "input"))
      (node (ref "U24") (pin "3") (pinfunction "C_3") (pintype "passive"))
    )
    (net (code "197") (name "Net-(U$9A-E)") (class "Default")
      (node (ref "R46") (pin "2") (pinfunction "2_2") (pintype "passive"))
      (node (ref "U$9") (pin "4") (pinfunction "E_4") (pintype "passive"))
      (node (ref "U$9") (pin "5") (pinfunction "E_5") (pintype "passive"))
    )
    (net (code "198") (name "Net-(U$9B-C)") (class "Default")
      (node (ref "C46") (pin "1") (pinfunction "1_1") (pintype "passive"))
      (node (ref "R48") (pin "2") (pinfunction "2_2") (pintype "passive"))
      (node (ref "U$9") (pin "6") (pinfunction "C_6") (pintype "passive"))
      (node (ref "U14") (pin "9") (pinfunction "-IN_9") (pintype "input"))
      (node (ref "U24") (pin "6") (pinfunction "C_6") (pintype "passive"))
    )
    (net (code "199") (name "Net-(U$15A-C)") (class "Default")
      (node (ref "C56") (pin "1") (pinfunction "1_1") (pintype "passive"))
      (node (ref "R51") (pin "1") (pinfunction "1_1") (pintype "passive"))
      (node (ref "R70") (pin "1") (pinfunction "1_1") (pintype "passive"))
      (node (ref "R71") (pin "1") (pinfunction "1_1") (pintype "passive"))
      (node (ref "U$15") (pin "3") (pinfunction "C_3") (pintype "passive"))
      (node (ref "U27") (pin "3") (pinfunction "C_3") (pintype "passive"))
      (node (ref "U8") (pin "6") (pinfunction "-IN_6") (pintype "input"))
    )
    (net (code "200") (name "Net-(U$15A-E)") (class "Default")
      (node (ref "R50") (pin "2") (pinfunction "2_2") (pintype "passive"))
      (node (ref "U$15") (pin "4") (pinfunction "E_4") (pintype "passive"))
      (node (ref "U$15") (pin "5") (pinfunction "E_5") (pintype "passive"))
    )
    (net (code "201") (name "Net-(U$15B-C)") (class "Default")
      (node (ref "C57") (pin "1") (pinfunction "1_1") (pintype "passive"))
      (node (ref "R52") (pin "2") (pinfunction "2_2") (pintype "passive"))
      (node (ref "U$15") (pin "6") (pinfunction "C_6") (pintype "passive"))
      (node (ref "U27") (pin "6") (pinfunction "C_6") (pintype "passive"))
      (node (ref "U8") (pin "9") (pinfunction "-IN_9") (pintype "input"))
    )
    (net (code "202") (name "Net-(U$16A-C)") (class "Default")
      (node (ref "C58") (pin "1") (pinfunction "1_1") (pintype "passive"))
      (node (ref "R55") (pin "1") (pinfunction "1_1") (pintype "passive"))
      (node (ref "U$16") (pin "3") (pinfunction "C_3") (pintype "passive"))
      (node (ref "U30") (pin "3") (pinfunction "C_3") (pintype "passive"))
      (node (ref "U8") (pin "2") (pinfunction "-IN_2") (pintype "input"))
    )
    (net (code "203") (name "Net-(U$16A-E)") (class "Default")
      (node (ref "R54") (pin "2") (pinfunction "2_2") (pintype "passive"))
      (node (ref "U$16") (pin "4") (pinfunction "E_4") (pintype "passive"))
      (node (ref "U$16") (pin "5") (pinfunction "E_5") (pintype "passive"))
    )
    (net (code "204") (name "Net-(U$16B-C)") (class "Default")
      (node (ref "C59") (pin "1") (pinfunction "1_1") (pintype "passive"))
      (node (ref "R56") (pin "2") (pinfunction "2_2") (pintype "passive"))
      (node (ref "U$16") (pin "6") (pinfunction "C_6") (pintype "passive"))
      (node (ref "U30") (pin "6") (pinfunction "C_6") (pintype "passive"))
      (node (ref "U8") (pin "13") (pinfunction "-IN_13") (pintype "input"))
    )
    (net (code "205") (name "Net-(U$19-BYPASS)") (class "Default")
      (node (ref "C60") (pin "1") (pinfunction "1_1") (pintype "passive"))
      (node (ref "U$19") (pin "2") (pinfunction "BYPASS_2") (pintype "bidirectional"))
      (node (ref "U$19") (pin "3") (pinfunction "VIN+_3") (pintype "bidirectional"))
    )
    (net (code "206") (name "Net-(U$19-VIN-)") (class "Default")
      (node (ref "R66") (pin "1") (pinfunction "1_1") (pintype "passive"))
      (node (ref "R75") (pin "2") (pinfunction "2_2") (pintype "passive"))
      (node (ref "U$19") (pin "4") (pinfunction "VIN-_4") (pintype "bidirectional"))
    )
    (net (code "207") (name "Net-(U1A-OUT)") (class "Default")
      (node (ref "C1") (pin "2") (pinfunction "2_2") (pintype "passive"))
      (node (ref "R1") (pin "1") (pinfunction "1_1") (pintype "passive"))
      (node (ref "U1") (pin "1") (pinfunction "OUT_1") (pintype "output"))
    )
    (net (code "208") (name "Net-(U1B-OUT)") (class "Default")
      (node (ref "C3") (pin "2") (pinfunction "2_2") (pintype "passive"))
      (node (ref "R4") (pin "1") (pinfunction "1_1") (pintype "passive"))
      (node (ref "U1") (pin "7") (pinfunction "OUT_7") (pintype "output"))
    )
    (net (code "209") (name "Net-(U1C-OUT)") (class "Default")
      (node (ref "C22") (pin "2") (pinfunction "2_2") (pintype "passive"))
      (node (ref "R13") (pin "1") (pinfunction "1_1") (pintype "passive"))
      (node (ref "R14") (pin "2") (pinfunction "2_2") (pintype "passive"))
      (node (ref "U1") (pin "8") (pinfunction "OUT_8") (pintype "output"))
    )
    (net (code "210") (name "Net-(U1D-OUT)") (class "Default")
      (node (ref "C2") (pin "2") (pinfunction "2_2") (pintype "passive"))
      (node (ref "R3") (pin "1") (pinfunction "1_1") (pintype "passive"))
      (node (ref "R5") (pin "2") (pinfunction "2_2") (pintype "passive"))
      (node (ref "U1") (pin "14") (pinfunction "OUT_14") (pintype "output"))
    )
    (net (code "211") (name "Net-(U2A-E)") (class "Default")
      (node (ref "U2") (pin "4") (pinfunction "E_4") (pintype "passive"))
      (node (ref "U2") (pin "5") (pinfunction "E_5") (pintype "passive"))
      (node (ref "U3") (pin "3") (pinfunction "C_3") (pintype "passive"))
    )
    (net (code "212") (name "Net-(U3A-B)") (class "Default")
      (node (ref "R6") (pin "2") (pinfunction "2_2") (pintype "passive"))
      (node (ref "U3") (pin "1") (pinfunction "B_1") (pintype "passive"))
      (node (ref "U3") (pin "2") (pinfunction "B_2") (pintype "passive"))
      (node (ref "U3") (pin "6") (pinfunction "C_6") (pintype "passive"))
    )
    (net (code "213") (name "Net-(U4A-+IN)") (class "Default")
      (node (ref "R169") (pin "1") (pinfunction "1_1") (pintype "passive"))
      (node (ref "R67") (pin "1") (pinfunction "1_1") (pintype "passive"))
      (node (ref "U4") (pin "3") (pinfunction "+IN_3") (pintype "input"))
    )
    (net (code "214") (name "Net-(U4A--IN)") (class "Default")
      (node (ref "R63") (pin "1") (pinfunction "1_1") (pintype "passive"))
      (node (ref "R65") (pin "2") (pinfunction "2_2") (pintype "passive"))
      (node (ref "U4") (pin "2") (pinfunction "-IN_2") (pintype "input"))
    )
    (net (code "215") (name "Net-(U4B-+IN)") (class "Default")
      (node (ref "R181") (pin "2") (pinfunction "2_2") (pintype "passive"))
      (node (ref "R184") (pin "2") (pinfunction "2_2") (pintype "passive"))
      (node (ref "U4") (pin "5") (pinfunction "+IN_5") (pintype "input"))
    )
    (net (code "216") (name "Net-(U4B--IN)") (class "Default")
      (node (ref "R178") (pin "1") (pinfunction "1_1") (pintype "passive"))
      (node (ref "R180") (pin "2") (pinfunction "2_2") (pintype "passive"))
      (node (ref "U4") (pin "6") (pinfunction "-IN_6") (pintype "input"))
    )
    (net (code "217") (name "Net-(U4C-+IN)") (class "Default")
      (node (ref "R172") (pin "2") (pinfunction "2_2") (pintype "passive"))
      (node (ref "R173") (pin "2") (pinfunction "2_2") (pintype "passive"))
      (node (ref "U4") (pin "10") (pinfunction "+IN_10") (pintype "input"))
    )
    (net (code "218") (name "Net-(U4C--IN)") (class "Default")
      (node (ref "R170") (pin "1") (pinfunction "1_1") (pintype "passive"))
      (node (ref "R171") (pin "2") (pinfunction "2_2") (pintype "passive"))
      (node (ref "U4") (pin "9") (pinfunction "-IN_9") (pintype "input"))
    )
    (net (code "219") (name "Net-(U4D-+IN)") (class "Default")
      (node (ref "R187") (pin "2") (pinfunction "2_2") (pintype "passive"))
      (node (ref "R188") (pin "2") (pinfunction "2_2") (pintype "passive"))
      (node (ref "U4") (pin "12") (pinfunction "+IN_12") (pintype "input"))
    )
    (net (code "220") (name "Net-(U4D--IN)") (class "Default")
      (node (ref "R185") (pin "2") (pinfunction "2_2") (pintype "passive"))
      (node (ref "R186") (pin "1") (pinfunction "1_1") (pintype "passive"))
      (node (ref "U4") (pin "13") (pinfunction "-IN_13") (pintype "input"))
    )
    (net (code "221") (name "Net-(U6A-E)") (class "Default")
      (node (ref "U6") (pin "4") (pinfunction "E_4") (pintype "passive"))
      (node (ref "U6") (pin "5") (pinfunction "E_5") (pintype "passive"))
      (node (ref "U7") (pin "3") (pinfunction "C_3") (pintype "passive"))
    )
    (net (code "222") (name "Net-(U7A-B)") (class "Default")
      (node (ref "R15") (pin "2") (pinfunction "2_2") (pintype "passive"))
      (node (ref "U7") (pin "1") (pinfunction "B_1") (pintype "passive"))
      (node (ref "U7") (pin "2") (pinfunction "B_2") (pintype "passive"))
      (node (ref "U7") (pin "6") (pinfunction "C_6") (pintype "passive"))
    )
    (net (code "223") (name "Net-(U8A-OUT)") (class "Default")
      (node (ref "C58") (pin "2") (pinfunction "2_2") (pintype "passive"))
      (node (ref "R54") (pin "1") (pinfunction "1_1") (pintype "passive"))
      (node (ref "U8") (pin "1") (pinfunction "OUT_1") (pintype "output"))
    )
    (net (code "224") (name "Net-(U8B-OUT)") (class "Default")
      (node (ref "C56") (pin "2") (pinfunction "2_2") (pintype "passive"))
      (node (ref "R50") (pin "1") (pinfunction "1_1") (pintype "passive"))
      (node (ref "U8") (pin "7") (pinfunction "OUT_7") (pintype "output"))
    )
    (net (code "225") (name "Net-(U9A-OUT)") (class "Default")
      (node (ref "C26") (pin "2") (pinfunction "2_2") (pintype "passive"))
      (node (ref "R18") (pin "1") (pinfunction "1_1") (pintype "passive"))
      (node (ref "U9") (pin "1") (pinfunction "OUT_1") (pintype "output"))
    )
    (net (code "226") (name "Net-(U9B-OUT)") (class "Default")
      (node (ref "C38") (pin "2") (pinfunction "2_2") (pintype "passive"))
      (node (ref "R24") (pin "1") (pinfunction "1_1") (pintype "passive"))
      (node (ref "U9") (pin "7") (pinfunction "OUT_7") (pintype "output"))
    )
    (net (code "227") (name "Net-(U9C-OUT)") (class "Default")
      (node (ref "C39") (pin "2") (pinfunction "2_2") (pintype "passive"))
      (node (ref "R25") (pin "1") (pinfunction "1_1") (pintype "passive"))
      (node (ref "R26") (pin "2") (pinfunction "2_2") (pintype "passive"))
      (node (ref "U9") (pin "8") (pinfunction "OUT_8") (pintype "output"))
    )
    (net (code "228") (name "Net-(U9D-OUT)") (class "Default")
      (node (ref "C35") (pin "2") (pinfunction "2_2") (pintype "passive"))
      (node (ref "R19") (pin "1") (pinfunction "1_1") (pintype "passive"))
      (node (ref "R20") (pin "2") (pinfunction "2_2") (pintype "passive"))
      (node (ref "U9") (pin "14") (pinfunction "OUT_14") (pintype "output"))
    )
    (net (code "229") (name "Net-(U10A-E)") (class "Default")
      (node (ref "U10") (pin "4") (pinfunction "E_4") (pintype "passive"))
      (node (ref "U10") (pin "5") (pinfunction "E_5") (pintype "passive"))
      (node (ref "U11") (pin "3") (pinfunction "C_3") (pintype "passive"))
    )
    (net (code "230") (name "Net-(U11A-B)") (class "Default")
      (node (ref "R21") (pin "2") (pinfunction "2_2") (pintype "passive"))
      (node (ref "U11") (pin "1") (pinfunction "B_1") (pintype "passive"))
      (node (ref "U11") (pin "2") (pinfunction "B_2") (pintype "passive"))
      (node (ref "U11") (pin "6") (pinfunction "C_6") (pintype "passive"))
    )
    (net (code "231") (name "Net-(U12-EN1)") (class "Default")
      (node (ref "R166") (pin "1") (pinfunction "1_1") (pintype "passive"))
      (node (ref "U12") (pin "1") (pinfunction "EN1_1") (pintype "input"))
    )
    (net (code "232") (name "Net-(U12-EN2)") (class "Default")
      (node (ref "R167") (pin "1") (pinfunction "1_1") (pintype "passive"))
      (node (ref "U12") (pin "3") (pinfunction "EN2_3") (pintype "input"))
    )
    (net (code "233") (name "Net-(U13A-+IN)") (class "Default")
      (node (ref "C21") (pin "1") (pinfunction "1_1") (pintype "passive"))
      (node (ref "R73") (pin "2") (pinfunction "2_2") (pintype "passive"))
      (node (ref "U13") (pin "3") (pinfunction "+IN_3") (pintype "input"))
    )
    (net (code "234") (name "Net-(U13A--IN)") (class "Default")
      (node (ref "R12") (pin "2") (pinfunction "2_2") (pintype "passive"))
      (node (ref "R72") (pin "1") (pinfunction "1_1") (pintype "passive"))
      (node (ref "U13") (pin "4") (pinfunction "-IN_4") (pintype "input"))
    )
    (net (code "235") (name "Net-(U13A-OUT)") (class "Default")
      (node (ref "R72") (pin "2") (pinfunction "2_2") (pintype "passive"))
      (node (ref "R74") (pin "2") (pinfunction "2_2") (pintype "passive"))
      (node (ref "U13") (pin "1") (pinfunction "OUT_1") (pintype "output"))
    )
    (net (code "236") (name "Net-(U14A-OUT)") (class "Default")
      (node (ref "C43") (pin "2") (pinfunction "2_2") (pintype "passive"))
      (node (ref "R34") (pin "1") (pinfunction "1_1") (pintype "passive"))
      (node (ref "U14") (pin "1") (pinfunction "OUT_1") (pintype "output"))
    )
    (net (code "237") (name "Net-(U14B-OUT)") (class "Default")
      (node (ref "C45") (pin "2") (pinfunction "2_2") (pintype "passive"))
      (node (ref "R46") (pin "1") (pinfunction "1_1") (pintype "passive"))
      (node (ref "U14") (pin "7") (pinfunction "OUT_7") (pintype "output"))
    )
    (net (code "238") (name "Net-(U14C-OUT)") (class "Default")
      (node (ref "C46") (pin "2") (pinfunction "2_2") (pintype "passive"))
      (node (ref "C88") (pin "1") (pinfunction "1_1") (pintype "passive"))
      (node (ref "R48") (pin "1") (pinfunction "1_1") (pintype "passive"))
      (node (ref "U14") (pin "8") (pinfunction "OUT_8") (pintype "output"))
    )
    (net (code "239") (name "Net-(U15A--IN)") (class "Default")
      (node (ref "C4") (pin "1") (pinfunction "1_1") (pintype "passive"))
      (node (ref "R5") (pin "1") (pinfunction "1_1") (pintype "passive"))
      (node (ref "U15") (pin "2") (pinfunction "-IN_2") (pintype "input"))
    )
    (net (code "240") (name "Net-(U15A-OUT)") (class "Default")
      (node (ref "C4") (pin "2") (pinfunction "2_2") (pintype "passive"))
      (node (ref "C53") (pin "2") (pinfunction "2_2") (pintype "passive"))
      (node (ref "R7") (pin "2") (pinfunction "2_2") (pintype "passive"))
      (node (ref "U15") (pin "1") (pinfunction "OUT_1") (pintype "output"))
    )
    (net (code "241") (name "Net-(U15B--IN)") (class "Default")
      (node (ref "C36") (pin "1") (pinfunction "1_1") (pintype "passive"))
      (node (ref "R20") (pin "1") (pinfunction "1_1") (pintype "passive"))
      (node (ref "U15") (pin "6") (pinfunction "-IN_6") (pintype "input"))
    )
    (net (code "242") (name "Net-(U15B-OUT)") (class "Default")
      (node (ref "C36") (pin "2") (pinfunction "2_2") (pintype "passive"))
      (node (ref "C37") (pin "2") (pinfunction "2_2") (pintype "passive"))
      (node (ref "R22") (pin "2") (pinfunction "2_2") (pintype "passive"))
      (node (ref "U15") (pin "7") (pinfunction "OUT_7") (pintype "output"))
    )
    (net (code "243") (name "Net-(U15C--IN)") (class "Default")
      (node (ref "C40") (pin "1") (pinfunction "1_1") (pintype "passive"))
      (node (ref "R26") (pin "1") (pinfunction "1_1") (pintype "passive"))
      (node (ref "U15") (pin "9") (pinfunction "-IN_9") (pintype "input"))
    )
    (net (code "244") (name "Net-(U15D--IN)") (class "Default")
      (node (ref "C23") (pin "1") (pinfunction "1_1") (pintype "passive"))
      (node (ref "R14") (pin "1") (pinfunction "1_1") (pintype "passive"))
      (node (ref "U15") (pin "13") (pinfunction "-IN_13") (pintype "input"))
    )
    (net (code "245") (name "Net-(U16A-E)") (class "Default")
      (node (ref "U16") (pin "4") (pinfunction "E_4") (pintype "passive"))
      (node (ref "U16") (pin "5") (pinfunction "E_5") (pintype "passive"))
      (node (ref "U17") (pin "3") (pinfunction "C_3") (pintype "passive"))
    )
    (net (code "246") (name "Net-(U17A-B)") (class "Default")
      (node (ref "R27") (pin "2") (pinfunction "2_2") (pintype "passive"))
      (node (ref "U17") (pin "1") (pinfunction "B_1") (pintype "passive"))
      (node (ref "U17") (pin "2") (pinfunction "B_2") (pintype "passive"))
      (node (ref "U17") (pin "6") (pinfunction "C_6") (pintype "passive"))
    )
    (net (code "247") (name "Net-(U18A--IN)") (class "Default")
      (node (ref "R191") (pin "1") (pinfunction "1_1") (pintype "passive"))
      (node (ref "R192") (pin "1") (pinfunction "1_1") (pintype "passive"))
      (node (ref "R194") (pin "1") (pinfunction "1_1") (pintype "passive"))
      (node (ref "R43") (pin "2") (pinfunction "2_2") (pintype "passive"))
      (node (ref "R44") (pin "1") (pinfunction "1_1") (pintype "passive"))
      (node (ref "R45") (pin "1") (pinfunction "1_1") (pintype "passive"))
      (node (ref "R74") (pin "1") (pinfunction "1_1") (pintype "passive"))
      (node (ref "R99") (pin "1") (pinfunction "1_1") (pintype "passive"))
      (node (ref "U18") (pin "2") (pinfunction "-IN_2") (pintype "input"))
    )
    (net (code "248") (name "Net-(U18B-+IN)") (class "Default")
      (node (ref "R40") (pin "1") (pinfunction "1_1") (pintype "passive"))
      (node (ref "R41") (pin "1") (pinfunction "1_1") (pintype "passive"))
      (node (ref "U18") (pin "5") (pinfunction "+IN_5") (pintype "input"))
    )
    (net (code "249") (name "Net-(U18B--IN)") (class "Default")
      (node (ref "R38") (pin "2") (pinfunction "2_2") (pintype "passive"))
      (node (ref "R39") (pin "1") (pinfunction "1_1") (pintype "passive"))
      (node (ref "U18") (pin "6") (pinfunction "-IN_6") (pintype "input"))
    )
    (net (code "250") (name "Net-(U18B-OUT)") (class "Default")
      (node (ref "R35") (pin "2") (pinfunction "2_2") (pintype "passive"))
      (node (ref "R38") (pin "1") (pinfunction "1_1") (pintype "passive"))
      (node (ref "U18") (pin "7") (pinfunction "OUT_7") (pintype "output"))
    )
    (net (code "251") (name "Net-(U18C-+IN)") (class "Default")
      (node (ref "R176") (pin "1") (pinfunction "1_1") (pintype "passive"))
      (node (ref "R177") (pin "1") (pinfunction "1_1") (pintype "passive"))
      (node (ref "U18") (pin "10") (pinfunction "+IN_10") (pintype "input"))
    )
    (net (code "252") (name "Net-(U18C--IN)") (class "Default")
      (node (ref "R174") (pin "1") (pinfunction "1_1") (pintype "passive"))
      (node (ref "R175") (pin "2") (pinfunction "2_2") (pintype "passive"))
      (node (ref "U18") (pin "9") (pinfunction "-IN_9") (pintype "input"))
    )
    (net (code "253") (name "Net-(U18D-+IN)") (class "Default")
      (node (ref "R189") (pin "2") (pinfunction "2_2") (pintype "passive"))
      (node (ref "R190") (pin "1") (pinfunction "1_1") (pintype "passive"))
      (node (ref "U18") (pin "12") (pinfunction "+IN_12") (pintype "input"))
    )
    (net (code "254") (name "Net-(U21A-E)") (class "Default")
      (node (ref "U21") (pin "4") (pinfunction "E_4") (pintype "passive"))
      (node (ref "U21") (pin "5") (pinfunction "E_5") (pintype "passive"))
      (node (ref "U22") (pin "3") (pinfunction "C_3") (pintype "passive"))
    )
    (net (code "255") (name "Net-(U22A-B)") (class "Default")
      (node (ref "R37") (pin "2") (pinfunction "2_2") (pintype "passive"))
      (node (ref "U22") (pin "1") (pinfunction "B_1") (pintype "passive"))
      (node (ref "U22") (pin "2") (pinfunction "B_2") (pintype "passive"))
      (node (ref "U22") (pin "6") (pinfunction "C_6") (pintype "passive"))
    )
    (net (code "256") (name "Net-(U24A-E)") (class "Default")
      (node (ref "U24") (pin "4") (pinfunction "E_4") (pintype "passive"))
      (node (ref "U24") (pin "5") (pinfunction "E_5") (pintype "passive"))
      (node (ref "U25") (pin "3") (pinfunction "C_3") (pintype "passive"))
    )
    (net (code "257") (name "Net-(U25A-B)") (class "Default")
      (node (ref "R49") (pin "2") (pinfunction "2_2") (pintype "passive"))
      (node (ref "U25") (pin "1") (pinfunction "B_1") (pintype "passive"))
      (node (ref "U25") (pin "2") (pinfunction "B_2") (pintype "passive"))
      (node (ref "U25") (pin "6") (pinfunction "C_6") (pintype "passive"))
    )
    (net (code "258") (name "Net-(U27A-E)") (class "Default")
      (node (ref "U27") (pin "4") (pinfunction "E_4") (pintype "passive"))
      (node (ref "U27") (pin "5") (pinfunction "E_5") (pintype "passive"))
      (node (ref "U28") (pin "3") (pinfunction "C_3") (pintype "passive"))
    )
    (net (code "259") (name "Net-(U28A-B)") (class "Default")
      (node (ref "R53") (pin "2") (pinfunction "2_2") (pintype "passive"))
      (node (ref "U28") (pin "1") (pinfunction "B_1") (pintype "passive"))
      (node (ref "U28") (pin "2") (pinfunction "B_2") (pintype "passive"))
      (node (ref "U28") (pin "6") (pinfunction "C_6") (pintype "passive"))
    )
    (net (code "260") (name "Net-(U30A-E)") (class "Default")
      (node (ref "U30") (pin "4") (pinfunction "E_4") (pintype "passive"))
      (node (ref "U30") (pin "5") (pinfunction "E_5") (pintype "passive"))
      (node (ref "U31") (pin "3") (pinfunction "C_3") (pintype "passive"))
    )
    (net (code "261") (name "Net-(U31A-B)") (class "Default")
      (node (ref "R62") (pin "2") (pinfunction "2_2") (pintype "passive"))
      (node (ref "U31") (pin "1") (pinfunction "B_1") (pintype "passive"))
      (node (ref "U31") (pin "2") (pinfunction "B_2") (pintype "passive"))
      (node (ref "U31") (pin "6") (pinfunction "C_6") (pintype "passive"))
    )
    (net (code "262") (name "OSC_0") (class "Default")
      (node (ref "JP1") (pin "31") (pinfunction "31_31") (pintype "passive"))
      (node (ref "OSC0") (pin "TP") (pinfunction "TP_TP") (pintype "input"))
      (node (ref "R45") (pin "2") (pinfunction "2_2") (pintype "passive"))
      (node (ref "RN6") (pin "16") (pinfunction "2_16") (pintype "passive"))
      (node (ref "RN9") (pin "9") (pinfunction "2_9") (pintype "passive"))
    )
    (net (code "263") (name "OSC_1") (class "Default")
      (node (ref "JP1") (pin "30") (pinfunction "30_30") (pintype "passive"))
      (node (ref "OSC1") (pin "TP") (pinfunction "TP_TP") (pintype "input"))
      (node (ref "R44") (pin "2") (pinfunction "2_2") (pintype "passive"))
      (node (ref "RN10") (pin "16") (pinfunction "2_16") (pintype "passive"))
      (node (ref "RN13") (pin "9") (pinfunction "2_9") (pintype "passive"))
    )
    (net (code "264") (name "OSC_2") (class "Default")
      (node (ref "JP1") (pin "32") (pinfunction "32_32") (pintype "passive"))
      (node (ref "OSC2") (pin "TP") (pinfunction "TP_TP") (pintype "input"))
      (node (ref "R99") (pin "2") (pinfunction "2_2") (pintype "passive"))
      (node (ref "RN14") (pin "9") (pinfunction "2_9") (pintype "passive"))
      (node (ref "RN17") (pin "16") (pinfunction "2_16") (pintype "passive"))
    )
    (net (code "265") (name "OUT") (class "Default")
      (node (ref "3.3V") (pin "TP") (pinfunction "TP_TP") (pintype "input"))
      (node (ref "C29") (pin "1") (pinfunction "1_1") (pintype "passive"))
      (node (ref "C31") (pin "1") (pinfunction "1_1") (pintype "passive"))
      (node (ref "U5") (pin "5") (pinfunction "OUT_5") (pintype "power_in"))
    )
    (net (code "266") (name "PWM_CUTOFF") (class "Default")
      (node (ref "C80") (pin "2") (pinfunction "2_2") (pintype "passive"))
      (node (ref "JP1") (pin "34") (pinfunction "34_34") (pintype "passive"))
      (node (ref "R30") (pin "1") (pinfunction "1_1") (pintype "passive"))
      (node (ref "R63") (pin "2") (pinfunction "2_2") (pintype "passive"))
    )
    (net (code "267") (name "PWM_NOISE") (class "Default")
      (node (ref "C70") (pin "2") (pinfunction "2_2") (pintype "passive"))
      (node (ref "R186") (pin "2") (pinfunction "2_2") (pintype "passive"))
      (node (ref "RN5") (pin "7") (pinfunction "2_7") (pintype "passive"))
    )
    (net (code "268") (name "PWM_RESO") (class "Default")
      (node (ref "C71") (pin "2") (pinfunction "2_2") (pintype "passive"))
      (node (ref "R180") (pin "1") (pinfunction "1_1") (pintype "passive"))
      (node (ref "RN5") (pin "8") (pinfunction "2_8") (pintype "passive"))
    )
    (net (code "269") (name "PWM_SUB") (class "Default")
      (node (ref "C68") (pin "2") (pinfunction "2_2") (pintype "passive"))
      (node (ref "R174") (pin "2") (pinfunction "2_2") (pintype "passive"))
      (node (ref "RN5") (pin "5") (pinfunction "2_5") (pintype "passive"))
    )
    (net (code "270") (name "PWM_VCA") (class "Default")
      (node (ref "C69") (pin "2") (pinfunction "2_2") (pintype "passive"))
      (node (ref "R171") (pin "1") (pinfunction "1_1") (pintype "passive"))
      (node (ref "RN5") (pin "6") (pinfunction "2_6") (pintype "passive"))
    )
    (net (code "271") (name "RESO") (class "Default")
      (node (ref "R178") (pin "2") (pinfunction "2_2") (pintype "passive"))
      (node (ref "U$8") (pin "2") (pinfunction "B_2") (pintype "passive"))
      (node (ref "U21") (pin "1") (pinfunction "B_1") (pintype "passive"))
      (node (ref "U4") (pin "7") (pinfunction "OUT_7") (pintype "output"))
    )
    (net (code "272") (name "RES_OUT") (class "Default")
      (node (ref "C44") (pin "2") (pinfunction "2_2") (pintype "passive"))
      (node (ref "R36") (pin "1") (pinfunction "1_1") (pintype "passive"))
      (node (ref "R42") (pin "2") (pinfunction "2_2") (pintype "passive"))
      (node (ref "U14") (pin "14") (pinfunction "OUT_14") (pintype "output"))
    )
    (net (code "273") (name "RXD") (class "Default")
      (node (ref "OK1") (pin "6") (pinfunction "VO_6") (pintype "passive"))
      (node (ref "R182") (pin "2") (pinfunction "2_2") (pintype "passive"))
      (node (ref "SAMD21") (pin "38") (pinfunction "PB23/I7/SERCOM5.3_38") (pintype "bidirectional"))
    )
    (net (code "274") (name "SCK") (class "Default")
      (node (ref "JP1") (pin "9") (pinfunction "9_9") (pintype "passive"))
      (node (ref "RN2") (pin "2") (pinfunction "1_2") (pintype "passive"))
      (node (ref "RN3") (pin "3") (pinfunction "1_3") (pintype "passive"))
      (node (ref "RN4") (pin "6") (pinfunction "2_6") (pintype "passive"))
      (node (ref "SAMD21") (pin "20") (pinfunction "PB11/I11/SERCOM4.3/I2SCL_20") (pintype "bidirectional"))
    )
    (net (code "275") (name "SCL") (class "Default")
      (node (ref "JP1") (pin "13") (pinfunction "13_13") (pintype "passive"))
      (node (ref "SAMD21") (pin "32") (pinfunction "PA23/I2C/I7/SERCOM3+5.1/SOF_32") (pintype "bidirectional"))
    )
    (net (code "276") (name "SDA") (class "Default")
      (node (ref "JP1") (pin "14") (pinfunction "14_14") (pintype "passive"))
      (node (ref "SAMD21") (pin "31") (pinfunction "PA22/I2C/I6/SERCOM3+5.0_31") (pintype "bidirectional"))
    )
    (net (code "277") (name "SD_CS") (class "Default")
      (node (ref "IC3") (pin "1") (pinfunction "~{OE}_1") (pintype "input"))
      (node (ref "R64") (pin "1") (pinfunction "1_1") (pintype "passive"))
      (node (ref "RN2") (pin "4") (pinfunction "1_4") (pintype "passive"))
      (node (ref "SAMD21") (pin "28") (pinfunction "PA19/I3/SERCOM1+3.3/I2SD0_28") (pintype "bidirectional"))
    )
    (net (code "278") (name "SD_MISO") (class "Default")
      (node (ref "IC3") (pin "2") (pinfunction "A_2") (pintype "input"))
      (node (ref "RN2") (pin "1") (pinfunction "1_1") (pintype "passive"))
    )
    (net (code "279") (name "SPI_SS_B") (class "Default")
      (node (ref "IC4") (pin "1") (pinfunction "~{OE}_1") (pintype "input"))
      (node (ref "RN3") (pin "4") (pinfunction "1_4") (pintype "passive"))
      (node (ref "SAMD21") (pin "3") (pinfunction "PA02/EINT2/AIN0/Y0/VOUT_3") (pintype "bidirectional"))
    )
    (net (code "280") (name "SUB") (class "Default")
      (node (ref "R175") (pin "1") (pinfunction "1_1") (pintype "passive"))
      (node (ref "U$15") (pin "2") (pinfunction "B_2") (pintype "passive"))
      (node (ref "U18") (pin "8") (pinfunction "OUT_8") (pintype "output"))
      (node (ref "U27") (pin "1") (pinfunction "B_1") (pintype "passive"))
    )
    (net (code "281") (name "SUB0") (class "Default")
      (node (ref "R71") (pin "2") (pinfunction "2_2") (pintype "passive"))
      (node (ref "U$2") (pin "125") (pinfunction "IOT_192_125") (pintype "bidirectional"))
    )
    (net (code "282") (name "SUB1") (class "Default")
      (node (ref "R70") (pin "2") (pinfunction "2_2") (pintype "passive"))
      (node (ref "U$2") (pin "130") (pinfunction "IOT_206_130") (pintype "bidirectional"))
    )
    (net (code "283") (name "SUB2") (class "Default")
      (node (ref "R51") (pin "2") (pinfunction "2_2") (pintype "passive"))
      (node (ref "U$2") (pin "134") (pinfunction "IOT_212_134") (pintype "bidirectional"))
    )
    (net (code "284") (name "SUB_SCALED") (class "Default")
      (node (ref "C57") (pin "2") (pinfunction "2_2") (pintype "passive"))
      (node (ref "R192") (pin "2") (pinfunction "2_2") (pintype "passive"))
      (node (ref "R52") (pin "1") (pinfunction "1_1") (pintype "passive"))
      (node (ref "U8") (pin "8") (pinfunction "OUT_8") (pintype "output"))
    )
    (net (code "285") (name "SWCLK") (class "Default")
      (node (ref "J100") (pin "4") (pinfunction "4_4") (pintype "passive"))
      (node (ref "SAMD21") (pin "45") (pinfunction "PA30/I10/SECOM1.2/SWCLK_45") (pintype "bidirectional"))
    )
    (net (code "286") (name "SWDIO") (class "Default")
      (node (ref "J100") (pin "2") (pinfunction "2_2") (pintype "passive"))
      (node (ref "SAMD21") (pin "46") (pinfunction "PA31/I11/SECOM1.3/SWDIO_46") (pintype "bidirectional"))
    )
    (net (code "287") (name "VBAT") (class "Default")
      (node (ref "C8") (pin "1") (pinfunction "1_1") (pintype "passive"))
      (node (ref "C81") (pin "1") (pinfunction "1_1") (pintype "passive"))
      (node (ref "CN2") (pin "1") (pinfunction "2_1") (pintype "passive"))
      (node (ref "D1") (pin "A") (pinfunction "A_A") (pintype "passive"))
      (node (ref "IC2") (pin "3") (pinfunction "VBAT_3") (pintype "bidirectional"))
    )
    (net (code "288") (name "VBUS") (class "Default")
      (node (ref "D3") (pin "A") (pinfunction "A_A") (pintype "passive"))
      (node (ref "IC2") (pin "4") (pinfunction "VDD_4") (pintype "power_in"))
      (node (ref "LED1") (pin "A") (pinfunction "A_A") (pintype "passive"))
      (node (ref "X3") (pin "VBUS") (pinfunction "VBUS_VBUS") (pintype "power_in"))
    )
    (net (code "289") (name "VCA") (class "Default")
      (node (ref "R170") (pin "2") (pinfunction "2_2") (pintype "passive"))
      (node (ref "U$9") (pin "2") (pinfunction "B_2") (pintype "passive"))
      (node (ref "U24") (pin "1") (pinfunction "B_1") (pintype "passive"))
      (node (ref "U4") (pin "8") (pinfunction "OUT_8") (pintype "output"))
    )
    (net (code "290") (name "VIN") (class "Default")
      (node (ref "C5") (pin "1") (pinfunction "1_1") (pintype "passive"))
      (node (ref "D1") (pin "C") (pinfunction "C_C") (pintype "passive"))
      (node (ref "D3") (pin "C") (pinfunction "C_C") (pintype "passive"))
      (node (ref "FB2") (pin "1") (pinfunction "P$1_1") (pintype "passive"))
      (node (ref "JP1") (pin "5") (pinfunction "5_5") (pintype "passive"))
    )
    (net (code "291") (name "VSUM") (class "Default")
      (node (ref "R2") (pin "2") (pinfunction "2_2") (pintype "passive"))
      (node (ref "R40") (pin "2") (pinfunction "2_2") (pintype "passive"))
      (node (ref "R43") (pin "1") (pinfunction "1_1") (pintype "passive"))
      (node (ref "U18") (pin "1") (pinfunction "OUT_1") (pintype "output"))
    )
    (net (code "292") (name "unconnected-(CN1-P$1-Pad1)") (class "Default")
      (node (ref "CN1") (pin "1") (pinfunction "P$1_1") (pintype "bidirectional"))
    )
    (net (code "293") (name "unconnected-(CN1-P$3-Pad5)") (class "Default")
      (node (ref "CN1") (pin "5") (pinfunction "P$3_5") (pintype "bidirectional"))
    )
    (net (code "294") (name "unconnected-(CN1-P$4-Pad4)") (class "Default")
      (node (ref "CN1") (pin "4") (pinfunction "P$4_4") (pintype "bidirectional"))
    )
    (net (code "295") (name "unconnected-(CN3-P$3-Pad5)") (class "Default")
      (node (ref "CN3") (pin "5") (pinfunction "P$3_5") (pintype "bidirectional"))
    )
    (net (code "296") (name "unconnected-(CN3-P$4-Pad4)") (class "Default")
      (node (ref "CN3") (pin "4") (pinfunction "P$4_4") (pintype "bidirectional"))
    )
    (net (code "297") (name "unconnected-(J100-Pad6)") (class "Default")
      (node (ref "J100") (pin "6") (pinfunction "6_6") (pintype "passive"))
    )
    (net (code "298") (name "unconnected-(J100-Pad7)") (class "Default")
      (node (ref "J100") (pin "7") (pinfunction "7_7") (pintype "passive"))
    )
    (net (code "299") (name "unconnected-(J100-Pad8)") (class "Default")
      (node (ref "J100") (pin "8") (pinfunction "8_8") (pintype "passive"))
    )
    (net (code "300") (name "unconnected-(JP1-Pad21)") (class "Default")
      (node (ref "JP1") (pin "21") (pinfunction "21_21") (pintype "passive"))
    )
    (net (code "301") (name "unconnected-(JP1-Pad23)") (class "Default")
      (node (ref "JP1") (pin "23") (pinfunction "23_23") (pintype "passive"))
    )
    (net (code "302") (name "unconnected-(JP1-Pad24)") (class "Default")
      (node (ref "JP1") (pin "24") (pinfunction "24_24") (pintype "passive"))
    )
    (net (code "303") (name "unconnected-(JP1-Pad25)") (class "Default")
      (node (ref "JP1") (pin "25") (pinfunction "25_25") (pintype "passive"))
    )
    (net (code "304") (name "unconnected-(JP1-Pad26)") (class "Default")
      (node (ref "JP1") (pin "26") (pinfunction "26_26") (pintype "passive"))
    )
    (net (code "305") (name "unconnected-(JP1-Pad27)") (class "Default")
      (node (ref "JP1") (pin "27") (pinfunction "27_27") (pintype "passive"))
    )
    (net (code "306") (name "unconnected-(JP1-Pad28)") (class "Default")
      (node (ref "JP1") (pin "28") (pinfunction "28_28") (pintype "passive"))
    )
    (net (code "307") (name "unconnected-(JP1-Pad29)") (class "Default")
      (node (ref "JP1") (pin "29") (pinfunction "29_29") (pintype "passive"))
    )
    (net (code "308") (name "unconnected-(OK1-VE-Pad7)") (class "Default")
      (node (ref "OK1") (pin "7") (pinfunction "VE_7") (pintype "passive"))
    )
    (net (code "309") (name "unconnected-(RN8-Pad1)") (class "Default")
      (node (ref "RN8") (pin "1") (pinfunction "1_1") (pintype "passive"))
    )
    (net (code "310") (name "unconnected-(RN8A-2-Pad16)") (class "Default")
      (node (ref "RN8") (pin "16") (pinfunction "2_16") (pintype "passive"))
    )
    (net (code "311") (name "unconnected-(RN12-Pad1)") (class "Default")
      (node (ref "RN12") (pin "1") (pinfunction "1_1") (pintype "passive"))
    )
    (net (code "312") (name "unconnected-(RN12A-2-Pad16)") (class "Default")
      (node (ref "RN12") (pin "16") (pinfunction "2_16") (pintype "passive"))
    )
    (net (code "313") (name "unconnected-(RN16H-1-Pad8)") (class "Default")
      (node (ref "RN16") (pin "8") (pinfunction "1_8") (pintype "passive"))
    )
    (net (code "314") (name "unconnected-(RN16H-2-Pad9)") (class "Default")
      (node (ref "RN16") (pin "9") (pinfunction "2_9") (pintype "passive"))
    )
    (net (code "315") (name "unconnected-(SAMD21-PA13{slash}I13{slash}I2C{slash}SERCOM2+4.1-Pad22)") (class "Default")
      (node (ref "SAMD21") (pin "22") (pinfunction "PA13/I13/I2C/SERCOM2+4.1_22") (pintype "bidirectional"))
    )
    (net (code "316") (name "unconnected-(SAMD21-PA15{slash}I15{slash}SERCOM3+4.3-Pad24)") (class "Default")
      (node (ref "SAMD21") (pin "24") (pinfunction "PA15/I15/SERCOM3+4.3_24") (pintype "bidirectional"))
    )
    (net (code "317") (name "unconnected-(SAMD21-PA16{slash}I2C{slash}I0{slash}SERCOM1+3.0-Pad25)") (class "Default")
      (node (ref "SAMD21") (pin "25") (pinfunction "PA16/I2C/I0/SERCOM1+3.0_25") (pintype "bidirectional"))
    )
    (net (code "318") (name "unconnected-(SAMD21-PA27{slash}I15-Pad39)") (class "Default")
      (node (ref "SAMD21") (pin "39") (pinfunction "PA27/I15_39") (pintype "bidirectional"))
    )
    (net (code "319") (name "unconnected-(SAMD21-PA28{slash}I8-Pad41)") (class "Default")
      (node (ref "SAMD21") (pin "41") (pinfunction "PA28/I8_41") (pintype "bidirectional"))
    )
    (net (code "320") (name "unconnected-(SAMD21-PB03{slash}I3{slash}AIN11{slash}SERCOM5.1-Pad48)") (class "Default")
      (node (ref "SAMD21") (pin "48") (pinfunction "PB03/I3/AIN11/SERCOM5.1_48") (pintype "bidirectional"))
    )
    (net (code "321") (name "unconnected-(SAMD21-PB22{slash}I6{slash}SERCOM5.2-Pad37)") (class "Default")
      (node (ref "SAMD21") (pin "37") (pinfunction "PB22/I6/SERCOM5.2_37") (pintype "bidirectional"))
    )
    (net (code "322") (name "unconnected-(U$2A-IOT_178-Pad119)") (class "Default")
      (node (ref "U$2") (pin "119") (pinfunction "IOT_178_119") (pintype "bidirectional"))
    )
    (net (code "323") (name "unconnected-(U$2A-IOT_179-Pad120)") (class "Default")
      (node (ref "U$2") (pin "120") (pinfunction "IOT_179_120") (pintype "bidirectional"))
    )
    (net (code "324") (name "unconnected-(U$2A-IOT_181-Pad121)") (class "Default")
      (node (ref "U$2") (pin "121") (pinfunction "IOT_181_121") (pintype "bidirectional"))
    )
    (net (code "325") (name "unconnected-(U$2A-IOT_190-Pad122)") (class "Default")
      (node (ref "U$2") (pin "122") (pinfunction "IOT_190_122") (pintype "bidirectional"))
    )
    (net (code "326") (name "unconnected-(U$2A-IOT_191-Pad124)") (class "Default")
      (node (ref "U$2") (pin "124") (pinfunction "IOT_191_124") (pintype "bidirectional"))
    )
    (net (code "327") (name "unconnected-(U$2A-IOT_197_GBIN1-Pad128)") (class "Default")
      (node (ref "U$2") (pin "128") (pinfunction "IOT_197_GBIN1_128") (pintype "bidirectional"))
    )
    (net (code "328") (name "unconnected-(U$2A-IOT_198_GBIN0-Pad129)") (class "Default")
      (node (ref "U$2") (pin "129") (pinfunction "IOT_198_GBIN0_129") (pintype "bidirectional"))
    )
    (net (code "329") (name "unconnected-(U$2B-IOR_109-Pad73)") (class "Default")
      (node (ref "U$2") (pin "73") (pinfunction "IOR_109_73") (pintype "bidirectional"))
    )
    (net (code "330") (name "unconnected-(U$2B-IOR_110-Pad74)") (class "Default")
      (node (ref "U$2") (pin "74") (pinfunction "IOR_110_74") (pintype "bidirectional"))
    )
    (net (code "331") (name "unconnected-(U$2B-IOR_111-Pad75)") (class "Default")
      (node (ref "U$2") (pin "75") (pinfunction "IOR_111_75") (pintype "bidirectional"))
    )
    (net (code "332") (name "unconnected-(U$2B-IOR_112-Pad76)") (class "Default")
      (node (ref "U$2") (pin "76") (pinfunction "IOR_112_76") (pintype "bidirectional"))
    )
    (net (code "333") (name "unconnected-(U$2B-IOR_114-Pad78)") (class "Default")
      (node (ref "U$2") (pin "78") (pinfunction "IOR_114_78") (pintype "bidirectional"))
    )
    (net (code "334") (name "unconnected-(U$2B-IOR_115-Pad79)") (class "Default")
      (node (ref "U$2") (pin "79") (pinfunction "IOR_115_79") (pintype "bidirectional"))
    )
    (net (code "335") (name "unconnected-(U$2B-IOR_116-Pad80)") (class "Default")
      (node (ref "U$2") (pin "80") (pinfunction "IOR_116_80") (pintype "bidirectional"))
    )
    (net (code "336") (name "unconnected-(U$2B-IOR_117-Pad81)") (class "Default")
      (node (ref "U$2") (pin "81") (pinfunction "IOR_117_81") (pintype "bidirectional"))
    )
    (net (code "337") (name "unconnected-(U$2B-IOR_118-Pad82)") (class "Default")
      (node (ref "U$2") (pin "82") (pinfunction "IOR_118_82") (pintype "bidirectional"))
    )
    (net (code "338") (name "unconnected-(U$2B-IOR_119-Pad83)") (class "Default")
      (node (ref "U$2") (pin "83") (pinfunction "IOR_119_83") (pintype "bidirectional"))
    )
    (net (code "339") (name "unconnected-(U$2B-IOR_120-Pad84)") (class "Default")
      (node (ref "U$2") (pin "84") (pinfunction "IOR_120_84") (pintype "bidirectional"))
    )
    (net (code "340") (name "unconnected-(U$2B-IOR_128-Pad85)") (class "Default")
      (node (ref "U$2") (pin "85") (pinfunction "IOR_128_85") (pintype "bidirectional"))
    )
    (net (code "341") (name "unconnected-(U$2B-IOR_136-Pad87)") (class "Default")
      (node (ref "U$2") (pin "87") (pinfunction "IOR_136_87") (pintype "bidirectional"))
    )
    (net (code "342") (name "unconnected-(U$2B-IOR_137-Pad88)") (class "Default")
      (node (ref "U$2") (pin "88") (pinfunction "IOR_137_88") (pintype "bidirectional"))
    )
    (net (code "343") (name "unconnected-(U$2B-IOR_138-Pad90)") (class "Default")
      (node (ref "U$2") (pin "90") (pinfunction "IOR_138_90") (pintype "bidirectional"))
    )
    (net (code "344") (name "unconnected-(U$2B-IOR_139-Pad91)") (class "Default")
      (node (ref "U$2") (pin "91") (pinfunction "IOR_139_91") (pintype "bidirectional"))
    )
    (net (code "345") (name "unconnected-(U$2B-IOR_140_GBIN3-Pad93)") (class "Default")
      (node (ref "U$2") (pin "93") (pinfunction "IOR_140_GBIN3_93") (pintype "bidirectional"))
    )
    (net (code "346") (name "unconnected-(U$2B-IOR_141_GBIN2-Pad94)") (class "Default")
      (node (ref "U$2") (pin "94") (pinfunction "IOR_141_GBIN2_94") (pintype "bidirectional"))
    )
    (net (code "347") (name "unconnected-(U$2B-IOR_144-Pad95)") (class "Default")
      (node (ref "U$2") (pin "95") (pinfunction "IOR_144_95") (pintype "bidirectional"))
    )
    (net (code "348") (name "unconnected-(U$2B-IOR_146-Pad96)") (class "Default")
      (node (ref "U$2") (pin "96") (pinfunction "IOR_146_96") (pintype "bidirectional"))
    )
    (net (code "349") (name "unconnected-(U$2B-IOR_147-Pad97)") (class "Default")
      (node (ref "U$2") (pin "97") (pinfunction "IOR_147_97") (pintype "bidirectional"))
    )
    (net (code "350") (name "unconnected-(U$2B-IOR_148-Pad98)") (class "Default")
      (node (ref "U$2") (pin "98") (pinfunction "IOR_148_98") (pintype "bidirectional"))
    )
    (net (code "351") (name "unconnected-(U$2B-IOR_152-Pad99)") (class "Default")
      (node (ref "U$2") (pin "99") (pinfunction "IOR_152_99") (pintype "bidirectional"))
    )
    (net (code "352") (name "unconnected-(U$2B-NC-Pad77)") (class "Default")
      (node (ref "U$2") (pin "77") (pinfunction "NC_77") (pintype "bidirectional"))
    )
    (net (code "353") (name "unconnected-(U$2B-VPP_FAST-Pad109)") (class "Default")
      (node (ref "U$2") (pin "109") (pinfunction "VPP_FAST_109") (pintype "bidirectional"))
    )
    (net (code "354") (name "unconnected-(U$2C-IOB_81_GBIN5-Pad49)") (class "Default")
      (node (ref "U$2") (pin "49") (pinfunction "IOB_81_GBIN5_49") (pintype "bidirectional"))
    )
    (net (code "355") (name "unconnected-(U$2C-IOB_82_GBIN4-Pad52)") (class "Default")
      (node (ref "U$2") (pin "52") (pinfunction "IOB_82_GBIN4_52") (pintype "bidirectional"))
    )
    (net (code "356") (name "unconnected-(U$2C-IOB_104_CBSEL1-Pad64)") (class "Default")
      (node (ref "U$2") (pin "64") (pinfunction "IOB_104_CBSEL1_64") (pintype "bidirectional"))
    )
    (net (code "357") (name "unconnected-(U$2D-IOL_8A-Pad11)") (class "Default")
      (node (ref "U$2") (pin "11") (pinfunction "IOL_8A_11") (pintype "bidirectional"))
    )
    (net (code "358") (name "unconnected-(U$2D-IOL_10B-Pad16)") (class "Default")
      (node (ref "U$2") (pin "16") (pinfunction "IOL_10B_16") (pintype "bidirectional"))
    )
    (net (code "359") (name "unconnected-(U$2D-IOL_12B-Pad18)") (class "Default")
      (node (ref "U$2") (pin "18") (pinfunction "IOL_12B_18") (pintype "bidirectional"))
    )
    (net (code "360") (name "unconnected-(U$2D-IOL_13B_GBIN7-Pad20)") (class "Default")
      (node (ref "U$2") (pin "20") (pinfunction "IOL_13B_GBIN7_20") (pintype "bidirectional"))
    )
    (net (code "361") (name "unconnected-(U$2D-IOL_14B-Pad22)") (class "Default")
      (node (ref "U$2") (pin "22") (pinfunction "IOL_14B_22") (pintype "bidirectional"))
    )
    (net (code "362") (name "unconnected-(U$2D-IOL_17B-Pad24)") (class "Default")
      (node (ref "U$2") (pin "24") (pinfunction "IOL_17B_24") (pintype "bidirectional"))
    )
    (net (code "363") (name "unconnected-(U5-P4-Pad4)") (class "Default")
      (node (ref "U5") (pin "4") (pinfunction "P4_4") (pintype "bidirectional"))
    )
    (net (code "364") (name "unconnected-(X3-PadID)") (class "Default")
      (node (ref "X3") (pin "ID") (pinfunction "ID_ID") (pintype "bidirectional"))
    )
    (net (code "365") (name "unconnected-(X4-CARD_DETECT-PadCD1)") (class "Default")
      (node (ref "X4") (pin "CD1") (pinfunction "CARD_DETECT_CD1") (pintype "passive"))
    )
    (net (code "366") (name "unconnected-(X4-CARD_DETECT1-PadCD2)") (class "Default")
      (node (ref "X4") (pin "CD2") (pinfunction "CARD_DETECT1_CD2") (pintype "passive"))
    )
    (net (code "367") (name "unconnected-(X4-DAT1-Pad8)") (class "Default")
      (node (ref "X4") (pin "8") (pinfunction "DAT1_8") (pintype "bidirectional"))
    )
    (net (code "368") (name "unconnected-(X4-DAT2-Pad1)") (class "Default")
      (node (ref "X4") (pin "1") (pinfunction "DAT2_1") (pintype "bidirectional"))
    )
    (net (code "369") (name "~{RESET}") (class "Default")
      (node (ref "JP1") (pin "3") (pinfunction "3_3") (pintype "passive"))
      (node (ref "R179") (pin "2") (pinfunction "2_2") (pintype "passive"))
      (node (ref "SAMD21") (pin "40") (pinfunction "/RESET_40") (pintype "bidirectional"))
      (node (ref "SW1") (pin "1") (pinfunction "P_1") (pintype "passive"))
      (node (ref "SW1") (pin "3") (pinfunction "P1_3") (pintype "passive"))
    )
  )
)
